# EM80RD.net
KiCad netlist of a schematic drawn in EAGLE
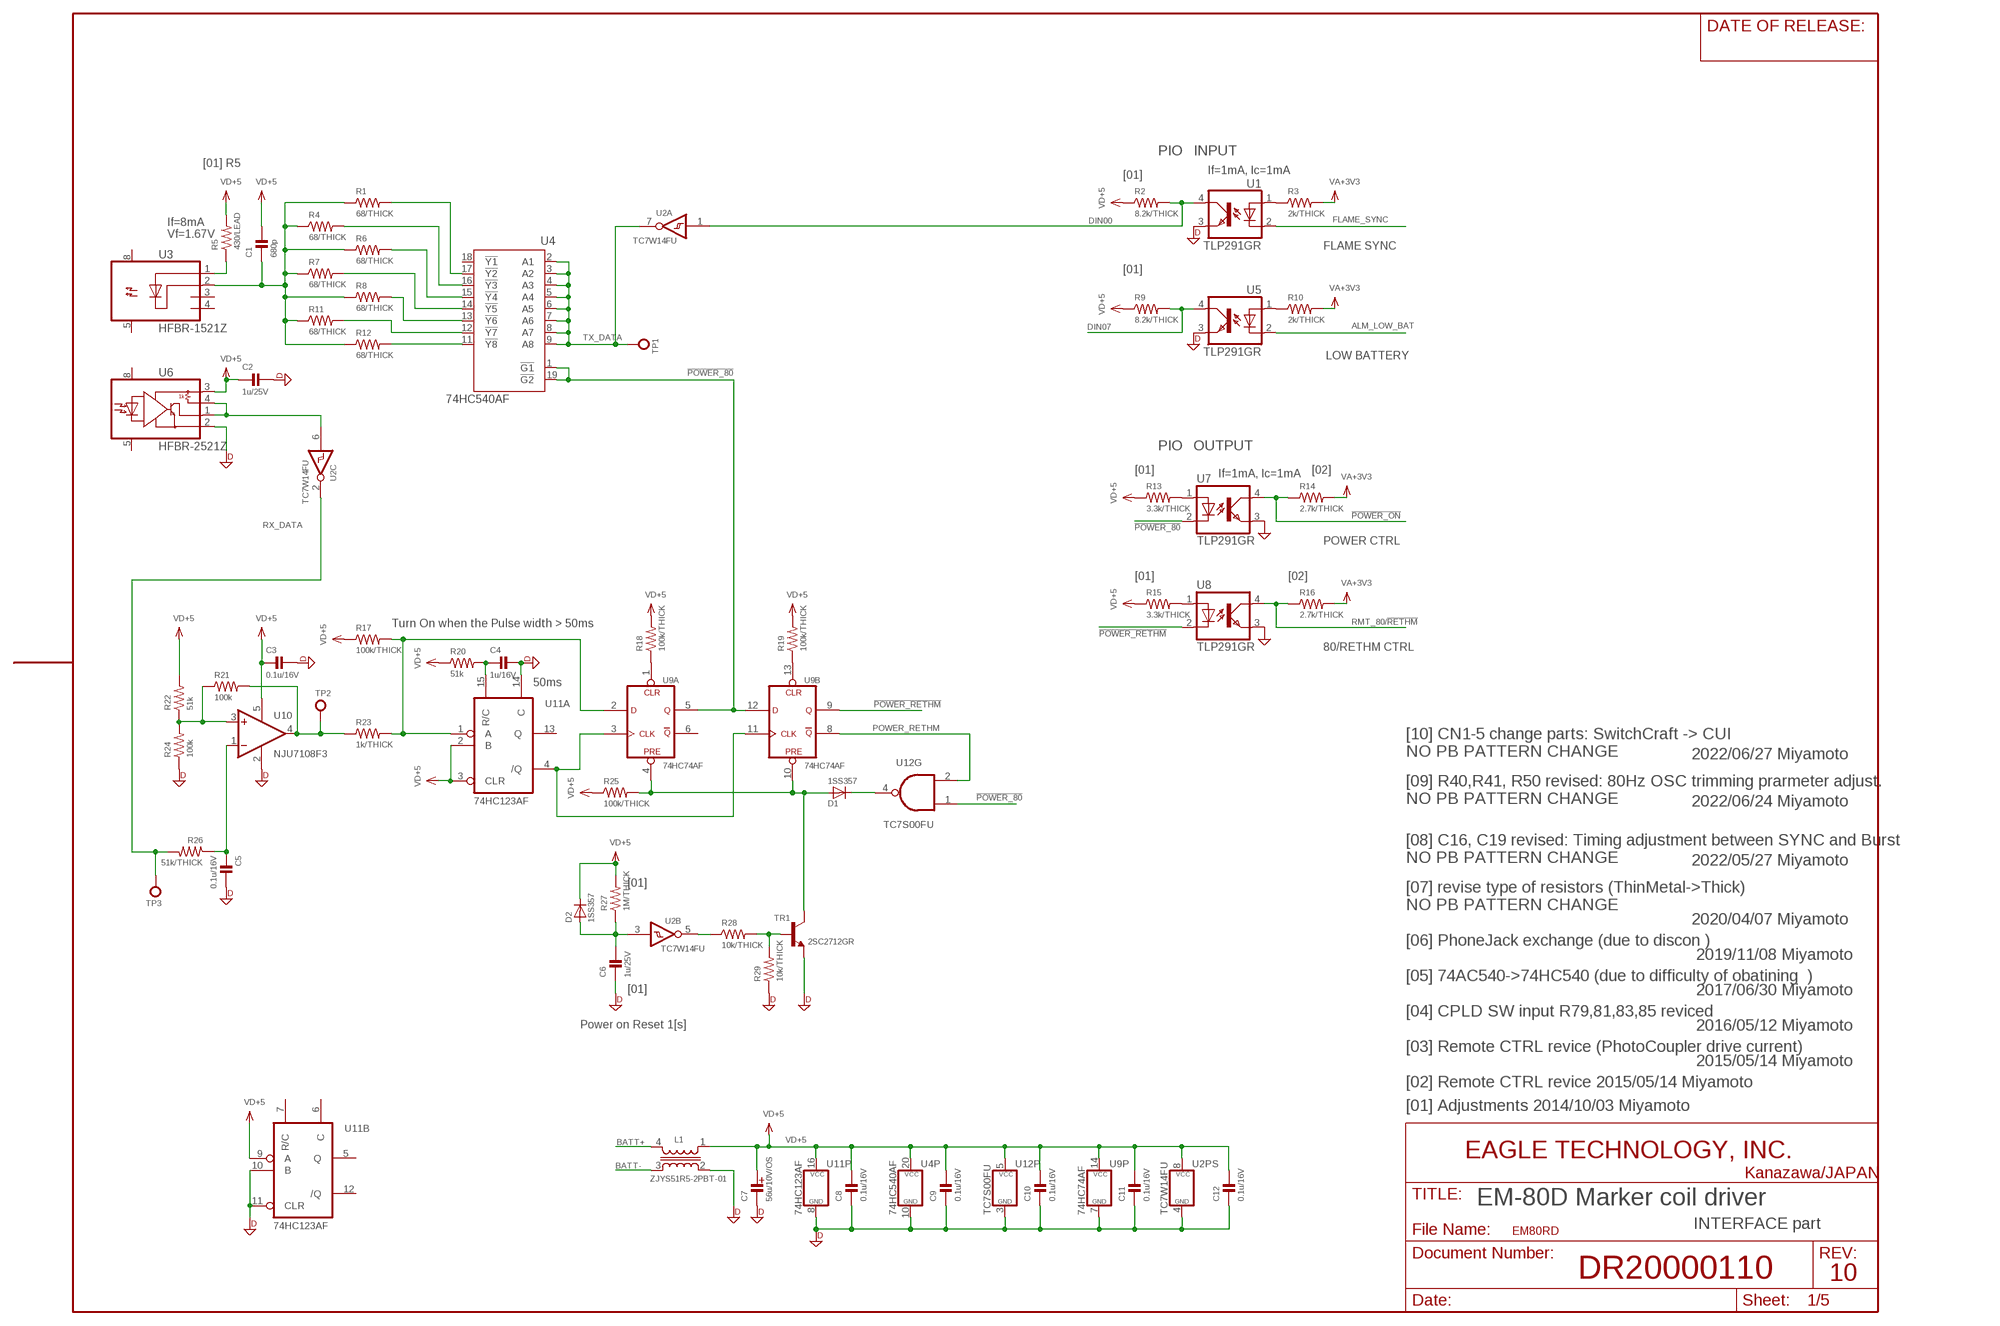
[diagram p0: schematic, sheet 1]
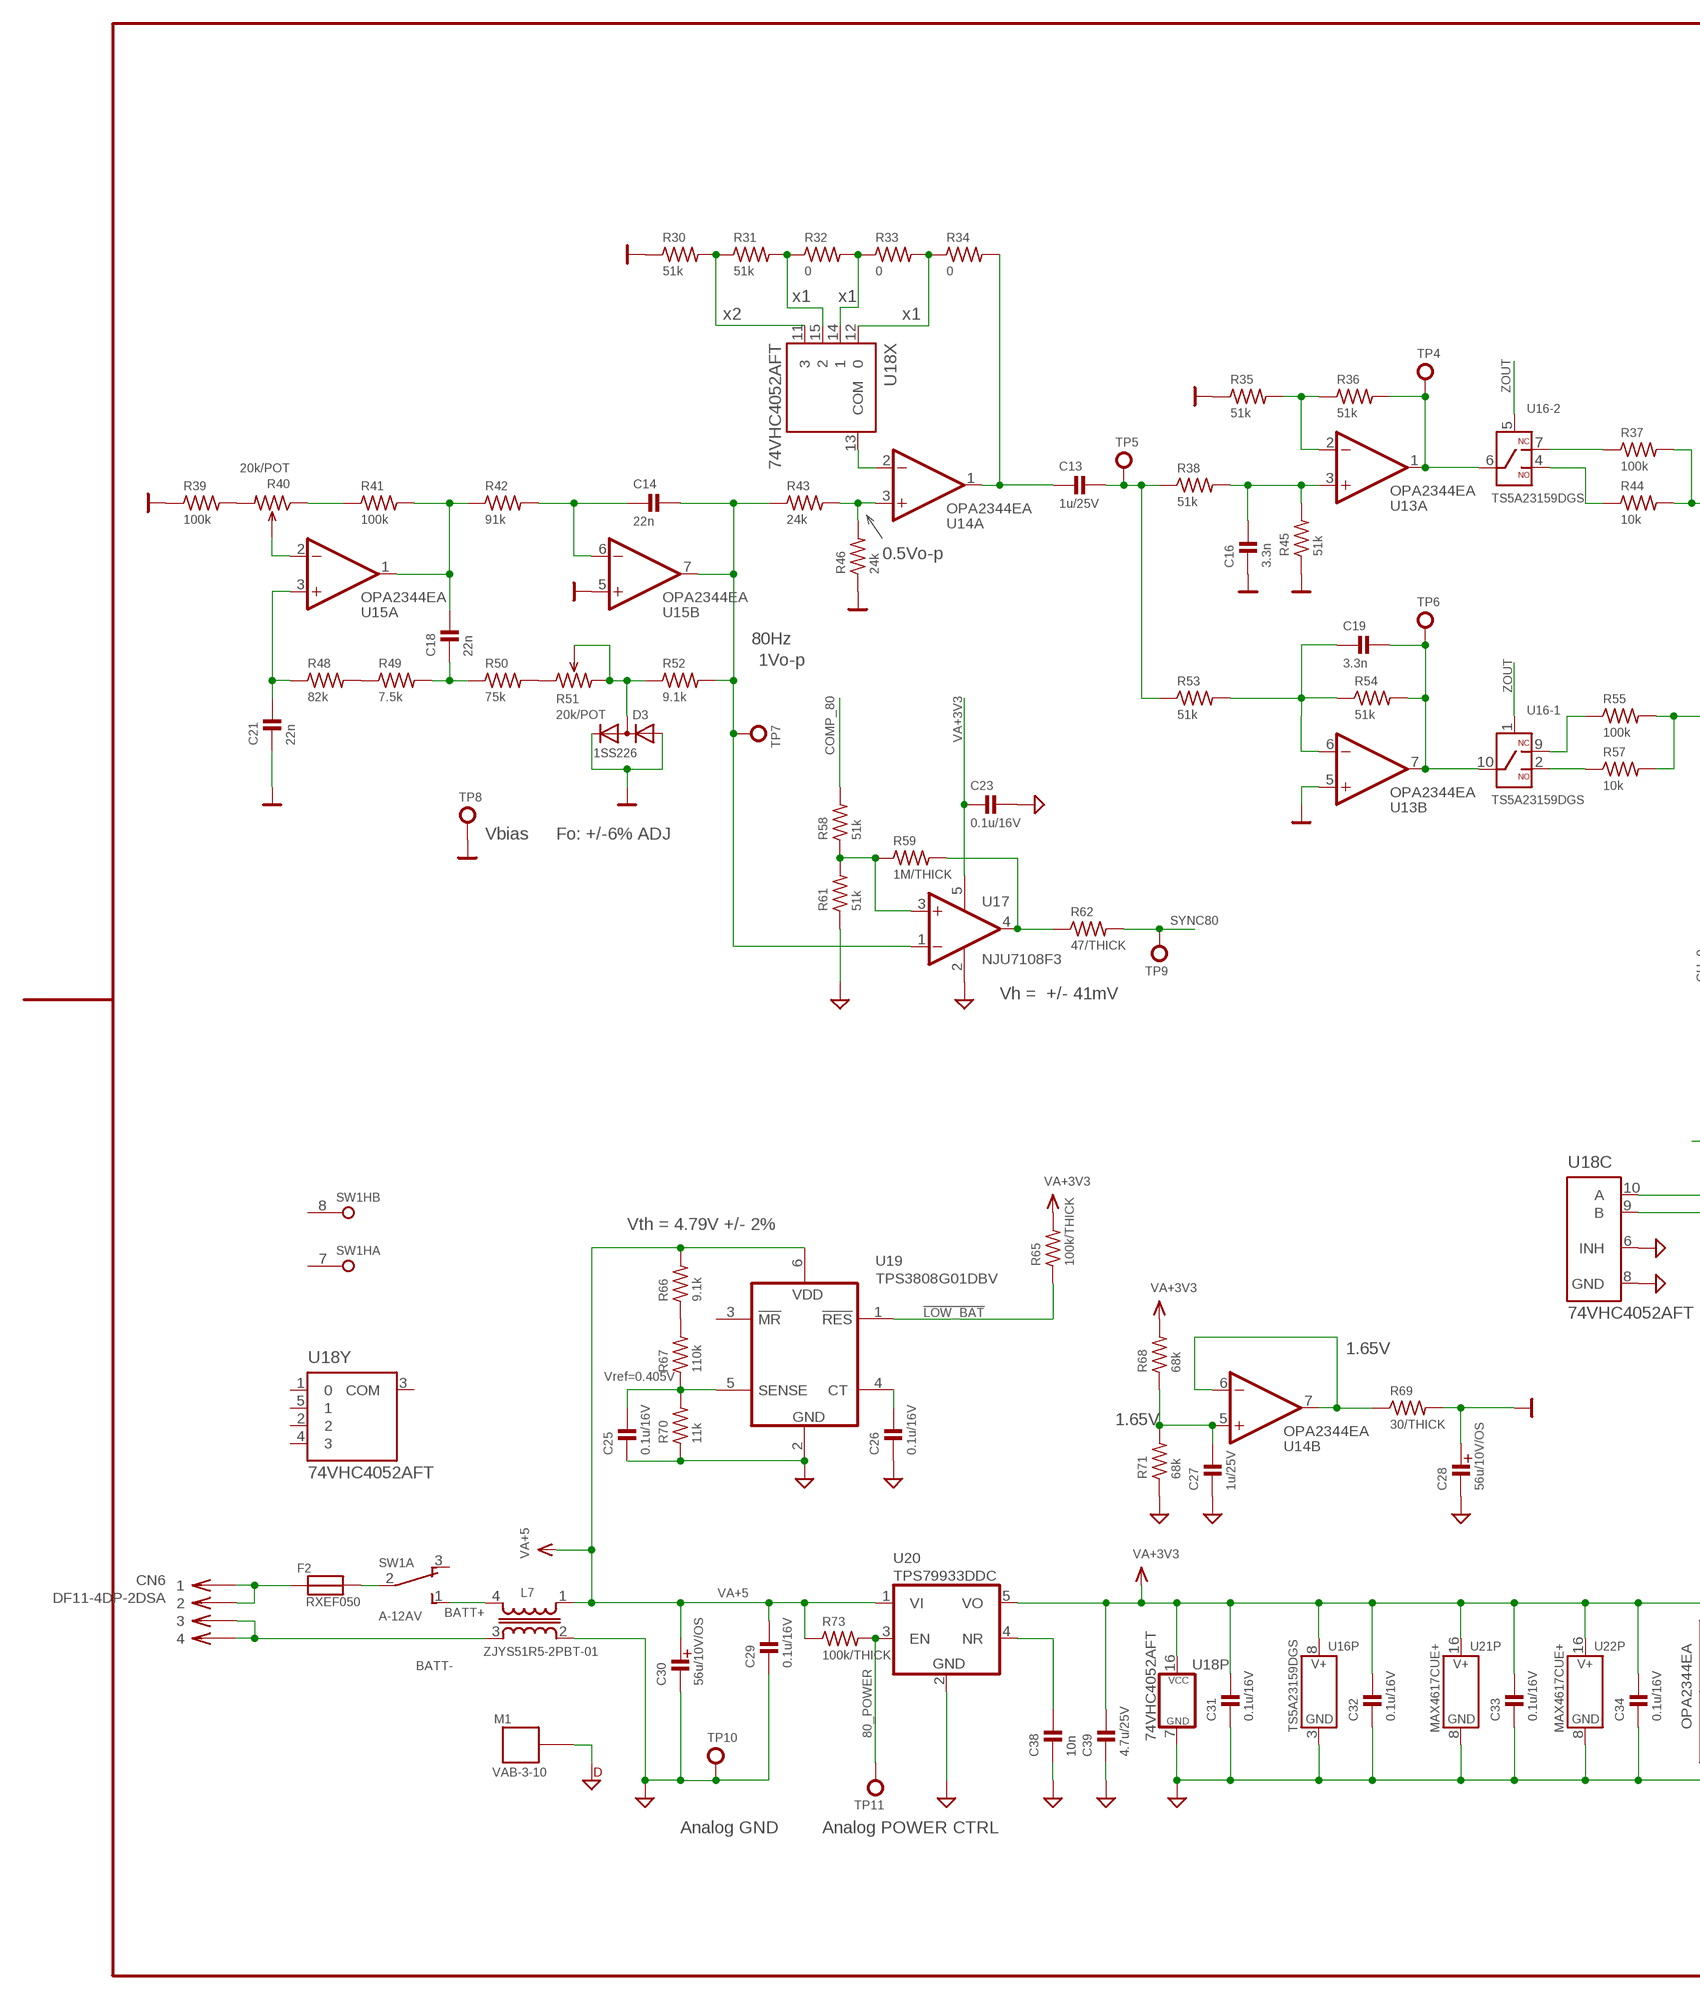
[diagram p1: schematic, sheet 2, part 1 of 2]
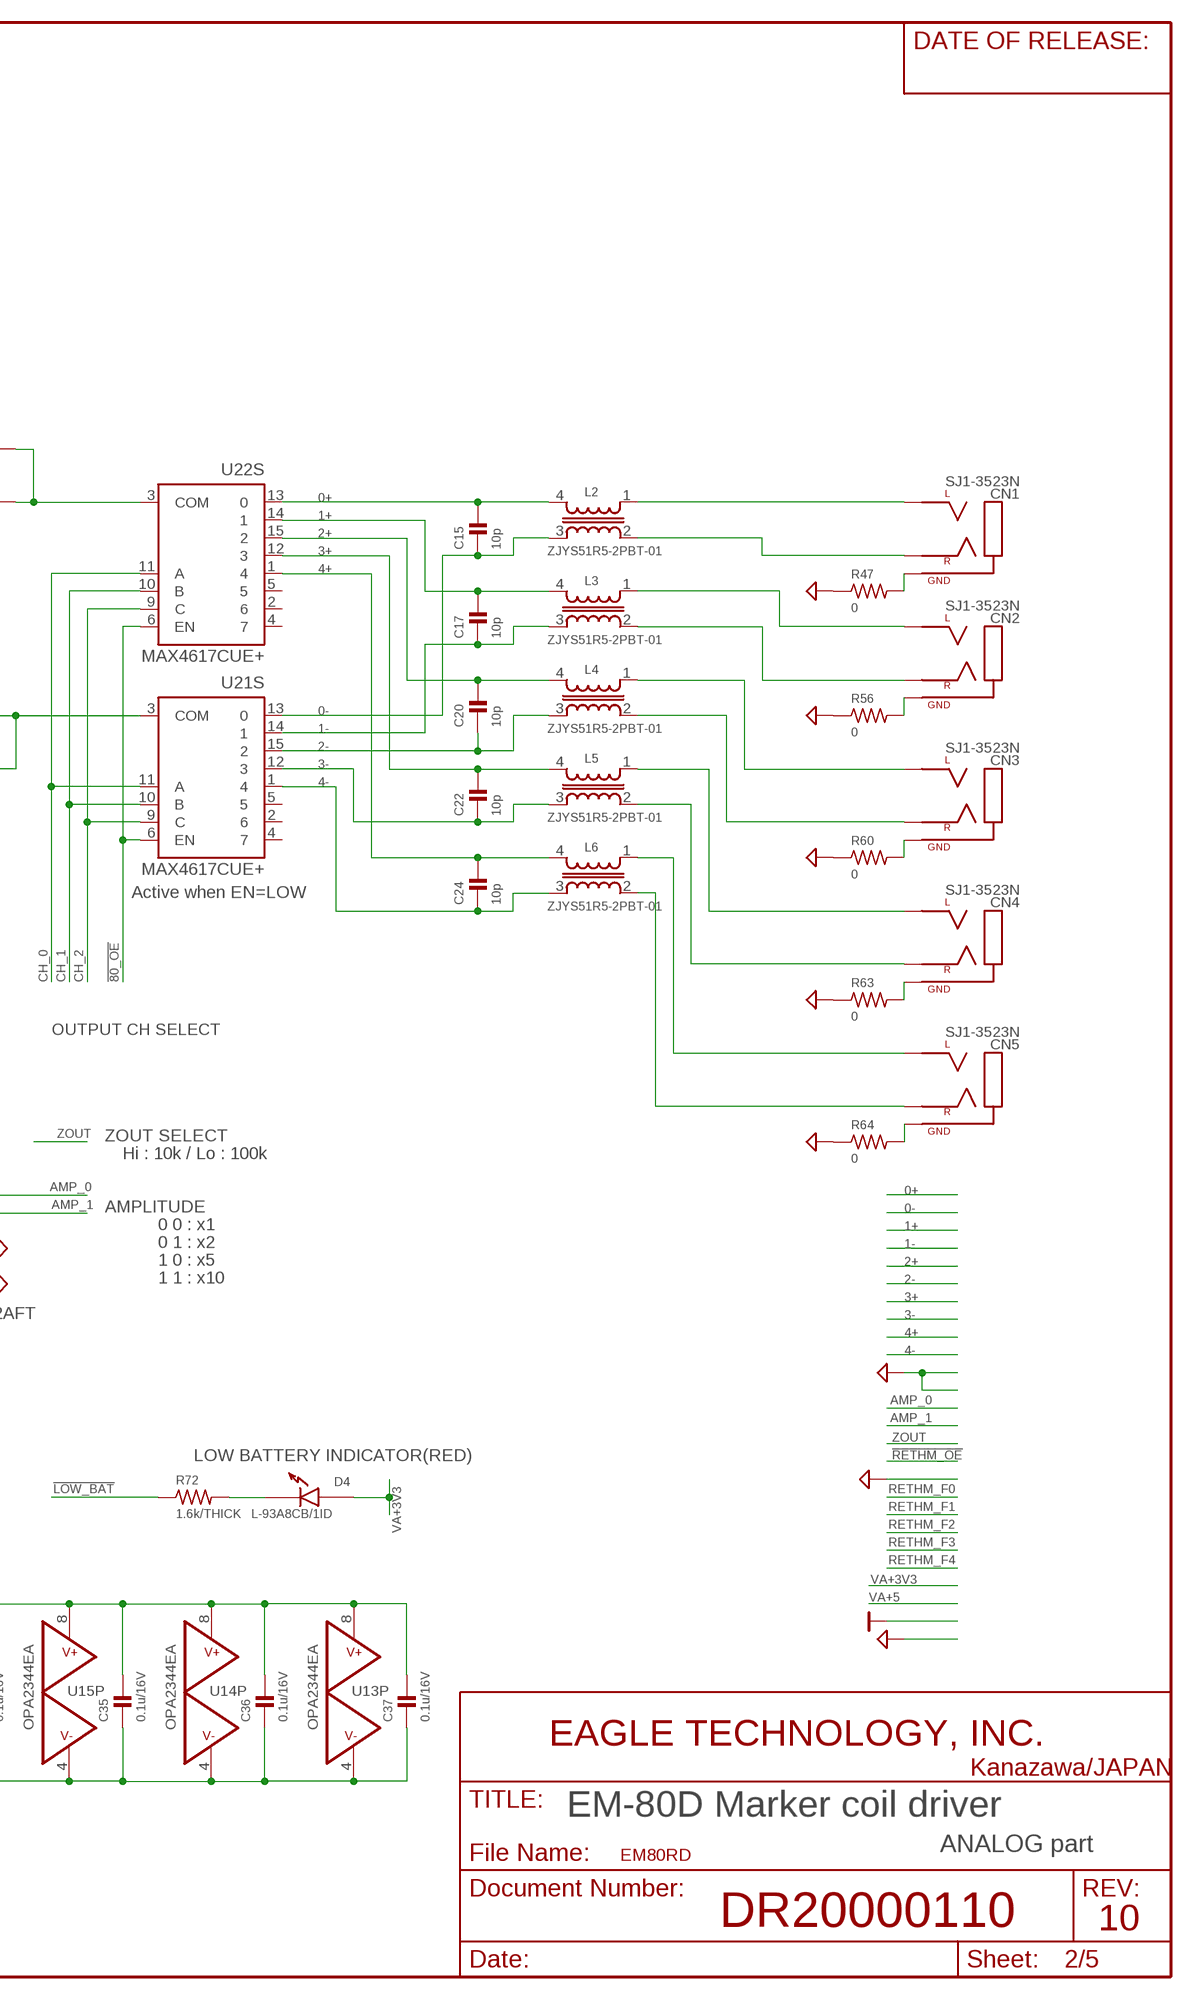
[diagram p2: schematic, sheet 2, part 2 of 2]
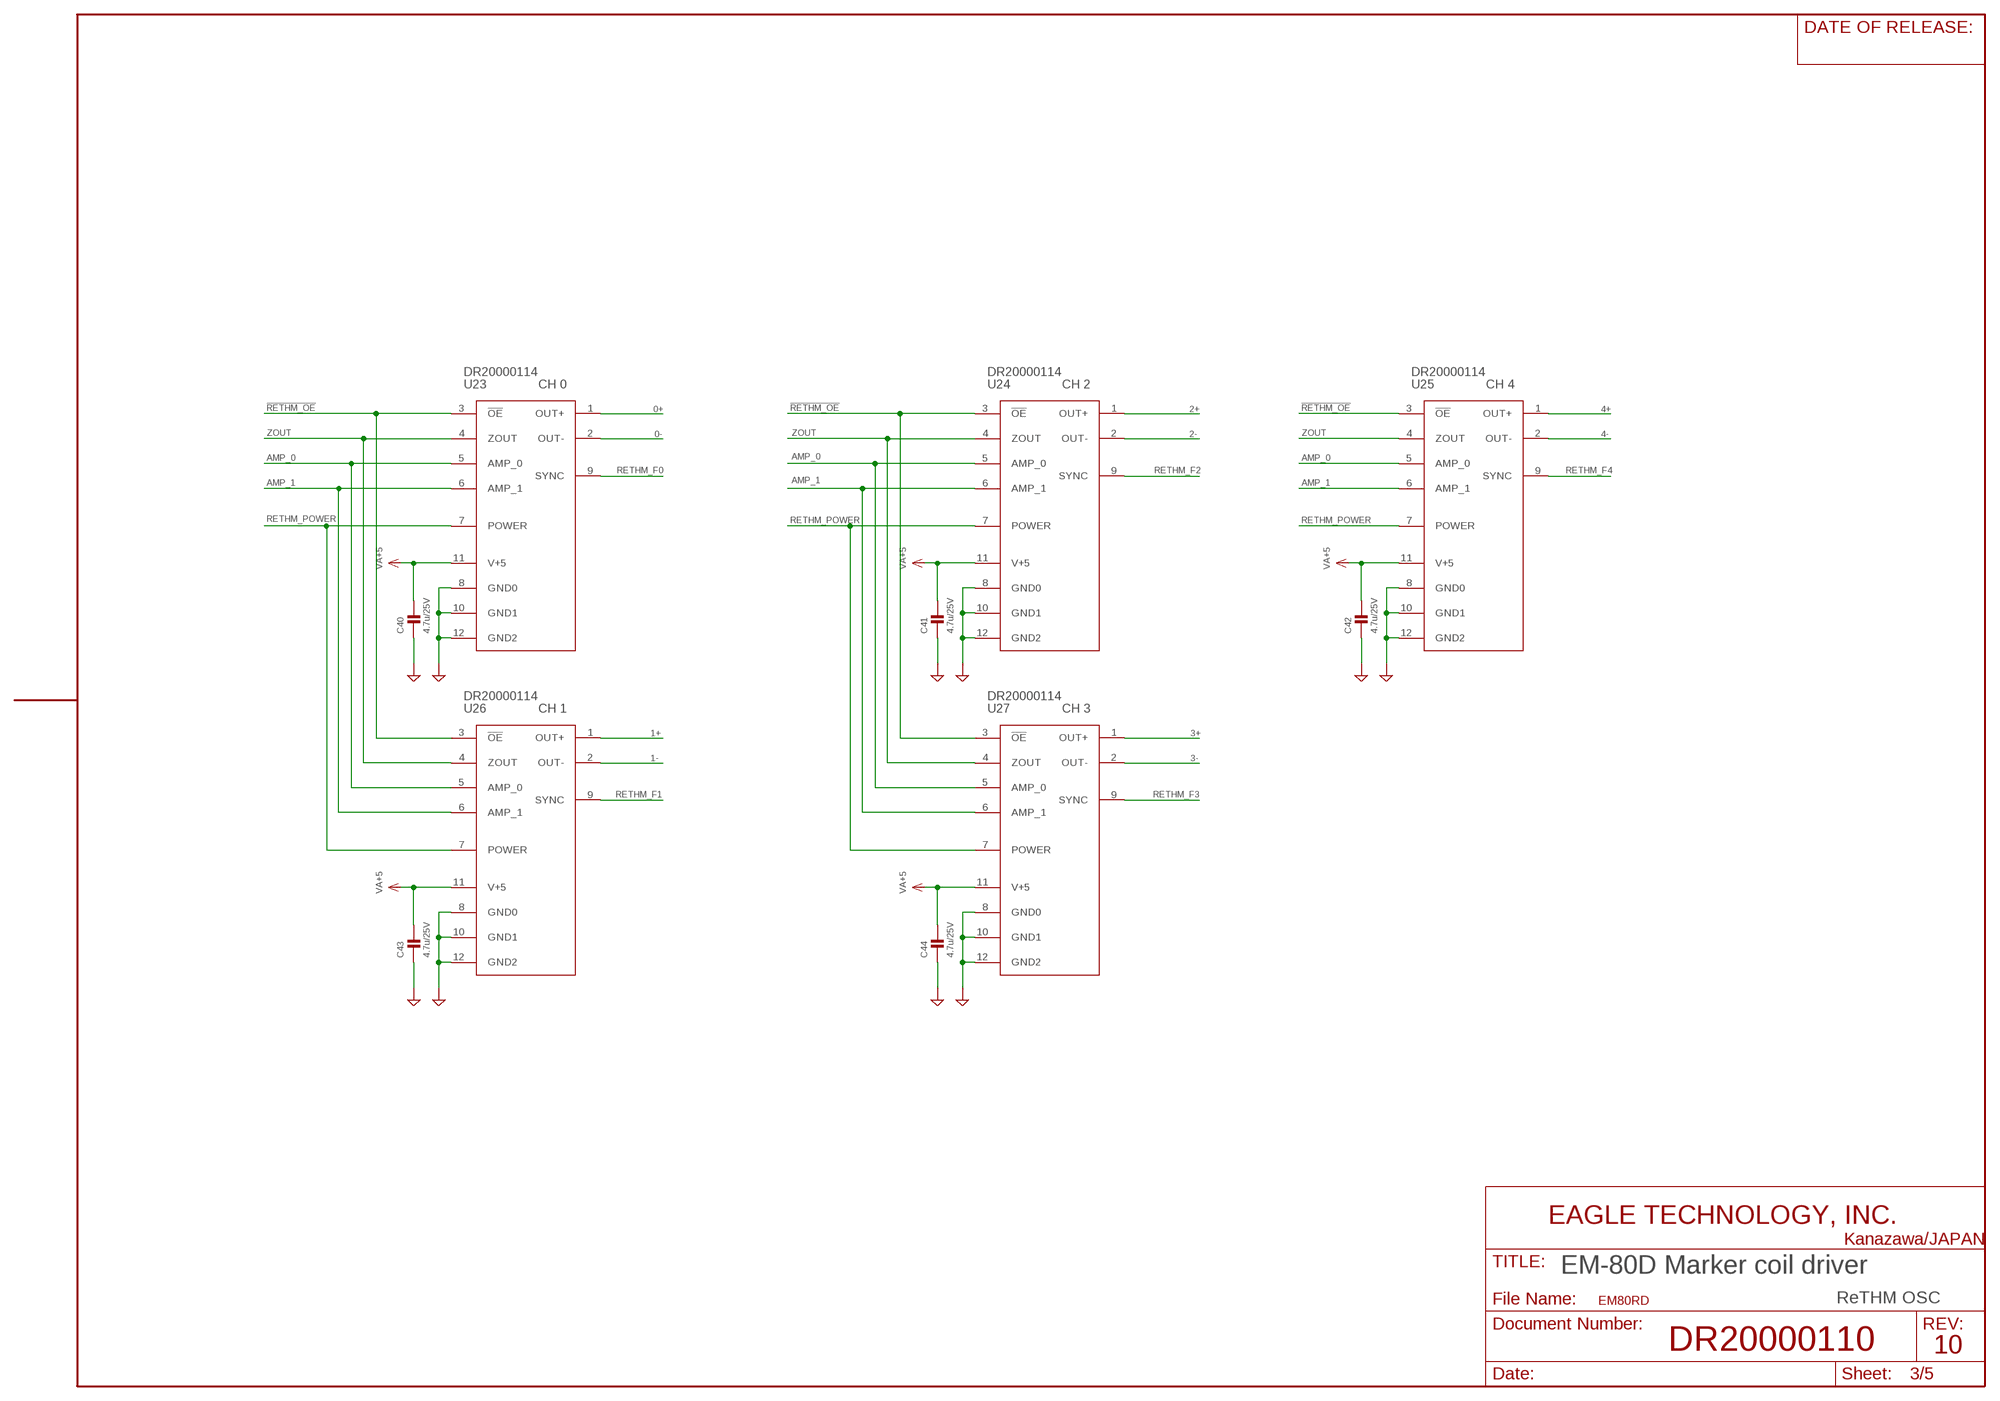
[diagram p3: schematic, sheet 3]
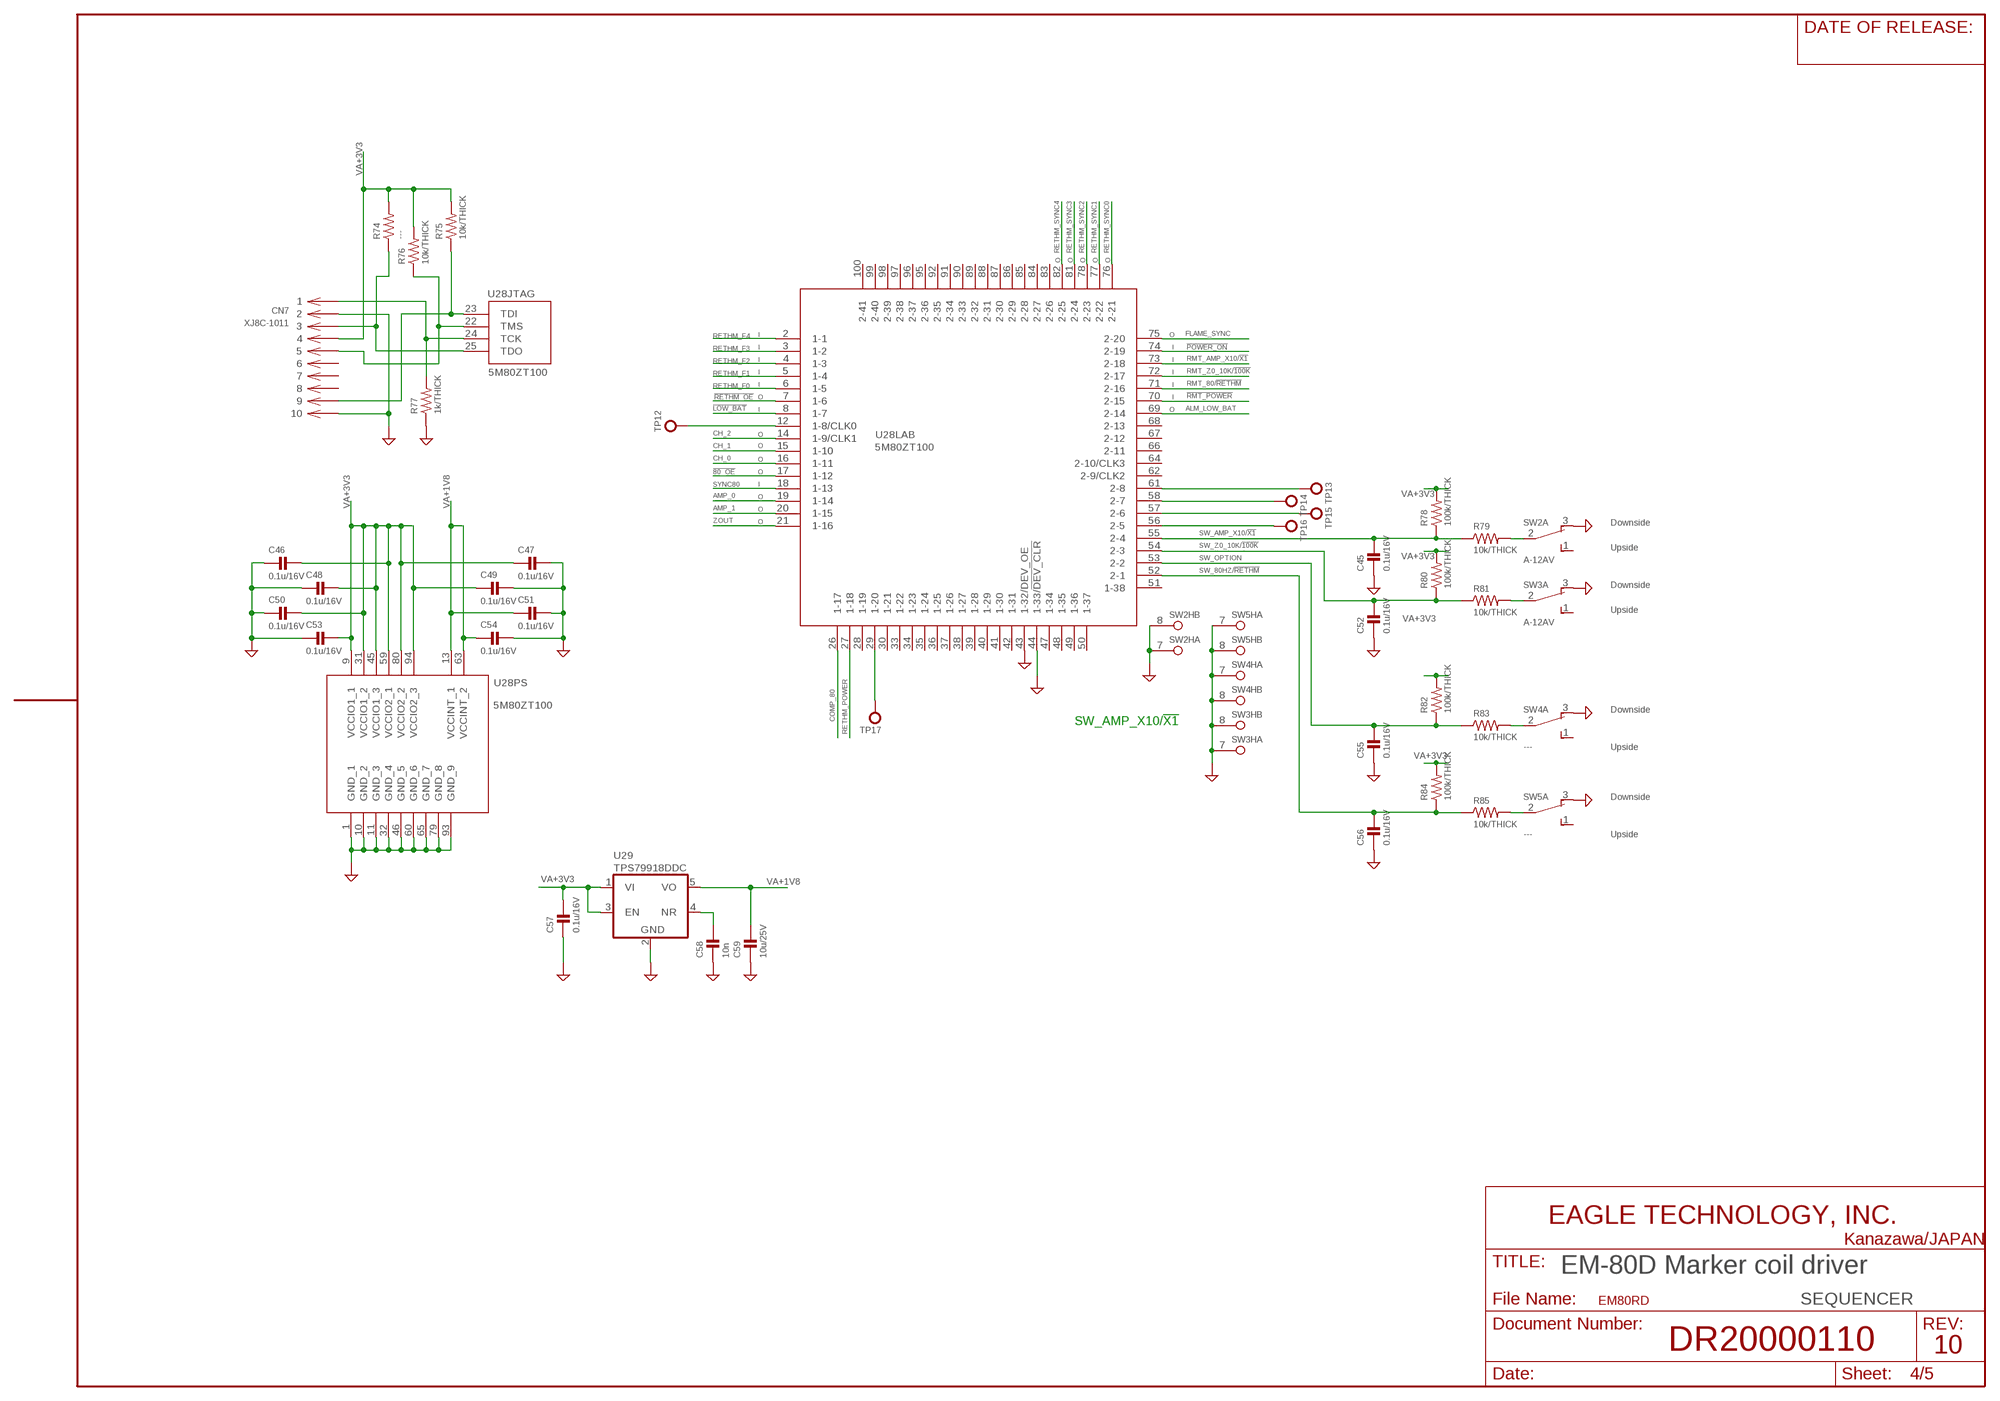
[diagram p4: schematic, sheet 4]
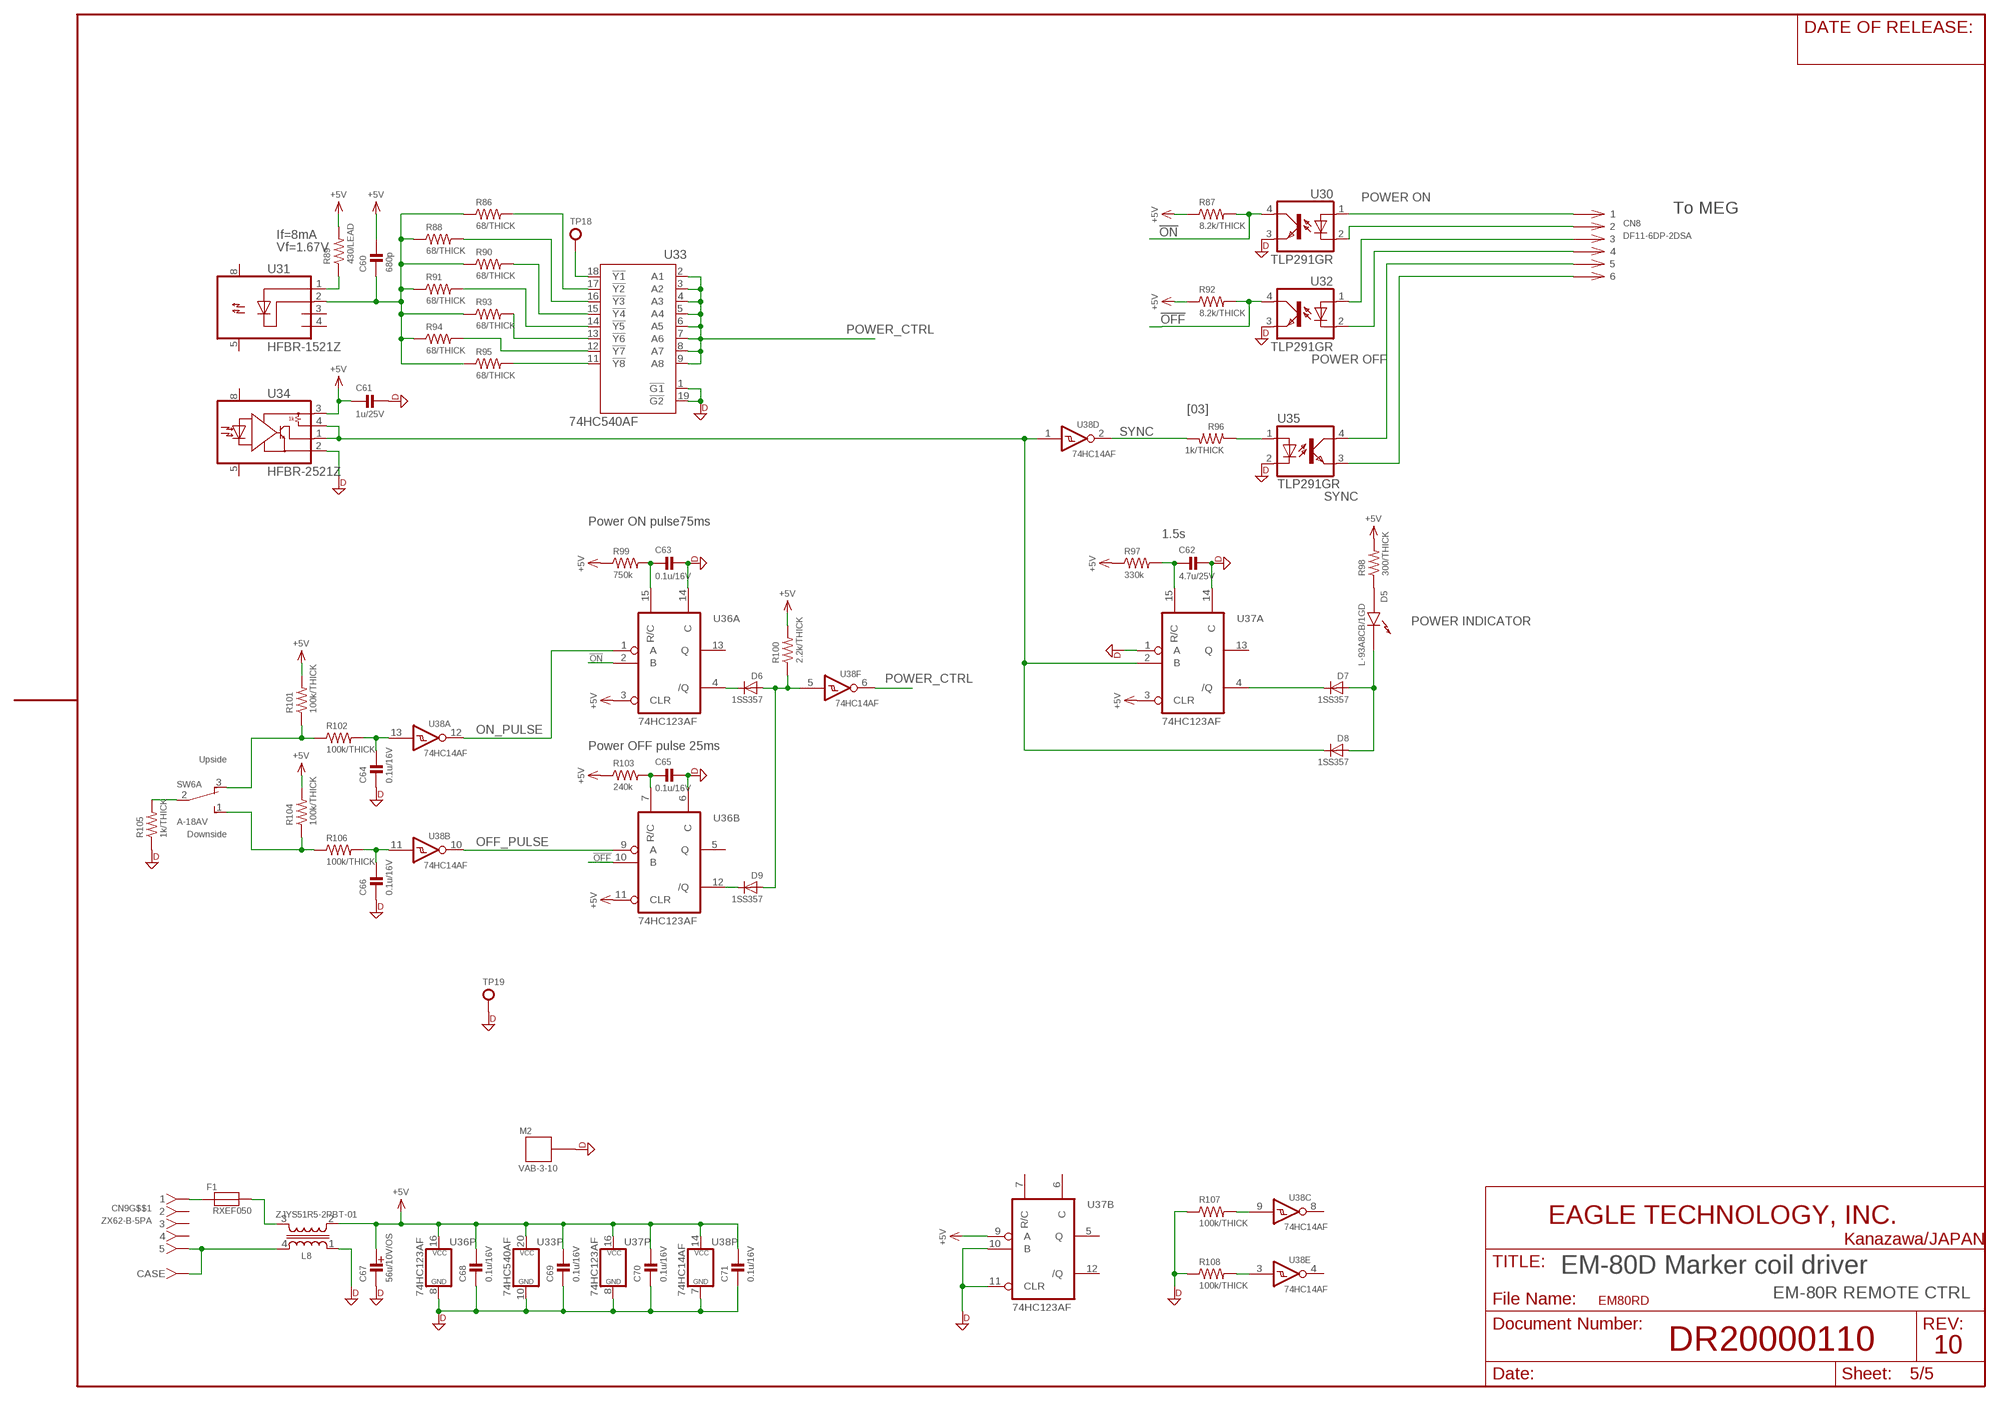
[diagram p5: schematic, sheet 5]

(export (version "E")
  (design (tool "Eeschema 10.0.6"))
  (components
    (comp (ref "C40")
      (value "4.7u/25V")
      (footprint "eagle-import:CM2012")
      (libsource (lib "eagle-import") (part "CSMD2.0X1.2MM"))
    )
    (comp (ref "C41")
      (value "4.7u/25V")
      (footprint "eagle-import:CM2012")
      (libsource (lib "eagle-import") (part "CSMD2.0X1.2MM"))
    )
    (comp (ref "C42")
      (value "4.7u/25V")
      (footprint "eagle-import:CM2012")
      (libsource (lib "eagle-import") (part "CSMD2.0X1.2MM"))
    )
    (comp (ref "C43")
      (value "4.7u/25V")
      (footprint "eagle-import:CM2012")
      (libsource (lib "eagle-import") (part "CSMD2.0X1.2MM"))
    )
    (comp (ref "C44")
      (value "4.7u/25V")
      (footprint "eagle-import:CM2012")
      (libsource (lib "eagle-import") (part "CSMD2.0X1.2MM"))
    )
    (comp (ref "U23")
      (value "DR20000114")
      (footprint "eagle-import:DR20000114")
      (libsource (lib "eagle-import") (part "DR20000114"))
    )
    (comp (ref "U24")
      (value "DR20000114")
      (footprint "eagle-import:DR20000114")
      (libsource (lib "eagle-import") (part "DR20000114"))
    )
    (comp (ref "U25")
      (value "DR20000114")
      (footprint "eagle-import:DR20000114")
      (libsource (lib "eagle-import") (part "DR20000114"))
    )
    (comp (ref "U26")
      (value "DR20000114")
      (footprint "eagle-import:DR20000114")
      (libsource (lib "eagle-import") (part "DR20000114"))
    )
    (comp (ref "U27")
      (value "DR20000114")
      (footprint "eagle-import:DR20000114")
      (libsource (lib "eagle-import") (part "DR20000114"))
    )
    (comp (ref "C13")
      (value "1u/25V")
      (footprint "eagle-import:CM1608")
      (libsource (lib "eagle-import") (part "CSMD1.6X0.8MM"))
    )
    (comp (ref "C14")
      (value "22n")
      (footprint "eagle-import:CM3216")
      (libsource (lib "eagle-import") (part "CSMD3.2X1.6MM"))
    )
    (comp (ref "C15")
      (value "10p")
      (footprint "eagle-import:CM1608")
      (libsource (lib "eagle-import") (part "CSMD1.6X0.8MM"))
    )
    (comp (ref "C16")
      (value "3.3n")
      (footprint "eagle-import:CM2012")
      (libsource (lib "eagle-import") (part "CSMD2.0X1.2MM"))
    )
    (comp (ref "C17")
      (value "10p")
      (footprint "eagle-import:CM1608")
      (libsource (lib "eagle-import") (part "CSMD1.6X0.8MM"))
    )
    (comp (ref "C18")
      (value "22n")
      (footprint "eagle-import:CM3216")
      (libsource (lib "eagle-import") (part "CSMD3.2X1.6MM"))
    )
    (comp (ref "C19")
      (value "3.3n")
      (footprint "eagle-import:CM2012")
      (libsource (lib "eagle-import") (part "CSMD2.0X1.2MM"))
    )
    (comp (ref "C20")
      (value "10p")
      (footprint "eagle-import:CM1608")
      (libsource (lib "eagle-import") (part "CSMD1.6X0.8MM"))
    )
    (comp (ref "C21")
      (value "22n")
      (footprint "eagle-import:CM3216")
      (libsource (lib "eagle-import") (part "CSMD3.2X1.6MM"))
    )
    (comp (ref "C22")
      (value "10p")
      (footprint "eagle-import:CM1608")
      (libsource (lib "eagle-import") (part "CSMD1.6X0.8MM"))
    )
    (comp (ref "C23")
      (value "0.1u/16V")
      (footprint "eagle-import:CM1608")
      (libsource (lib "eagle-import") (part "CSMD1.6X0.8MM"))
    )
    (comp (ref "C24")
      (value "10p")
      (footprint "eagle-import:CM1608")
      (libsource (lib "eagle-import") (part "CSMD1.6X0.8MM"))
    )
    (comp (ref "C25")
      (value "0.1u/16V")
      (footprint "eagle-import:CM1608")
      (libsource (lib "eagle-import") (part "CSMD1.6X0.8MM"))
    )
    (comp (ref "C26")
      (value "0.1u/16V")
      (footprint "eagle-import:CM1608")
      (libsource (lib "eagle-import") (part "CSMD1.6X0.8MM"))
    )
    (comp (ref "C27")
      (value "1u/25V")
      (footprint "eagle-import:CM1608")
      (libsource (lib "eagle-import") (part "CSMD1.6X0.8MM"))
    )
    (comp (ref "C28")
      (value "56u/10V/OS")
      (footprint "eagle-import:PHI_6.3")
      (libsource (lib "eagle-import") (part "C_POL6.3-2.5MM"))
    )
    (comp (ref "C29")
      (value "0.1u/16V")
      (footprint "eagle-import:CM1608")
      (libsource (lib "eagle-import") (part "CSMD1.6X0.8MM"))
    )
    (comp (ref "C30")
      (value "56u/10V/OS")
      (footprint "eagle-import:PHI_6.3")
      (libsource (lib "eagle-import") (part "C_POL6.3-2.5MM"))
    )
    (comp (ref "C31")
      (value "0.1u/16V")
      (footprint "eagle-import:CM1608")
      (libsource (lib "eagle-import") (part "CSMD1.6X0.8MM"))
    )
    (comp (ref "C32")
      (value "0.1u/16V")
      (footprint "eagle-import:CM1608")
      (libsource (lib "eagle-import") (part "CSMD1.6X0.8MM"))
    )
    (comp (ref "C33")
      (value "0.1u/16V")
      (footprint "eagle-import:CM1608")
      (libsource (lib "eagle-import") (part "CSMD1.6X0.8MM"))
    )
    (comp (ref "C34")
      (value "0.1u/16V")
      (footprint "eagle-import:CM1608")
      (libsource (lib "eagle-import") (part "CSMD1.6X0.8MM"))
    )
    (comp (ref "C35")
      (value "0.1u/16V")
      (footprint "eagle-import:CM1608")
      (libsource (lib "eagle-import") (part "CSMD1.6X0.8MM"))
    )
    (comp (ref "C36")
      (value "0.1u/16V")
      (footprint "eagle-import:CM1608")
      (libsource (lib "eagle-import") (part "CSMD1.6X0.8MM"))
    )
    (comp (ref "C37")
      (value "0.1u/16V")
      (footprint "eagle-import:CM1608")
      (libsource (lib "eagle-import") (part "CSMD1.6X0.8MM"))
    )
    (comp (ref "C38")
      (value "10n")
      (footprint "eagle-import:CM2012")
      (libsource (lib "eagle-import") (part "CSMD2.0X1.2MM"))
    )
    (comp (ref "C39")
      (value "4.7u/25V")
      (footprint "eagle-import:CM2012")
      (libsource (lib "eagle-import") (part "CSMD2.0X1.2MM"))
    )
    (comp (ref "CN1")
      (value "SJ1-3523N")
      (footprint "eagle-import:35RAPC2BHN2")
      (libsource (lib "eagle-import") (part "35RAPC2BHN2"))
    )
    (comp (ref "CN2")
      (value "SJ1-3523N")
      (footprint "eagle-import:35RAPC2BHN2")
      (libsource (lib "eagle-import") (part "35RAPC2BHN2"))
    )
    (comp (ref "CN3")
      (value "SJ1-3523N")
      (footprint "eagle-import:35RAPC2BHN2")
      (libsource (lib "eagle-import") (part "35RAPC2BHN2"))
    )
    (comp (ref "CN4")
      (value "SJ1-3523N")
      (footprint "eagle-import:35RAPC2BHN2")
      (libsource (lib "eagle-import") (part "35RAPC2BHN2"))
    )
    (comp (ref "CN5")
      (value "SJ1-3523N")
      (footprint "eagle-import:35RAPC2BHN2")
      (libsource (lib "eagle-import") (part "35RAPC2BHN2"))
    )
    (comp (ref "CN6")
      (value "DF11-4DP-2DSA")
      (footprint "eagle-import:DF11-4DP-2DSA")
      (libsource (lib "eagle-import") (part "DF11-4DP-2DSA"))
    )
    (comp (ref "D3")
      (value "1SS226")
      (footprint "eagle-import:SOT23")
      (libsource (lib "eagle-import") (part "1SS226"))
    )
    (comp (ref "D4")
      (value "L-93A8CB/1ID")
      (footprint "eagle-import:L-93A8CB")
      (libsource (lib "eagle-import") (part "L-93A8CB/1ID"))
    )
    (comp (ref "F2")
      (value "RXEF050")
      (footprint "eagle-import:8X3_5.08")
      (libsource (lib "eagle-import") (part "RXEF050"))
    )
    (comp (ref "L2")
      (value "ZJYS51R5-2PBT-01")
      (footprint "eagle-import:ZJYS51-2")
      (libsource (lib "eagle-import") (part "ZJYS5R5-2PBT-01"))
    )
    (comp (ref "L3")
      (value "ZJYS51R5-2PBT-01")
      (footprint "eagle-import:ZJYS51-2")
      (libsource (lib "eagle-import") (part "ZJYS5R5-2PBT-01"))
    )
    (comp (ref "L4")
      (value "ZJYS51R5-2PBT-01")
      (footprint "eagle-import:ZJYS51-2")
      (libsource (lib "eagle-import") (part "ZJYS5R5-2PBT-01"))
    )
    (comp (ref "L5")
      (value "ZJYS51R5-2PBT-01")
      (footprint "eagle-import:ZJYS51-2")
      (libsource (lib "eagle-import") (part "ZJYS5R5-2PBT-01"))
    )
    (comp (ref "L6")
      (value "ZJYS51R5-2PBT-01")
      (footprint "eagle-import:ZJYS51-2")
      (libsource (lib "eagle-import") (part "ZJYS5R5-2PBT-01"))
    )
    (comp (ref "L7")
      (value "ZJYS51R5-2PBT-01")
      (footprint "eagle-import:ZJYS51-2")
      (libsource (lib "eagle-import") (part "ZJYS5R5-2PBT-01"))
    )
    (comp (ref "M1")
      (value "VAB-3-10")
      (footprint "eagle-import:VAB_3_10_CONTACT")
      (libsource (lib "eagle-import") (part "VAB-3-10"))
    )
    (comp (ref "R30")
      (value "51k")
      (footprint "eagle-import:RM1608")
      (libsource (lib "eagle-import") (part "RSMD1.6X0.8MM"))
    )
    (comp (ref "R31")
      (value "51k")
      (footprint "eagle-import:RM1608")
      (libsource (lib "eagle-import") (part "RSMD1.6X0.8MM"))
    )
    (comp (ref "R32")
      (value "0")
      (footprint "eagle-import:RM1608")
      (libsource (lib "eagle-import") (part "RSMD1.6X0.8MM"))
    )
    (comp (ref "R33")
      (value "0")
      (footprint "eagle-import:RM1608")
      (libsource (lib "eagle-import") (part "RSMD1.6X0.8MM"))
    )
    (comp (ref "R34")
      (value "0")
      (footprint "eagle-import:RM1608")
      (libsource (lib "eagle-import") (part "RSMD1.6X0.8MM"))
    )
    (comp (ref "R35")
      (value "51k")
      (footprint "eagle-import:RM1608")
      (libsource (lib "eagle-import") (part "RSMD1.6X0.8MM"))
    )
    (comp (ref "R36")
      (value "51k")
      (footprint "eagle-import:RM1608")
      (libsource (lib "eagle-import") (part "RSMD1.6X0.8MM"))
    )
    (comp (ref "R37")
      (value "100k")
      (footprint "eagle-import:RM1608")
      (libsource (lib "eagle-import") (part "RSMD1.6X0.8MM"))
    )
    (comp (ref "R38")
      (value "51k")
      (footprint "eagle-import:RM1608")
      (libsource (lib "eagle-import") (part "RSMD1.6X0.8MM"))
    )
    (comp (ref "R39")
      (value "100k")
      (footprint "eagle-import:RM1608")
      (libsource (lib "eagle-import") (part "RSMD1.6X0.8MM"))
    )
    (comp (ref "R40")
      (value "20k/POT")
      (footprint "eagle-import:CT-6")
      (libsource (lib "eagle-import") (part "R_POT"))
    )
    (comp (ref "R41")
      (value "100k")
      (footprint "eagle-import:RM1608")
      (libsource (lib "eagle-import") (part "RSMD1.6X0.8MM"))
    )
    (comp (ref "R42")
      (value "91k")
      (footprint "eagle-import:RM1608")
      (libsource (lib "eagle-import") (part "RSMD1.6X0.8MM"))
    )
    (comp (ref "R43")
      (value "24k")
      (footprint "eagle-import:RM1608")
      (libsource (lib "eagle-import") (part "RSMD1.6X0.8MM"))
    )
    (comp (ref "R44")
      (value "10k")
      (footprint "eagle-import:RM1608")
      (libsource (lib "eagle-import") (part "RSMD1.6X0.8MM"))
    )
    (comp (ref "R45")
      (value "51k")
      (footprint "eagle-import:RM1608")
      (libsource (lib "eagle-import") (part "RSMD1.6X0.8MM"))
    )
    (comp (ref "R46")
      (value "24k")
      (footprint "eagle-import:RM1608")
      (libsource (lib "eagle-import") (part "RSMD1.6X0.8MM"))
    )
    (comp (ref "R47")
      (value "0")
      (footprint "eagle-import:RM1608")
      (libsource (lib "eagle-import") (part "RSMD1.6X0.8MM"))
    )
    (comp (ref "R48")
      (value "82k")
      (footprint "eagle-import:RM1608")
      (libsource (lib "eagle-import") (part "RSMD1.6X0.8MM"))
    )
    (comp (ref "R49")
      (value "7.5k")
      (footprint "eagle-import:RM1608")
      (libsource (lib "eagle-import") (part "RSMD1.6X0.8MM"))
    )
    (comp (ref "R50")
      (value "75k")
      (footprint "eagle-import:RM1608")
      (libsource (lib "eagle-import") (part "RSMD1.6X0.8MM"))
    )
    (comp (ref "R51")
      (value "20k/POT")
      (footprint "eagle-import:CT-6")
      (libsource (lib "eagle-import") (part "R_POT"))
    )
    (comp (ref "R52")
      (value "9.1k")
      (footprint "eagle-import:RM1608")
      (libsource (lib "eagle-import") (part "RSMD1.6X0.8MM"))
    )
    (comp (ref "R53")
      (value "51k")
      (footprint "eagle-import:RM1608")
      (libsource (lib "eagle-import") (part "RSMD1.6X0.8MM"))
    )
    (comp (ref "R54")
      (value "51k")
      (footprint "eagle-import:RM1608")
      (libsource (lib "eagle-import") (part "RSMD1.6X0.8MM"))
    )
    (comp (ref "R55")
      (value "100k")
      (footprint "eagle-import:RM1608")
      (libsource (lib "eagle-import") (part "RSMD1.6X0.8MM"))
    )
    (comp (ref "R56")
      (value "0")
      (footprint "eagle-import:RM1608")
      (libsource (lib "eagle-import") (part "RSMD1.6X0.8MM"))
    )
    (comp (ref "R57")
      (value "10k")
      (footprint "eagle-import:RM1608")
      (libsource (lib "eagle-import") (part "RSMD1.6X0.8MM"))
    )
    (comp (ref "R58")
      (value "51k")
      (footprint "eagle-import:RM1608")
      (libsource (lib "eagle-import") (part "RSMD1.6X0.8MM"))
    )
    (comp (ref "R59")
      (value "1M/THICK")
      (footprint "eagle-import:RM1608")
      (libsource (lib "eagle-import") (part "RSMD1.6X0.8MM"))
    )
    (comp (ref "R60")
      (value "0")
      (footprint "eagle-import:RM1608")
      (libsource (lib "eagle-import") (part "RSMD1.6X0.8MM"))
    )
    (comp (ref "R61")
      (value "51k")
      (footprint "eagle-import:RM1608")
      (libsource (lib "eagle-import") (part "RSMD1.6X0.8MM"))
    )
    (comp (ref "R62")
      (value "47/THICK")
      (footprint "eagle-import:RM1608")
      (libsource (lib "eagle-import") (part "RSMD1.6X0.8MM"))
    )
    (comp (ref "R63")
      (value "0")
      (footprint "eagle-import:RM1608")
      (libsource (lib "eagle-import") (part "RSMD1.6X0.8MM"))
    )
    (comp (ref "R64")
      (value "0")
      (footprint "eagle-import:RM1608")
      (libsource (lib "eagle-import") (part "RSMD1.6X0.8MM"))
    )
    (comp (ref "R65")
      (value "100k/THICK")
      (footprint "eagle-import:RM1608")
      (libsource (lib "eagle-import") (part "RSMD1.6X0.8MM"))
    )
    (comp (ref "R66")
      (value "9.1k")
      (footprint "eagle-import:RM1608")
      (libsource (lib "eagle-import") (part "RSMD1.6X0.8MM"))
    )
    (comp (ref "R67")
      (value "110k")
      (footprint "eagle-import:RM1608")
      (libsource (lib "eagle-import") (part "RSMD1.6X0.8MM"))
    )
    (comp (ref "R68")
      (value "68k")
      (footprint "eagle-import:RM1608")
      (libsource (lib "eagle-import") (part "RSMD1.6X0.8MM"))
    )
    (comp (ref "R69")
      (value "30/THICK")
      (footprint "eagle-import:RM1608")
      (libsource (lib "eagle-import") (part "RSMD1.6X0.8MM"))
    )
    (comp (ref "R70")
      (value "11k")
      (footprint "eagle-import:RM1608")
      (libsource (lib "eagle-import") (part "RSMD1.6X0.8MM"))
    )
    (comp (ref "R71")
      (value "68k")
      (footprint "eagle-import:RM1608")
      (libsource (lib "eagle-import") (part "RSMD1.6X0.8MM"))
    )
    (comp (ref "R72")
      (value "1.6k/THICK")
      (footprint "eagle-import:RM1608")
      (libsource (lib "eagle-import") (part "RSMD1.6X0.8MM"))
    )
    (comp (ref "R73")
      (value "100k/THICK")
      (footprint "eagle-import:RM1608")
      (libsource (lib "eagle-import") (part "RSMD1.6X0.8MM"))
    )
    (comp (ref "SW1")
      (value "A-12AV")
      (footprint "eagle-import:A-12_")
      (libsource (lib "eagle-import") (part "A-1V2A"))
    )
    (comp (ref "TP4")
      (value "TP-LC3G")
      (footprint "eagle-import:TP_TH_0R9MM")
      (libsource (lib "eagle-import") (part "TP-LC3G"))
    )
    (comp (ref "TP5")
      (value "TP-LC3G")
      (footprint "eagle-import:TP_TH_0R9MM")
      (libsource (lib "eagle-import") (part "TP-LC3G"))
    )
    (comp (ref "TP6")
      (value "TP-LC3G")
      (footprint "eagle-import:TP_TH_0R9MM")
      (libsource (lib "eagle-import") (part "TP-LC3G"))
    )
    (comp (ref "TP7")
      (value "TP-LC3G")
      (footprint "eagle-import:TP_TH_0R9MM")
      (libsource (lib "eagle-import") (part "TP-LC3G"))
    )
    (comp (ref "TP8")
      (value "TP-LC3G")
      (footprint "eagle-import:TP_TH_0R9MM")
      (libsource (lib "eagle-import") (part "TP-LC3G"))
    )
    (comp (ref "TP9")
      (value "TP-LC3G")
      (footprint "eagle-import:TP_TH_0R9MM")
      (libsource (lib "eagle-import") (part "TP-LC3G"))
    )
    (comp (ref "TP10")
      (value "TP-LC3G")
      (footprint "eagle-import:TP_TH_0R9MM")
      (libsource (lib "eagle-import") (part "TP-LC3G"))
    )
    (comp (ref "TP11")
      (value "TP-LC3G")
      (footprint "eagle-import:TP_TH_0R9MM")
      (libsource (lib "eagle-import") (part "TP-LC3G"))
    )
    (comp (ref "U13")
      (value "OPA2344EA")
      (footprint "eagle-import:MSO8_AEL")
      (libsource (lib "eagle-import") (part "OPA2344EA"))
    )
    (comp (ref "U14")
      (value "OPA2344EA")
      (footprint "eagle-import:MSO8_AEL")
      (libsource (lib "eagle-import") (part "OPA2344EA"))
    )
    (comp (ref "U15")
      (value "OPA2344EA")
      (footprint "eagle-import:MSO8_AEL")
      (libsource (lib "eagle-import") (part "OPA2344EA"))
    )
    (comp (ref "U16")
      (value "TS5A23159DGS")
      (footprint "eagle-import:MSOP10")
      (libsource (lib "eagle-import") (part "TS5A23159DGS"))
    )
    (comp (ref "U17")
      (value "NJU7108F3")
      (footprint "eagle-import:SC88A")
      (libsource (lib "eagle-import") (part "NJU7108F3"))
    )
    (comp (ref "U18")
      (value "74VHC4052AFT")
      (footprint "eagle-import:TSSOP16-P-044-065A")
      (libsource (lib "eagle-import") (part "744052AFTVHC"))
    )
    (comp (ref "U19")
      (value "TPS3808G01DBV")
      (footprint "eagle-import:SOT-23")
      (libsource (lib "eagle-import") (part "TPS3808GDBV01"))
    )
    (comp (ref "U20")
      (value "TPS79933DDC")
      (footprint "eagle-import:SOT-23-5")
      (libsource (lib "eagle-import") (part "TPS799DDC33"))
    )
    (comp (ref "U21")
      (value "MAX4617CUE+")
      (footprint "eagle-import:TSSOP16_AEL")
      (libsource (lib "eagle-import") (part "MAX4617CUE+"))
    )
    (comp (ref "U22")
      (value "MAX4617CUE+")
      (footprint "eagle-import:TSSOP16_AEL")
      (libsource (lib "eagle-import") (part "MAX4617CUE+"))
    )
    (comp (ref "C60")
      (value "680p")
      (footprint "eagle-import:CM1608")
      (libsource (lib "eagle-import") (part "CSMD1.6X0.8MM"))
    )
    (comp (ref "C61")
      (value "1u/25V")
      (footprint "eagle-import:CM2012")
      (libsource (lib "eagle-import") (part "CSMD2.0X1.2MM"))
    )
    (comp (ref "C62")
      (value "4.7u/25V")
      (footprint "eagle-import:CM2012")
      (libsource (lib "eagle-import") (part "CSMD2.0X1.2MM"))
    )
    (comp (ref "C63")
      (value "0.1u/16V")
      (footprint "eagle-import:CM2012")
      (libsource (lib "eagle-import") (part "CSMD2.0X1.2MM"))
    )
    (comp (ref "C64")
      (value "0.1u/16V")
      (footprint "eagle-import:CM1608")
      (libsource (lib "eagle-import") (part "CSMD1.6X0.8MM"))
    )
    (comp (ref "C65")
      (value "0.1u/16V")
      (footprint "eagle-import:CM2012")
      (libsource (lib "eagle-import") (part "CSMD2.0X1.2MM"))
    )
    (comp (ref "C66")
      (value "0.1u/16V")
      (footprint "eagle-import:CM1608")
      (libsource (lib "eagle-import") (part "CSMD1.6X0.8MM"))
    )
    (comp (ref "C67")
      (value "56u/10V/OS")
      (footprint "eagle-import:PHI_6.3")
      (libsource (lib "eagle-import") (part "C_POL6.3-2.5MM"))
    )
    (comp (ref "C68")
      (value "0.1u/16V")
      (footprint "eagle-import:CM1608")
      (libsource (lib "eagle-import") (part "CSMD1.6X0.8MM"))
    )
    (comp (ref "C69")
      (value "0.1u/16V")
      (footprint "eagle-import:CM1608")
      (libsource (lib "eagle-import") (part "CSMD1.6X0.8MM"))
    )
    (comp (ref "C70")
      (value "0.1u/16V")
      (footprint "eagle-import:CM1608")
      (libsource (lib "eagle-import") (part "CSMD1.6X0.8MM"))
    )
    (comp (ref "C71")
      (value "0.1u/16V")
      (footprint "eagle-import:CM1608")
      (libsource (lib "eagle-import") (part "CSMD1.6X0.8MM"))
    )
    (comp (ref "CN8")
      (value "DF11-6DP-2DSA")
      (footprint "eagle-import:DF11-6DP-2DSA")
      (libsource (lib "eagle-import") (part "DF11-6DP-2DSA"))
    )
    (comp (ref "CN9")
      (value "ZX62-B-5PA")
      (footprint "eagle-import:ZX62-B-5PA")
      (libsource (lib "eagle-import") (part "ZX62-B-5PA"))
    )
    (comp (ref "D5")
      (value "L-93A8CB/1GD")
      (footprint "eagle-import:L-93A8CB")
      (libsource (lib "eagle-import") (part "L-93A8CB/1GD"))
    )
    (comp (ref "D6")
      (value "1SS357")
      (footprint "eagle-import:SOD323-R")
      (libsource (lib "eagle-import") (part "1SS357"))
    )
    (comp (ref "D7")
      (value "1SS357")
      (footprint "eagle-import:SOD323-R")
      (libsource (lib "eagle-import") (part "1SS357"))
    )
    (comp (ref "D8")
      (value "1SS357")
      (footprint "eagle-import:SOD323-R")
      (libsource (lib "eagle-import") (part "1SS357"))
    )
    (comp (ref "D9")
      (value "1SS357")
      (footprint "eagle-import:SOD323-R")
      (libsource (lib "eagle-import") (part "1SS357"))
    )
    (comp (ref "F1")
      (value "RXEF050")
      (footprint "eagle-import:8X3_5.08")
      (libsource (lib "eagle-import") (part "RXEF050"))
    )
    (comp (ref "L8")
      (value "ZJYS51R5-2PBT-01")
      (footprint "eagle-import:ZJYS51-2")
      (libsource (lib "eagle-import") (part "ZJYS5R5-2PBT-01"))
    )
    (comp (ref "M2")
      (value "VAB-3-10")
      (footprint "eagle-import:VAB_3_10_CONTACT")
      (libsource (lib "eagle-import") (part "VAB-3-10"))
    )
    (comp (ref "R86")
      (value "68/THICK")
      (footprint "eagle-import:RM1608")
      (libsource (lib "eagle-import") (part "RSMD1.6X0.8MM"))
    )
    (comp (ref "R87")
      (value "8.2k/THICK")
      (footprint "eagle-import:RM1608")
      (libsource (lib "eagle-import") (part "RSMD1.6X0.8MM"))
    )
    (comp (ref "R88")
      (value "68/THICK")
      (footprint "eagle-import:RM1608")
      (libsource (lib "eagle-import") (part "RSMD1.6X0.8MM"))
    )
    (comp (ref "R89")
      (value "430/LEAD")
      (footprint "eagle-import:0207_2V")
      (libsource (lib "eagle-import") (part "R0207/2V"))
    )
    (comp (ref "R90")
      (value "68/THICK")
      (footprint "eagle-import:RM1608")
      (libsource (lib "eagle-import") (part "RSMD1.6X0.8MM"))
    )
    (comp (ref "R91")
      (value "68/THICK")
      (footprint "eagle-import:RM1608")
      (libsource (lib "eagle-import") (part "RSMD1.6X0.8MM"))
    )
    (comp (ref "R92")
      (value "8.2k/THICK")
      (footprint "eagle-import:RM1608")
      (libsource (lib "eagle-import") (part "RSMD1.6X0.8MM"))
    )
    (comp (ref "R93")
      (value "68/THICK")
      (footprint "eagle-import:RM1608")
      (libsource (lib "eagle-import") (part "RSMD1.6X0.8MM"))
    )
    (comp (ref "R94")
      (value "68/THICK")
      (footprint "eagle-import:RM1608")
      (libsource (lib "eagle-import") (part "RSMD1.6X0.8MM"))
    )
    (comp (ref "R95")
      (value "68/THICK")
      (footprint "eagle-import:RM1608")
      (libsource (lib "eagle-import") (part "RSMD1.6X0.8MM"))
    )
    (comp (ref "R96")
      (value "1k/THICK")
      (footprint "eagle-import:RM1608")
      (libsource (lib "eagle-import") (part "RSMD1.6X0.8MM"))
    )
    (comp (ref "R97")
      (value "330k")
      (footprint "eagle-import:RM1608")
      (libsource (lib "eagle-import") (part "RSMD1.6X0.8MM"))
    )
    (comp (ref "R98")
      (value "300/THICK")
      (footprint "eagle-import:RM1608")
      (libsource (lib "eagle-import") (part "RSMD1.6X0.8MM"))
    )
    (comp (ref "R99")
      (value "750k")
      (footprint "eagle-import:RM1608")
      (libsource (lib "eagle-import") (part "RSMD1.6X0.8MM"))
    )
    (comp (ref "R100")
      (value "2.2k/THICK")
      (footprint "eagle-import:RM1608")
      (libsource (lib "eagle-import") (part "RSMD1.6X0.8MM"))
    )
    (comp (ref "R101")
      (value "100k/THICK")
      (footprint "eagle-import:RM1608")
      (libsource (lib "eagle-import") (part "RSMD1.6X0.8MM"))
    )
    (comp (ref "R102")
      (value "100k/THICK")
      (footprint "eagle-import:RM1608")
      (libsource (lib "eagle-import") (part "RSMD1.6X0.8MM"))
    )
    (comp (ref "R103")
      (value "240k")
      (footprint "eagle-import:RM1608")
      (libsource (lib "eagle-import") (part "RSMD1.6X0.8MM"))
    )
    (comp (ref "R104")
      (value "100k/THICK")
      (footprint "eagle-import:RM1608")
      (libsource (lib "eagle-import") (part "RSMD1.6X0.8MM"))
    )
    (comp (ref "R105")
      (value "1k/THICK")
      (footprint "eagle-import:RM1608")
      (libsource (lib "eagle-import") (part "RSMD1.6X0.8MM"))
    )
    (comp (ref "R106")
      (value "100k/THICK")
      (footprint "eagle-import:RM1608")
      (libsource (lib "eagle-import") (part "RSMD1.6X0.8MM"))
    )
    (comp (ref "R107")
      (value "100k/THICK")
      (footprint "eagle-import:RM1608")
      (libsource (lib "eagle-import") (part "RSMD1.6X0.8MM"))
    )
    (comp (ref "R108")
      (value "100k/THICK")
      (footprint "eagle-import:RM1608")
      (libsource (lib "eagle-import") (part "RSMD1.6X0.8MM"))
    )
    (comp (ref "SW6")
      (value "A-18AV")
      (footprint "eagle-import:A-12_")
      (libsource (lib "eagle-import") (part "A-1V8A"))
    )
    (comp (ref "TP18")
      (value "TP-LC3G")
      (footprint "eagle-import:TP_TH_0R9MM")
      (libsource (lib "eagle-import") (part "TP-LC3G"))
    )
    (comp (ref "TP19")
      (value "TP-LC3G")
      (footprint "eagle-import:TP_TH_0R9MM")
      (libsource (lib "eagle-import") (part "TP-LC3G"))
    )
    (comp (ref "U30")
      (value "TLP291GR")
      (footprint "eagle-import:SO4(11-3C1)(TOSHIBA)")
      (libsource (lib "eagle-import") (part "TLP291GR"))
    )
    (comp (ref "U31")
      (value "HFBR-1521Z")
      (footprint "eagle-import:HFBR-X52X")
      (libsource (lib "eagle-import") (part "HFBR-1521Z"))
    )
    (comp (ref "U32")
      (value "TLP291GR")
      (footprint "eagle-import:SO4(11-3C1)(TOSHIBA)")
      (libsource (lib "eagle-import") (part "TLP291GR"))
    )
    (comp (ref "U33")
      (value "74HC540AF")
      (footprint "eagle-import:SO20_300MIL")
      (libsource (lib "eagle-import") (part "74540AFAC"))
    )
    (comp (ref "U34")
      (value "HFBR-2521Z")
      (footprint "eagle-import:HFBR-X52X")
      (libsource (lib "eagle-import") (part "HFBR-2521Z"))
    )
    (comp (ref "U35")
      (value "TLP291GR")
      (footprint "eagle-import:SO4(11-3C1)(TOSHIBA)")
      (libsource (lib "eagle-import") (part "TLP291GR"))
    )
    (comp (ref "U36")
      (value "74HC123AF")
      (footprint "eagle-import:SO16_300MIL")
      (libsource (lib "eagle-import") (part "74123AFHC"))
    )
    (comp (ref "U37")
      (value "74HC123AF")
      (footprint "eagle-import:SO16_300MIL")
      (libsource (lib "eagle-import") (part "74123AFHC"))
    )
    (comp (ref "U38")
      (value "74HC14AF")
      (footprint "eagle-import:SO14_300MIL")
      (libsource (lib "eagle-import") (part "7414AFHC"))
    )
    (comp (ref "C1")
      (value "680p")
      (footprint "eagle-import:CM1608")
      (libsource (lib "eagle-import") (part "CSMD1.6X0.8MM"))
    )
    (comp (ref "C2")
      (value "1u/25V")
      (footprint "eagle-import:CM2012")
      (libsource (lib "eagle-import") (part "CSMD2.0X1.2MM"))
    )
    (comp (ref "C3")
      (value "0.1u/16V")
      (footprint "eagle-import:CM1608")
      (libsource (lib "eagle-import") (part "CSMD1.6X0.8MM"))
    )
    (comp (ref "C4")
      (value "1u/16V")
      (footprint "eagle-import:CM2012")
      (libsource (lib "eagle-import") (part "CSMD2.0X1.2MM"))
    )
    (comp (ref "C5")
      (value "0.1u/16V")
      (footprint "eagle-import:CM1608")
      (libsource (lib "eagle-import") (part "CSMD1.6X0.8MM"))
    )
    (comp (ref "C6")
      (value "1u/25V")
      (footprint "eagle-import:CM1608")
      (libsource (lib "eagle-import") (part "CSMD1.6X0.8MM"))
    )
    (comp (ref "C7")
      (value "56u/10V/OS")
      (footprint "eagle-import:PHI_6.3")
      (libsource (lib "eagle-import") (part "C_POL6.3-2.5MM"))
    )
    (comp (ref "C8")
      (value "0.1u/16V")
      (footprint "eagle-import:CM1608")
      (libsource (lib "eagle-import") (part "CSMD1.6X0.8MM"))
    )
    (comp (ref "C9")
      (value "0.1u/16V")
      (footprint "eagle-import:CM1608")
      (libsource (lib "eagle-import") (part "CSMD1.6X0.8MM"))
    )
    (comp (ref "C10")
      (value "0.1u/16V")
      (footprint "eagle-import:CM1608")
      (libsource (lib "eagle-import") (part "CSMD1.6X0.8MM"))
    )
    (comp (ref "C11")
      (value "0.1u/16V")
      (footprint "eagle-import:CM1608")
      (libsource (lib "eagle-import") (part "CSMD1.6X0.8MM"))
    )
    (comp (ref "C12")
      (value "0.1u/16V")
      (footprint "eagle-import:CM1608")
      (libsource (lib "eagle-import") (part "CSMD1.6X0.8MM"))
    )
    (comp (ref "D1")
      (value "1SS357")
      (footprint "eagle-import:SOD323-R")
      (libsource (lib "eagle-import") (part "1SS357"))
    )
    (comp (ref "D2")
      (value "1SS357")
      (footprint "eagle-import:SOD323-R")
      (libsource (lib "eagle-import") (part "1SS357"))
    )
    (comp (ref "L1")
      (value "ZJYS51R5-2PBT-01")
      (footprint "eagle-import:ZJYS51-2")
      (libsource (lib "eagle-import") (part "ZJYS5R5-2PBT-01"))
    )
    (comp (ref "R1")
      (value "68/THICK")
      (footprint "eagle-import:RM1608")
      (libsource (lib "eagle-import") (part "RSMD1.6X0.8MM"))
    )
    (comp (ref "R2")
      (value "8.2k/THICK")
      (footprint "eagle-import:RM1608")
      (libsource (lib "eagle-import") (part "RSMD1.6X0.8MM"))
    )
    (comp (ref "R3")
      (value "2k/THICK")
      (footprint "eagle-import:RM1608")
      (libsource (lib "eagle-import") (part "RSMD1.6X0.8MM"))
    )
    (comp (ref "R4")
      (value "68/THICK")
      (footprint "eagle-import:RM1608")
      (libsource (lib "eagle-import") (part "RSMD1.6X0.8MM"))
    )
    (comp (ref "R5")
      (value "430/LEAD")
      (footprint "eagle-import:0207_2V")
      (libsource (lib "eagle-import") (part "R0207/2V"))
    )
    (comp (ref "R6")
      (value "68/THICK")
      (footprint "eagle-import:RM1608")
      (libsource (lib "eagle-import") (part "RSMD1.6X0.8MM"))
    )
    (comp (ref "R7")
      (value "68/THICK")
      (footprint "eagle-import:RM1608")
      (libsource (lib "eagle-import") (part "RSMD1.6X0.8MM"))
    )
    (comp (ref "R8")
      (value "68/THICK")
      (footprint "eagle-import:RM1608")
      (libsource (lib "eagle-import") (part "RSMD1.6X0.8MM"))
    )
    (comp (ref "R9")
      (value "8.2k/THICK")
      (footprint "eagle-import:RM1608")
      (libsource (lib "eagle-import") (part "RSMD1.6X0.8MM"))
    )
    (comp (ref "R10")
      (value "2k/THICK")
      (footprint "eagle-import:RM1608")
      (libsource (lib "eagle-import") (part "RSMD1.6X0.8MM"))
    )
    (comp (ref "R11")
      (value "68/THICK")
      (footprint "eagle-import:RM1608")
      (libsource (lib "eagle-import") (part "RSMD1.6X0.8MM"))
    )
    (comp (ref "R12")
      (value "68/THICK")
      (footprint "eagle-import:RM1608")
      (libsource (lib "eagle-import") (part "RSMD1.6X0.8MM"))
    )
    (comp (ref "R13")
      (value "3.3k/THICK")
      (footprint "eagle-import:RM1608")
      (libsource (lib "eagle-import") (part "RSMD1.6X0.8MM"))
    )
    (comp (ref "R14")
      (value "2.7k/THICK")
      (footprint "eagle-import:RM1608")
      (libsource (lib "eagle-import") (part "RSMD1.6X0.8MM"))
    )
    (comp (ref "R15")
      (value "3.3k/THICK")
      (footprint "eagle-import:RM1608")
      (libsource (lib "eagle-import") (part "RSMD1.6X0.8MM"))
    )
    (comp (ref "R16")
      (value "2.7k/THICK")
      (footprint "eagle-import:RM1608")
      (libsource (lib "eagle-import") (part "RSMD1.6X0.8MM"))
    )
    (comp (ref "R17")
      (value "100k/THICK")
      (footprint "eagle-import:RM1608")
      (libsource (lib "eagle-import") (part "RSMD1.6X0.8MM"))
    )
    (comp (ref "R18")
      (value "100k/THICK")
      (footprint "eagle-import:RM1608")
      (libsource (lib "eagle-import") (part "RSMD1.6X0.8MM"))
    )
    (comp (ref "R19")
      (value "100k/THICK")
      (footprint "eagle-import:RM1608")
      (libsource (lib "eagle-import") (part "RSMD1.6X0.8MM"))
    )
    (comp (ref "R20")
      (value "51k")
      (footprint "eagle-import:RM1608")
      (libsource (lib "eagle-import") (part "RSMD1.6X0.8MM"))
    )
    (comp (ref "R21")
      (value "100k")
      (footprint "eagle-import:RM1608")
      (libsource (lib "eagle-import") (part "RSMD1.6X0.8MM"))
    )
    (comp (ref "R22")
      (value "51k")
      (footprint "eagle-import:RM1608")
      (libsource (lib "eagle-import") (part "RSMD1.6X0.8MM"))
    )
    (comp (ref "R23")
      (value "1k/THICK")
      (footprint "eagle-import:RM1608")
      (libsource (lib "eagle-import") (part "RSMD1.6X0.8MM"))
    )
    (comp (ref "R24")
      (value "100k")
      (footprint "eagle-import:RM1608")
      (libsource (lib "eagle-import") (part "RSMD1.6X0.8MM"))
    )
    (comp (ref "R25")
      (value "100k/THICK")
      (footprint "eagle-import:RM1608")
      (libsource (lib "eagle-import") (part "RSMD1.6X0.8MM"))
    )
    (comp (ref "R26")
      (value "51k/THICK")
      (footprint "eagle-import:RM1608")
      (libsource (lib "eagle-import") (part "RSMD1.6X0.8MM"))
    )
    (comp (ref "R27")
      (value "1M/THICK")
      (footprint "eagle-import:RM1608")
      (libsource (lib "eagle-import") (part "RSMD1.6X0.8MM"))
    )
    (comp (ref "R28")
      (value "10k/THICK")
      (footprint "eagle-import:RM1608")
      (libsource (lib "eagle-import") (part "RSMD1.6X0.8MM"))
    )
    (comp (ref "R29")
      (value "10k/THICK")
      (footprint "eagle-import:RM1608")
      (libsource (lib "eagle-import") (part "RSMD1.6X0.8MM"))
    )
    (comp (ref "TP1")
      (value "TP-LC3G")
      (footprint "eagle-import:TP_TH_0R9MM")
      (libsource (lib "eagle-import") (part "TP-LC3G"))
    )
    (comp (ref "TP2")
      (value "TP-LC3G")
      (footprint "eagle-import:TP_TH_0R9MM")
      (libsource (lib "eagle-import") (part "TP-LC3G"))
    )
    (comp (ref "TP3")
      (value "TP-LC3G")
      (footprint "eagle-import:TP_TH_0R9MM")
      (libsource (lib "eagle-import") (part "TP-LC3G"))
    )
    (comp (ref "TR1")
      (value "2SC2712GR")
      (footprint "eagle-import:SOT23-BEC")
      (libsource (lib "eagle-import") (part "2SC2712GR"))
    )
    (comp (ref "U1")
      (value "TLP291GR")
      (footprint "eagle-import:SO4(11-3C1)(TOSHIBA)")
      (libsource (lib "eagle-import") (part "TLP291GR"))
    )
    (comp (ref "U2")
      (value "TC7W14FU")
      (footprint "eagle-import:SSOP8-P-065")
      (libsource (lib "eagle-import") (part "TC7WZ14FU"))
    )
    (comp (ref "U3")
      (value "HFBR-1521Z")
      (footprint "eagle-import:HFBR-X52X")
      (libsource (lib "eagle-import") (part "HFBR-1521Z"))
    )
    (comp (ref "U4")
      (value "74HC540AF")
      (footprint "eagle-import:SO20_300MIL")
      (libsource (lib "eagle-import") (part "74540AFHC"))
    )
    (comp (ref "U5")
      (value "TLP291GR")
      (footprint "eagle-import:SO4(11-3C1)(TOSHIBA)")
      (libsource (lib "eagle-import") (part "TLP291GR"))
    )
    (comp (ref "U6")
      (value "HFBR-2521Z")
      (footprint "eagle-import:HFBR-X52X")
      (libsource (lib "eagle-import") (part "HFBR-2521Z"))
    )
    (comp (ref "U7")
      (value "TLP291GR")
      (footprint "eagle-import:SO4(11-3C1)(TOSHIBA)")
      (libsource (lib "eagle-import") (part "TLP291GR"))
    )
    (comp (ref "U8")
      (value "TLP291GR")
      (footprint "eagle-import:SO4(11-3C1)(TOSHIBA)")
      (libsource (lib "eagle-import") (part "TLP291GR"))
    )
    (comp (ref "U9")
      (value "74HC74AF")
      (footprint "eagle-import:SO14_300MIL")
      (libsource (lib "eagle-import") (part "7474AFHC"))
    )
    (comp (ref "U10")
      (value "NJU7108F3")
      (footprint "eagle-import:SC88A")
      (libsource (lib "eagle-import") (part "NJU7108F3"))
    )
    (comp (ref "U11")
      (value "74HC123AF")
      (footprint "eagle-import:SO16_300MIL")
      (libsource (lib "eagle-import") (part "74123AFHC"))
    )
    (comp (ref "U12")
      (value "TC7S00FU")
      (footprint "eagle-import:SSOP5-P-065A(USV)")
      (libsource (lib "eagle-import") (part "TC7S00FU"))
    )
    (comp (ref "C45")
      (value "0.1u/16V")
      (footprint "eagle-import:CM1608")
      (libsource (lib "eagle-import") (part "CSMD1.6X0.8MM"))
    )
    (comp (ref "C46")
      (value "0.1u/16V")
      (footprint "eagle-import:CM1608")
      (libsource (lib "eagle-import") (part "CSMD1.6X0.8MM"))
    )
    (comp (ref "C47")
      (value "0.1u/16V")
      (footprint "eagle-import:CM1608")
      (libsource (lib "eagle-import") (part "CSMD1.6X0.8MM"))
    )
    (comp (ref "C48")
      (value "0.1u/16V")
      (footprint "eagle-import:CM1608")
      (libsource (lib "eagle-import") (part "CSMD1.6X0.8MM"))
    )
    (comp (ref "C49")
      (value "0.1u/16V")
      (footprint "eagle-import:CM1608")
      (libsource (lib "eagle-import") (part "CSMD1.6X0.8MM"))
    )
    (comp (ref "C50")
      (value "0.1u/16V")
      (footprint "eagle-import:CM1608")
      (libsource (lib "eagle-import") (part "CSMD1.6X0.8MM"))
    )
    (comp (ref "C51")
      (value "0.1u/16V")
      (footprint "eagle-import:CM1608")
      (libsource (lib "eagle-import") (part "CSMD1.6X0.8MM"))
    )
    (comp (ref "C52")
      (value "0.1u/16V")
      (footprint "eagle-import:CM1608")
      (libsource (lib "eagle-import") (part "CSMD1.6X0.8MM"))
    )
    (comp (ref "C53")
      (value "0.1u/16V")
      (footprint "eagle-import:CM1608")
      (libsource (lib "eagle-import") (part "CSMD1.6X0.8MM"))
    )
    (comp (ref "C54")
      (value "0.1u/16V")
      (footprint "eagle-import:CM1608")
      (libsource (lib "eagle-import") (part "CSMD1.6X0.8MM"))
    )
    (comp (ref "C55")
      (value "0.1u/16V")
      (footprint "eagle-import:CM1608")
      (libsource (lib "eagle-import") (part "CSMD1.6X0.8MM"))
    )
    (comp (ref "C56")
      (value "0.1u/16V")
      (footprint "eagle-import:CM1608")
      (libsource (lib "eagle-import") (part "CSMD1.6X0.8MM"))
    )
    (comp (ref "C57")
      (value "0.1u/16V")
      (footprint "eagle-import:CM1608")
      (libsource (lib "eagle-import") (part "CSMD1.6X0.8MM"))
    )
    (comp (ref "C58")
      (value "10n")
      (footprint "eagle-import:CM2012")
      (libsource (lib "eagle-import") (part "CSMD2.0X1.2MM"))
    )
    (comp (ref "C59")
      (value "10u/25V")
      (footprint "eagle-import:CM3216")
      (libsource (lib "eagle-import") (part "CSMD3.2X1.6MM"))
    )
    (comp (ref "CN7")
      (value "XJ8C-1011")
      (footprint "eagle-import:PIN_HEADER_10PIN")
      (libsource (lib "eagle-import") (part "PIN_HEADER_10PIN"))
    )
    (comp (ref "R74")
      (value "---")
      (footprint "eagle-import:RM1608")
      (libsource (lib "eagle-import") (part "RSMD1.6X0.8MM"))
    )
    (comp (ref "R75")
      (value "10k/THICK")
      (footprint "eagle-import:RM1608")
      (libsource (lib "eagle-import") (part "RSMD1.6X0.8MM"))
    )
    (comp (ref "R76")
      (value "10k/THICK")
      (footprint "eagle-import:RM1608")
      (libsource (lib "eagle-import") (part "RSMD1.6X0.8MM"))
    )
    (comp (ref "R77")
      (value "1k/THICK")
      (footprint "eagle-import:RM1608")
      (libsource (lib "eagle-import") (part "RSMD1.6X0.8MM"))
    )
    (comp (ref "R78")
      (value "100k/THICK")
      (footprint "eagle-import:RM1608")
      (libsource (lib "eagle-import") (part "RSMD1.6X0.8MM"))
    )
    (comp (ref "R79")
      (value "10k/THICK")
      (footprint "eagle-import:RM1608")
      (libsource (lib "eagle-import") (part "RSMD1.6X0.8MM"))
    )
    (comp (ref "R80")
      (value "100k/THICK")
      (footprint "eagle-import:RM1608")
      (libsource (lib "eagle-import") (part "RSMD1.6X0.8MM"))
    )
    (comp (ref "R81")
      (value "10k/THICK")
      (footprint "eagle-import:RM1608")
      (libsource (lib "eagle-import") (part "RSMD1.6X0.8MM"))
    )
    (comp (ref "R82")
      (value "100k/THICK")
      (footprint "eagle-import:RM1608")
      (libsource (lib "eagle-import") (part "RSMD1.6X0.8MM"))
    )
    (comp (ref "R83")
      (value "10k/THICK")
      (footprint "eagle-import:RM1608")
      (libsource (lib "eagle-import") (part "RSMD1.6X0.8MM"))
    )
    (comp (ref "R84")
      (value "100k/THICK")
      (footprint "eagle-import:RM1608")
      (libsource (lib "eagle-import") (part "RSMD1.6X0.8MM"))
    )
    (comp (ref "R85")
      (value "10k/THICK")
      (footprint "eagle-import:RM1608")
      (libsource (lib "eagle-import") (part "RSMD1.6X0.8MM"))
    )
    (comp (ref "SW2")
      (value "A-12AV")
      (footprint "eagle-import:A-12_")
      (libsource (lib "eagle-import") (part "A-1V2A"))
    )
    (comp (ref "SW3")
      (value "A-12AV")
      (footprint "eagle-import:A-12_")
      (libsource (lib "eagle-import") (part "A-1V2A"))
    )
    (comp (ref "SW4")
      (value "---")
      (footprint "eagle-import:A-12_")
      (libsource (lib "eagle-import") (part "A-1V2A"))
    )
    (comp (ref "SW5")
      (value "---")
      (footprint "eagle-import:A-12_")
      (libsource (lib "eagle-import") (part "A-1V2A"))
    )
    (comp (ref "TP12")
      (value "TP-1PAD")
      (footprint "eagle-import:TP_PAD_1MM")
      (libsource (lib "eagle-import") (part "TP-1PAD"))
    )
    (comp (ref "TP13")
      (value "TP-1PAD")
      (footprint "eagle-import:TP_PAD_1MM")
      (libsource (lib "eagle-import") (part "TP-1PAD"))
    )
    (comp (ref "TP14")
      (value "TP-1PAD")
      (footprint "eagle-import:TP_PAD_1MM")
      (libsource (lib "eagle-import") (part "TP-1PAD"))
    )
    (comp (ref "TP15")
      (value "TP-1PAD")
      (footprint "eagle-import:TP_PAD_1MM")
      (libsource (lib "eagle-import") (part "TP-1PAD"))
    )
    (comp (ref "TP16")
      (value "TP-1PAD")
      (footprint "eagle-import:TP_PAD_1MM")
      (libsource (lib "eagle-import") (part "TP-1PAD"))
    )
    (comp (ref "TP17")
      (value "TP-1PAD")
      (footprint "eagle-import:TP_PAD_1MM")
      (libsource (lib "eagle-import") (part "TP-1PAD"))
    )
    (comp (ref "U28")
      (value "5M80ZT100")
      (footprint "eagle-import:QFP100_0.5")
      (libsource (lib "eagle-import") (part "5M160ZT100"))
    )
    (comp (ref "U29")
      (value "TPS79918DDC")
      (footprint "eagle-import:SOT-23-5")
      (libsource (lib "eagle-import") (part "TPS799DDC18"))
    )
  )
  (nets
    (net (code "1") (name "0+") (class "Default")
      (node (ref "C15") (pin "1") (pinfunction "1_1") (pintype "passive"))
      (node (ref "L2") (pin "4") (pinfunction "1_4") (pintype "passive"))
      (node (ref "U22") (pin "13") (pinfunction "0_13") (pintype "bidirectional"))
      (node (ref "U23") (pin "1") (pinfunction "OUT+_1") (pintype "bidirectional"))
    )
    (net (code "2") (name "0-") (class "Default")
      (node (ref "C15") (pin "2") (pinfunction "2_2") (pintype "passive"))
      (node (ref "L2") (pin "3") (pinfunction "3_3") (pintype "passive"))
      (node (ref "U21") (pin "13") (pinfunction "0_13") (pintype "bidirectional"))
      (node (ref "U23") (pin "2") (pinfunction "OUT-_2") (pintype "bidirectional"))
    )
    (net (code "3") (name "0V") (class "Default")
      (node (ref "C16") (pin "2") (pinfunction "2_2") (pintype "passive"))
      (node (ref "C21") (pin "2") (pinfunction "2_2") (pintype "passive"))
      (node (ref "C28") (pin "POS") (pinfunction "POS_POS") (pintype "passive"))
      (node (ref "D3") (pin "1") (pinfunction "A_1") (pintype "passive"))
      (node (ref "D3") (pin "2") (pinfunction "C_2") (pintype "passive"))
      (node (ref "R30") (pin "1") (pinfunction "1_1") (pintype "passive"))
      (node (ref "R35") (pin "1") (pinfunction "1_1") (pintype "passive"))
      (node (ref "R39") (pin "1") (pinfunction "1_1") (pintype "passive"))
      (node (ref "R45") (pin "1") (pinfunction "1_1") (pintype "passive"))
      (node (ref "R46") (pin "1") (pinfunction "1_1") (pintype "passive"))
      (node (ref "R69") (pin "2") (pinfunction "2_2") (pintype "passive"))
      (node (ref "TP8") (pin "1") (pinfunction "MP_1") (pintype "passive"))
      (node (ref "U13") (pin "5") (pinfunction "+IN_5") (pintype "input"))
      (node (ref "U15") (pin "5") (pinfunction "+IN_5") (pintype "input"))
    )
    (net (code "4") (name "1+") (class "Default")
      (node (ref "C17") (pin "1") (pinfunction "1_1") (pintype "passive"))
      (node (ref "L3") (pin "4") (pinfunction "1_4") (pintype "passive"))
      (node (ref "U22") (pin "14") (pinfunction "1_14") (pintype "bidirectional"))
      (node (ref "U26") (pin "1") (pinfunction "OUT+_1") (pintype "bidirectional"))
    )
    (net (code "5") (name "1-") (class "Default")
      (node (ref "C17") (pin "2") (pinfunction "2_2") (pintype "passive"))
      (node (ref "L3") (pin "3") (pinfunction "3_3") (pintype "passive"))
      (node (ref "U21") (pin "14") (pinfunction "1_14") (pintype "bidirectional"))
      (node (ref "U26") (pin "2") (pinfunction "OUT-_2") (pintype "bidirectional"))
    )
    (net (code "6") (name "2+") (class "Default")
      (node (ref "C20") (pin "1") (pinfunction "1_1") (pintype "passive"))
      (node (ref "L4") (pin "4") (pinfunction "1_4") (pintype "passive"))
      (node (ref "U22") (pin "15") (pinfunction "2_15") (pintype "bidirectional"))
      (node (ref "U24") (pin "1") (pinfunction "OUT+_1") (pintype "bidirectional"))
    )
    (net (code "7") (name "2-") (class "Default")
      (node (ref "C20") (pin "2") (pinfunction "2_2") (pintype "passive"))
      (node (ref "L4") (pin "3") (pinfunction "3_3") (pintype "passive"))
      (node (ref "U21") (pin "15") (pinfunction "2_15") (pintype "bidirectional"))
      (node (ref "U24") (pin "2") (pinfunction "OUT-_2") (pintype "bidirectional"))
    )
    (net (code "8") (name "3+") (class "Default")
      (node (ref "C22") (pin "1") (pinfunction "1_1") (pintype "passive"))
      (node (ref "L5") (pin "4") (pinfunction "1_4") (pintype "passive"))
      (node (ref "U22") (pin "12") (pinfunction "3_12") (pintype "bidirectional"))
      (node (ref "U27") (pin "1") (pinfunction "OUT+_1") (pintype "bidirectional"))
    )
    (net (code "9") (name "3-") (class "Default")
      (node (ref "C22") (pin "2") (pinfunction "2_2") (pintype "passive"))
      (node (ref "L5") (pin "3") (pinfunction "3_3") (pintype "passive"))
      (node (ref "U21") (pin "12") (pinfunction "3_12") (pintype "bidirectional"))
      (node (ref "U27") (pin "2") (pinfunction "OUT-_2") (pintype "bidirectional"))
    )
    (net (code "10") (name "4+") (class "Default")
      (node (ref "C24") (pin "1") (pinfunction "1_1") (pintype "passive"))
      (node (ref "L6") (pin "4") (pinfunction "1_4") (pintype "passive"))
      (node (ref "U22") (pin "1") (pinfunction "4_1") (pintype "bidirectional"))
      (node (ref "U25") (pin "1") (pinfunction "OUT+_1") (pintype "bidirectional"))
    )
    (net (code "11") (name "4-") (class "Default")
      (node (ref "C24") (pin "2") (pinfunction "2_2") (pintype "passive"))
      (node (ref "L6") (pin "3") (pinfunction "3_3") (pintype "passive"))
      (node (ref "U21") (pin "1") (pinfunction "4_1") (pintype "bidirectional"))
      (node (ref "U25") (pin "2") (pinfunction "OUT-_2") (pintype "bidirectional"))
    )
    (net (code "12") (name "80_POWER") (class "Default")
      (node (ref "R73") (pin "2") (pinfunction "2_2") (pintype "passive"))
      (node (ref "TP11") (pin "1") (pinfunction "MP_1") (pintype "passive"))
      (node (ref "U20") (pin "3") (pinfunction "EN_3") (pintype "input"))
    )
    (net (code "13") (name "AGND") (class "Default")
      (node (ref "C23") (pin "1") (pinfunction "1_1") (pintype "passive"))
      (node (ref "C25") (pin "2") (pinfunction "2_2") (pintype "passive"))
      (node (ref "C26") (pin "2") (pinfunction "2_2") (pintype "passive"))
      (node (ref "C27") (pin "2") (pinfunction "2_2") (pintype "passive"))
      (node (ref "C28") (pin "NEG") (pinfunction "NEG_NEG") (pintype "passive"))
      (node (ref "C29") (pin "2") (pinfunction "2_2") (pintype "passive"))
      (node (ref "C30") (pin "NEG") (pinfunction "NEG_NEG") (pintype "passive"))
      (node (ref "C31") (pin "2") (pinfunction "2_2") (pintype "passive"))
      (node (ref "C32") (pin "2") (pinfunction "2_2") (pintype "passive"))
      (node (ref "C33") (pin "2") (pinfunction "2_2") (pintype "passive"))
      (node (ref "C34") (pin "2") (pinfunction "2_2") (pintype "passive"))
      (node (ref "C35") (pin "2") (pinfunction "2_2") (pintype "passive"))
      (node (ref "C36") (pin "2") (pinfunction "2_2") (pintype "passive"))
      (node (ref "C37") (pin "2") (pinfunction "2_2") (pintype "passive"))
      (node (ref "C38") (pin "2") (pinfunction "2_2") (pintype "passive"))
      (node (ref "C39") (pin "2") (pinfunction "2_2") (pintype "passive"))
      (node (ref "C40") (pin "2") (pinfunction "2_2") (pintype "passive"))
      (node (ref "C41") (pin "2") (pinfunction "2_2") (pintype "passive"))
      (node (ref "C42") (pin "2") (pinfunction "2_2") (pintype "passive"))
      (node (ref "C43") (pin "2") (pinfunction "2_2") (pintype "passive"))
      (node (ref "C44") (pin "2") (pinfunction "2_2") (pintype "passive"))
      (node (ref "C45") (pin "2") (pinfunction "2_2") (pintype "passive"))
      (node (ref "C46") (pin "2") (pinfunction "2_2") (pintype "passive"))
      (node (ref "C47") (pin "1") (pinfunction "1_1") (pintype "passive"))
      (node (ref "C48") (pin "2") (pinfunction "2_2") (pintype "passive"))
      (node (ref "C49") (pin "1") (pinfunction "1_1") (pintype "passive"))
      (node (ref "C50") (pin "2") (pinfunction "2_2") (pintype "passive"))
      (node (ref "C51") (pin "1") (pinfunction "1_1") (pintype "passive"))
      (node (ref "C52") (pin "2") (pinfunction "2_2") (pintype "passive"))
      (node (ref "C53") (pin "2") (pinfunction "2_2") (pintype "passive"))
      (node (ref "C54") (pin "1") (pinfunction "1_1") (pintype "passive"))
      (node (ref "C55") (pin "2") (pinfunction "2_2") (pintype "passive"))
      (node (ref "C56") (pin "2") (pinfunction "2_2") (pintype "passive"))
      (node (ref "C57") (pin "2") (pinfunction "2_2") (pintype "passive"))
      (node (ref "C58") (pin "2") (pinfunction "2_2") (pintype "passive"))
      (node (ref "C59") (pin "2") (pinfunction "2_2") (pintype "passive"))
      (node (ref "CN7") (pin "10") (pinfunction "10_10") (pintype "bidirectional"))
      (node (ref "CN7") (pin "2") (pinfunction "2_2") (pintype "bidirectional"))
      (node (ref "L7") (pin "2") (pinfunction "4_2") (pintype "passive"))
      (node (ref "R47") (pin "1") (pinfunction "1_1") (pintype "passive"))
      (node (ref "R56") (pin "1") (pinfunction "1_1") (pintype "passive"))
      (node (ref "R60") (pin "1") (pinfunction "1_1") (pintype "passive"))
      (node (ref "R61") (pin "1") (pinfunction "1_1") (pintype "passive"))
      (node (ref "R63") (pin "1") (pinfunction "1_1") (pintype "passive"))
      (node (ref "R64") (pin "1") (pinfunction "1_1") (pintype "passive"))
      (node (ref "R70") (pin "1") (pinfunction "1_1") (pintype "passive"))
      (node (ref "R71") (pin "1") (pinfunction "1_1") (pintype "passive"))
      (node (ref "R77") (pin "1") (pinfunction "1_1") (pintype "passive"))
      (node (ref "SW2") (pin "3") (pinfunction "NC_3") (pintype "passive"))
      (node (ref "SW2") (pin "7") (pinfunction "BRACKET_7") (pintype "passive"))
      (node (ref "SW2") (pin "8") (pinfunction "BRACKET_8") (pintype "passive"))
      (node (ref "SW3") (pin "3") (pinfunction "NC_3") (pintype "passive"))
      (node (ref "SW3") (pin "7") (pinfunction "BRACKET_7") (pintype "passive"))
      (node (ref "SW3") (pin "8") (pinfunction "BRACKET_8") (pintype "passive"))
      (node (ref "SW4") (pin "3") (pinfunction "NC_3") (pintype "passive"))
      (node (ref "SW4") (pin "7") (pinfunction "BRACKET_7") (pintype "passive"))
      (node (ref "SW4") (pin "8") (pinfunction "BRACKET_8") (pintype "passive"))
      (node (ref "SW5") (pin "3") (pinfunction "NC_3") (pintype "passive"))
      (node (ref "SW5") (pin "7") (pinfunction "BRACKET_7") (pintype "passive"))
      (node (ref "SW5") (pin "8") (pinfunction "BRACKET_8") (pintype "passive"))
      (node (ref "TP10") (pin "1") (pinfunction "MP_1") (pintype "passive"))
      (node (ref "U13") (pin "4") (pinfunction "V-_4") (pintype "power_in"))
      (node (ref "U14") (pin "4") (pinfunction "V-_4") (pintype "power_in"))
      (node (ref "U15") (pin "4") (pinfunction "V-_4") (pintype "power_in"))
      (node (ref "U16") (pin "3") (pinfunction "V-_3") (pintype "power_in"))
      (node (ref "U17") (pin "2") (pinfunction "V-_2") (pintype "power_in"))
      (node (ref "U18") (pin "6") (pinfunction "INH_6") (pintype "input"))
      (node (ref "U18") (pin "7") (pinfunction "GND_7") (pintype "power_in"))
      (node (ref "U18") (pin "8") (pinfunction "GND_8") (pintype "input"))
      (node (ref "U19") (pin "2") (pinfunction "GND_2") (pintype "power_in"))
      (node (ref "U20") (pin "2") (pinfunction "GND_2") (pintype "passive"))
      (node (ref "U21") (pin "8") (pinfunction "V-_8") (pintype "power_in"))
      (node (ref "U22") (pin "8") (pinfunction "V-_8") (pintype "power_in"))
      (node (ref "U23") (pin "10") (pinfunction "GND1_10") (pintype "bidirectional"))
      (node (ref "U23") (pin "12") (pinfunction "GND2_12") (pintype "bidirectional"))
      (node (ref "U23") (pin "8") (pinfunction "GND0_8") (pintype "bidirectional"))
      (node (ref "U24") (pin "10") (pinfunction "GND1_10") (pintype "bidirectional"))
      (node (ref "U24") (pin "12") (pinfunction "GND2_12") (pintype "bidirectional"))
      (node (ref "U24") (pin "8") (pinfunction "GND0_8") (pintype "bidirectional"))
      (node (ref "U25") (pin "10") (pinfunction "GND1_10") (pintype "bidirectional"))
      (node (ref "U25") (pin "12") (pinfunction "GND2_12") (pintype "bidirectional"))
      (node (ref "U25") (pin "8") (pinfunction "GND0_8") (pintype "bidirectional"))
      (node (ref "U26") (pin "10") (pinfunction "GND1_10") (pintype "bidirectional"))
      (node (ref "U26") (pin "12") (pinfunction "GND2_12") (pintype "bidirectional"))
      (node (ref "U26") (pin "8") (pinfunction "GND0_8") (pintype "bidirectional"))
      (node (ref "U27") (pin "10") (pinfunction "GND1_10") (pintype "bidirectional"))
      (node (ref "U27") (pin "12") (pinfunction "GND2_12") (pintype "bidirectional"))
      (node (ref "U27") (pin "8") (pinfunction "GND0_8") (pintype "bidirectional"))
      (node (ref "U28") (pin "1") (pinfunction "GND_1_1") (pintype "power_in"))
      (node (ref "U28") (pin "10") (pinfunction "GND_2_10") (pintype "power_in"))
      (node (ref "U28") (pin "11") (pinfunction "GND_3_11") (pintype "power_in"))
      (node (ref "U28") (pin "32") (pinfunction "GND_4_32") (pintype "power_in"))
      (node (ref "U28") (pin "43") (pinfunction "1-32/DEV_OE_43") (pintype "bidirectional"))
      (node (ref "U28") (pin "44") (pinfunction "1-33/~{DEV_CLR}_44") (pintype "bidirectional"))
      (node (ref "U28") (pin "46") (pinfunction "GND_5_46") (pintype "power_in"))
      (node (ref "U28") (pin "60") (pinfunction "GND_6_60") (pintype "power_in"))
      (node (ref "U28") (pin "65") (pinfunction "GND_7_65") (pintype "power_in"))
      (node (ref "U28") (pin "79") (pinfunction "GND_8_79") (pintype "power_in"))
      (node (ref "U28") (pin "93") (pinfunction "GND_9_93") (pintype "power_in"))
      (node (ref "U29") (pin "2") (pinfunction "GND_2") (pintype "passive"))
      (node (ref "U7") (pin "3") (pinfunction "EMI_3") (pintype "passive"))
      (node (ref "U8") (pin "3") (pinfunction "EMI_3") (pintype "passive"))
    )
    (net (code "14") (name "ALM_LOW_BAT") (class "Default")
      (node (ref "U28") (pin "69") (pinfunction "2-14_69") (pintype "bidirectional"))
      (node (ref "U5") (pin "2") (pinfunction "C_2") (pintype "passive"))
    )
    (net (code "15") (name "AMP_0") (class "Default")
      (node (ref "U18") (pin "10") (pinfunction "A_10") (pintype "input"))
      (node (ref "U23") (pin "5") (pinfunction "AMP_0_5") (pintype "bidirectional"))
      (node (ref "U24") (pin "5") (pinfunction "AMP_0_5") (pintype "bidirectional"))
      (node (ref "U25") (pin "5") (pinfunction "AMP_0_5") (pintype "bidirectional"))
      (node (ref "U26") (pin "5") (pinfunction "AMP_0_5") (pintype "bidirectional"))
      (node (ref "U27") (pin "5") (pinfunction "AMP_0_5") (pintype "bidirectional"))
      (node (ref "U28") (pin "19") (pinfunction "1-14_19") (pintype "bidirectional"))
    )
    (net (code "16") (name "AMP_1") (class "Default")
      (node (ref "U18") (pin "9") (pinfunction "B_9") (pintype "input"))
      (node (ref "U23") (pin "6") (pinfunction "AMP_1_6") (pintype "bidirectional"))
      (node (ref "U24") (pin "6") (pinfunction "AMP_1_6") (pintype "bidirectional"))
      (node (ref "U25") (pin "6") (pinfunction "AMP_1_6") (pintype "bidirectional"))
      (node (ref "U26") (pin "6") (pinfunction "AMP_1_6") (pintype "bidirectional"))
      (node (ref "U27") (pin "6") (pinfunction "AMP_1_6") (pintype "bidirectional"))
      (node (ref "U28") (pin "20") (pinfunction "1-15_20") (pintype "bidirectional"))
    )
    (net (code "17") (name "BATT+") (class "Default")
      (node (ref "L1") (pin "4") (pinfunction "1_4") (pintype "passive"))
      (node (ref "L7") (pin "4") (pinfunction "1_4") (pintype "passive"))
      (node (ref "SW1") (pin "1") (pinfunction "NO_1") (pintype "passive"))
    )
    (net (code "18") (name "BATT-") (class "Default")
      (node (ref "CN6") (pin "3") (pinfunction "3_3") (pintype "bidirectional"))
      (node (ref "CN6") (pin "4") (pinfunction "4_4") (pintype "bidirectional"))
      (node (ref "L1") (pin "3") (pinfunction "3_3") (pintype "passive"))
      (node (ref "L7") (pin "3") (pinfunction "3_3") (pintype "passive"))
    )
    (net (code "19") (name "CH_0") (class "Default")
      (node (ref "U21") (pin "11") (pinfunction "A_11") (pintype "input"))
      (node (ref "U22") (pin "11") (pinfunction "A_11") (pintype "input"))
      (node (ref "U28") (pin "16") (pinfunction "1-11_16") (pintype "bidirectional"))
    )
    (net (code "20") (name "CH_1") (class "Default")
      (node (ref "U21") (pin "10") (pinfunction "B_10") (pintype "input"))
      (node (ref "U22") (pin "10") (pinfunction "B_10") (pintype "input"))
      (node (ref "U28") (pin "15") (pinfunction "1-10_15") (pintype "bidirectional"))
    )
    (net (code "21") (name "CH_2") (class "Default")
      (node (ref "U21") (pin "9") (pinfunction "C_9") (pintype "input"))
      (node (ref "U22") (pin "9") (pinfunction "C_9") (pintype "input"))
      (node (ref "U28") (pin "14") (pinfunction "1-9/CLK1_14") (pintype "bidirectional"))
    )
    (net (code "22") (name "COMP_80") (class "Default")
      (node (ref "R58") (pin "2") (pinfunction "2_2") (pintype "passive"))
      (node (ref "U28") (pin "26") (pinfunction "1-17_26") (pintype "bidirectional"))
    )
    (net (code "23") (name "DGND") (class "Default")
      (node (ref "C10") (pin "2") (pinfunction "2_2") (pintype "passive"))
      (node (ref "C11") (pin "2") (pinfunction "2_2") (pintype "passive"))
      (node (ref "C12") (pin "2") (pinfunction "2_2") (pintype "passive"))
      (node (ref "C2") (pin "1") (pinfunction "1_1") (pintype "passive"))
      (node (ref "C3") (pin "1") (pinfunction "1_1") (pintype "passive"))
      (node (ref "C4") (pin "1") (pinfunction "1_1") (pintype "passive"))
      (node (ref "C5") (pin "1") (pinfunction "1_1") (pintype "passive"))
      (node (ref "C6") (pin "2") (pinfunction "2_2") (pintype "passive"))
      (node (ref "C61") (pin "1") (pinfunction "1_1") (pintype "passive"))
      (node (ref "C62") (pin "1") (pinfunction "1_1") (pintype "passive"))
      (node (ref "C63") (pin "1") (pinfunction "1_1") (pintype "passive"))
      (node (ref "C64") (pin "2") (pinfunction "2_2") (pintype "passive"))
      (node (ref "C65") (pin "1") (pinfunction "1_1") (pintype "passive"))
      (node (ref "C66") (pin "2") (pinfunction "2_2") (pintype "passive"))
      (node (ref "C67") (pin "NEG") (pinfunction "NEG_NEG") (pintype "passive"))
      (node (ref "C68") (pin "2") (pinfunction "2_2") (pintype "passive"))
      (node (ref "C69") (pin "2") (pinfunction "2_2") (pintype "passive"))
      (node (ref "C7") (pin "NEG") (pinfunction "NEG_NEG") (pintype "passive"))
      (node (ref "C70") (pin "2") (pinfunction "2_2") (pintype "passive"))
      (node (ref "C71") (pin "2") (pinfunction "2_2") (pintype "passive"))
      (node (ref "C8") (pin "2") (pinfunction "2_2") (pintype "passive"))
      (node (ref "C9") (pin "2") (pinfunction "2_2") (pintype "passive"))
      (node (ref "L1") (pin "2") (pinfunction "4_2") (pintype "passive"))
      (node (ref "L8") (pin "1") (pinfunction "2_1") (pintype "passive"))
      (node (ref "M1") (pin "CASE1") (pinfunction "P$1_CASE1") (pintype "bidirectional"))
      (node (ref "M2") (pin "CASE1") (pinfunction "P$1_CASE1") (pintype "bidirectional"))
      (node (ref "R105") (pin "1") (pinfunction "1_1") (pintype "passive"))
      (node (ref "R107") (pin "1") (pinfunction "1_1") (pintype "passive"))
      (node (ref "R108") (pin "1") (pinfunction "1_1") (pintype "passive"))
      (node (ref "R24") (pin "1") (pinfunction "1_1") (pintype "passive"))
      (node (ref "R29") (pin "1") (pinfunction "1_1") (pintype "passive"))
      (node (ref "TP19") (pin "1") (pinfunction "MP_1") (pintype "passive"))
      (node (ref "TR1") (pin "E") (pinfunction "E_E") (pintype "passive"))
      (node (ref "U1") (pin "3") (pinfunction "EMI_3") (pintype "passive"))
      (node (ref "U10") (pin "2") (pinfunction "V-_2") (pintype "power_in"))
      (node (ref "U11") (pin "10") (pinfunction "B_10") (pintype "input"))
      (node (ref "U11") (pin "11") (pinfunction "CLR_11") (pintype "input"))
      (node (ref "U11") (pin "14") (pinfunction "C_14") (pintype "input"))
      (node (ref "U11") (pin "8") (pinfunction "GND_8") (pintype "power_in"))
      (node (ref "U12") (pin "3") (pinfunction "GND_3") (pintype "power_in"))
      (node (ref "U2") (pin "4") (pinfunction "GND_4") (pintype "power_in"))
      (node (ref "U30") (pin "3") (pinfunction "EMI_3") (pintype "passive"))
      (node (ref "U32") (pin "3") (pinfunction "EMI_3") (pintype "passive"))
      (node (ref "U33") (pin "1") (pinfunction "~{G1}_1") (pintype "input"))
      (node (ref "U33") (pin "10") (pinfunction "GND_10") (pintype "power_in"))
      (node (ref "U33") (pin "19") (pinfunction "~{G2}_19") (pintype "input"))
      (node (ref "U34") (pin "2") (pinfunction "GND_2") (pintype "passive"))
      (node (ref "U35") (pin "2") (pinfunction "C_2") (pintype "passive"))
      (node (ref "U36") (pin "14") (pinfunction "C_14") (pintype "input"))
      (node (ref "U36") (pin "6") (pinfunction "C_6") (pintype "input"))
      (node (ref "U36") (pin "8") (pinfunction "GND_8") (pintype "power_in"))
      (node (ref "U37") (pin "1") (pinfunction "A_1") (pintype "input"))
      (node (ref "U37") (pin "10") (pinfunction "B_10") (pintype "input"))
      (node (ref "U37") (pin "11") (pinfunction "CLR_11") (pintype "input"))
      (node (ref "U37") (pin "14") (pinfunction "C_14") (pintype "input"))
      (node (ref "U37") (pin "8") (pinfunction "GND_8") (pintype "power_in"))
      (node (ref "U38") (pin "7") (pinfunction "GND_7") (pintype "power_in"))
      (node (ref "U4") (pin "10") (pinfunction "GND_10") (pintype "power_in"))
      (node (ref "U5") (pin "3") (pinfunction "EMI_3") (pintype "passive"))
      (node (ref "U6") (pin "2") (pinfunction "GND_2") (pintype "passive"))
      (node (ref "U9") (pin "7") (pinfunction "GND_7") (pintype "power_in"))
    )
    (net (code "24") (name "DIN00") (class "Default")
      (node (ref "R2") (pin "2") (pinfunction "2_2") (pintype "passive"))
      (node (ref "U1") (pin "4") (pinfunction "COL_4") (pintype "passive"))
      (node (ref "U2") (pin "1") (pinfunction "I_1") (pintype "input"))
    )
    (net (code "25") (name "DIN07") (class "Default")
      (node (ref "R9") (pin "2") (pinfunction "2_2") (pintype "passive"))
      (node (ref "U5") (pin "4") (pinfunction "COL_4") (pintype "passive"))
    )
    (net (code "26") (name "FLAME_SYNC") (class "Default")
      (node (ref "U1") (pin "2") (pinfunction "C_2") (pintype "passive"))
      (node (ref "U28") (pin "75") (pinfunction "2-20_75") (pintype "bidirectional"))
    )
    (net (code "27") (name "Net-(C18-Pad2)") (class "Default")
      (node (ref "C18") (pin "2") (pinfunction "2_2") (pintype "passive"))
      (node (ref "R49") (pin "2") (pinfunction "2_2") (pintype "passive"))
      (node (ref "R50") (pin "1") (pinfunction "1_1") (pintype "passive"))
    )
    (net (code "28") (name "Net-(CN1-GND)") (class "Default")
      (node (ref "CN1") (pin "1") (pinfunction "GND_1") (pintype "bidirectional"))
      (node (ref "R47") (pin "2") (pinfunction "2_2") (pintype "passive"))
    )
    (net (code "29") (name "Net-(CN1-L)") (class "Default")
      (node (ref "CN1") (pin "2") (pinfunction "L_2") (pintype "bidirectional"))
      (node (ref "L2") (pin "1") (pinfunction "2_1") (pintype "passive"))
    )
    (net (code "30") (name "Net-(CN1-R)") (class "Default")
      (node (ref "CN1") (pin "3") (pinfunction "R_3") (pintype "bidirectional"))
      (node (ref "L2") (pin "2") (pinfunction "4_2") (pintype "passive"))
    )
    (net (code "31") (name "Net-(CN2-GND)") (class "Default")
      (node (ref "CN2") (pin "1") (pinfunction "GND_1") (pintype "bidirectional"))
      (node (ref "R56") (pin "2") (pinfunction "2_2") (pintype "passive"))
    )
    (net (code "32") (name "Net-(CN2-L)") (class "Default")
      (node (ref "CN2") (pin "2") (pinfunction "L_2") (pintype "bidirectional"))
      (node (ref "L3") (pin "1") (pinfunction "2_1") (pintype "passive"))
    )
    (net (code "33") (name "Net-(CN2-R)") (class "Default")
      (node (ref "CN2") (pin "3") (pinfunction "R_3") (pintype "bidirectional"))
      (node (ref "L3") (pin "2") (pinfunction "4_2") (pintype "passive"))
    )
    (net (code "34") (name "Net-(CN3-GND)") (class "Default")
      (node (ref "CN3") (pin "1") (pinfunction "GND_1") (pintype "bidirectional"))
      (node (ref "R60") (pin "2") (pinfunction "2_2") (pintype "passive"))
    )
    (net (code "35") (name "Net-(CN3-L)") (class "Default")
      (node (ref "CN3") (pin "2") (pinfunction "L_2") (pintype "bidirectional"))
      (node (ref "L4") (pin "1") (pinfunction "2_1") (pintype "passive"))
    )
    (net (code "36") (name "Net-(CN3-R)") (class "Default")
      (node (ref "CN3") (pin "3") (pinfunction "R_3") (pintype "bidirectional"))
      (node (ref "L4") (pin "2") (pinfunction "4_2") (pintype "passive"))
    )
    (net (code "37") (name "Net-(CN4-GND)") (class "Default")
      (node (ref "CN4") (pin "1") (pinfunction "GND_1") (pintype "bidirectional"))
      (node (ref "R63") (pin "2") (pinfunction "2_2") (pintype "passive"))
    )
    (net (code "38") (name "Net-(CN4-L)") (class "Default")
      (node (ref "CN4") (pin "2") (pinfunction "L_2") (pintype "bidirectional"))
      (node (ref "L5") (pin "1") (pinfunction "2_1") (pintype "passive"))
    )
    (net (code "39") (name "Net-(CN4-R)") (class "Default")
      (node (ref "CN4") (pin "3") (pinfunction "R_3") (pintype "bidirectional"))
      (node (ref "L5") (pin "2") (pinfunction "4_2") (pintype "passive"))
    )
    (net (code "40") (name "Net-(CN5-GND)") (class "Default")
      (node (ref "CN5") (pin "1") (pinfunction "GND_1") (pintype "bidirectional"))
      (node (ref "R64") (pin "2") (pinfunction "2_2") (pintype "passive"))
    )
    (net (code "41") (name "Net-(CN5-L)") (class "Default")
      (node (ref "CN5") (pin "2") (pinfunction "L_2") (pintype "bidirectional"))
      (node (ref "L6") (pin "1") (pinfunction "2_1") (pintype "passive"))
    )
    (net (code "42") (name "Net-(CN5-R)") (class "Default")
      (node (ref "CN5") (pin "3") (pinfunction "R_3") (pintype "bidirectional"))
      (node (ref "L6") (pin "2") (pinfunction "4_2") (pintype "passive"))
    )
    (net (code "43") (name "Net-(CN6-Pad1)") (class "Default")
      (node (ref "CN6") (pin "1") (pinfunction "1_1") (pintype "bidirectional"))
      (node (ref "CN6") (pin "2") (pinfunction "2_2") (pintype "bidirectional"))
      (node (ref "F2") (pin "1") (pinfunction "1_1") (pintype "passive"))
    )
    (net (code "44") (name "Net-(CN9-Pad1)") (class "Default")
      (node (ref "CN9") (pin "1") (pinfunction "1_1") (pintype "bidirectional"))
      (node (ref "F1") (pin "1") (pinfunction "1_1") (pintype "passive"))
    )
    (net (code "45") (name "Net-(CN9B-CASE)") (class "Default")
      (node (ref "CN9") (pin "5") (pinfunction "5_5") (pintype "bidirectional"))
      (node (ref "CN9") (pin "C1") (pinfunction "CASE1_C1") (pintype "bidirectional"))
      (node (ref "CN9") (pin "C2") (pinfunction "CASE2_C2") (pintype "bidirectional"))
      (node (ref "CN9") (pin "C3") (pinfunction "CASE3_C3") (pintype "bidirectional"))
      (node (ref "CN9") (pin "C4") (pinfunction "CASE4_C4") (pintype "bidirectional"))
      (node (ref "CN9") (pin "C5") (pinfunction "CASE5_C5") (pintype "bidirectional"))
      (node (ref "CN9") (pin "C6") (pinfunction "CASE_C6") (pintype "bidirectional"))
      (node (ref "L8") (pin "4") (pinfunction "1_4") (pintype "passive"))
    )
    (net (code "46") (name "Net-(D3-AC)") (class "Default")
      (node (ref "D3") (pin "3") (pinfunction "AC_3") (pintype "passive"))
      (node (ref "R51") (pin "2") (pinfunction "2_2") (pintype "passive"))
      (node (ref "R51") (pin "3") (pinfunction "3_3") (pintype "passive"))
      (node (ref "R52") (pin "1") (pinfunction "1_1") (pintype "passive"))
    )
    (net (code "47") (name "Net-(D4-K1)") (class "Default")
      (node (ref "D4") (pin "C") (pinfunction "K1_C") (pintype "passive"))
      (node (ref "R72") (pin "2") (pinfunction "2_2") (pintype "passive"))
    )
    (net (code "48") (name "Net-(D5-A1)") (class "Default")
      (node (ref "D5") (pin "A") (pinfunction "A1_A") (pintype "passive"))
      (node (ref "R98") (pin "1") (pinfunction "1_1") (pintype "passive"))
    )
    (net (code "49") (name "Net-(D5-K1)") (class "Default")
      (node (ref "D5") (pin "C") (pinfunction "K1_C") (pintype "passive"))
      (node (ref "D7") (pin "A") (pinfunction "A_A") (pintype "passive"))
      (node (ref "D8") (pin "A") (pinfunction "A_A") (pintype "passive"))
    )
    (net (code "50") (name "Net-(F1-Pad2)") (class "Default")
      (node (ref "F1") (pin "2") (pinfunction "2_2") (pintype "passive"))
      (node (ref "L8") (pin "3") (pinfunction "3_3") (pintype "passive"))
    )
    (net (code "51") (name "Net-(R28-Pad2)") (class "Default")
      (node (ref "R28") (pin "2") (pinfunction "2_2") (pintype "passive"))
      (node (ref "R29") (pin "2") (pinfunction "2_2") (pintype "passive"))
      (node (ref "TR1") (pin "B") (pinfunction "B_B") (pintype "passive"))
    )
    (net (code "52") (name "Net-(R39-Pad2)") (class "Default")
      (node (ref "R39") (pin "2") (pinfunction "2_2") (pintype "passive"))
      (node (ref "R40") (pin "3") (pinfunction "3_3") (pintype "passive"))
    )
    (net (code "53") (name "Net-(R40-Pad1)") (class "Default")
      (node (ref "R40") (pin "1") (pinfunction "1_1") (pintype "passive"))
      (node (ref "R41") (pin "1") (pinfunction "1_1") (pintype "passive"))
    )
    (net (code "54") (name "Net-(R48-Pad2)") (class "Default")
      (node (ref "R48") (pin "2") (pinfunction "2_2") (pintype "passive"))
      (node (ref "R49") (pin "1") (pinfunction "1_1") (pintype "passive"))
    )
    (net (code "55") (name "Net-(R50-Pad2)") (class "Default")
      (node (ref "R50") (pin "2") (pinfunction "2_2") (pintype "passive"))
      (node (ref "R51") (pin "1") (pinfunction "1_1") (pintype "passive"))
    )
    (net (code "56") (name "Net-(R66-Pad1)") (class "Default")
      (node (ref "R66") (pin "1") (pinfunction "1_1") (pintype "passive"))
      (node (ref "R67") (pin "2") (pinfunction "2_2") (pintype "passive"))
    )
    (net (code "57") (name "Net-(SW1A-C)") (class "Default")
      (node (ref "F2") (pin "2") (pinfunction "2_2") (pintype "passive"))
      (node (ref "SW1") (pin "2") (pinfunction "C_2") (pintype "passive"))
    )
    (net (code "58") (name "Net-(SW2A-C)") (class "Default")
      (node (ref "R79") (pin "2") (pinfunction "2_2") (pintype "passive"))
      (node (ref "SW2") (pin "2") (pinfunction "C_2") (pintype "passive"))
    )
    (net (code "59") (name "Net-(SW3A-C)") (class "Default")
      (node (ref "R81") (pin "2") (pinfunction "2_2") (pintype "passive"))
      (node (ref "SW3") (pin "2") (pinfunction "C_2") (pintype "passive"))
    )
    (net (code "60") (name "Net-(SW4A-C)") (class "Default")
      (node (ref "R83") (pin "2") (pinfunction "2_2") (pintype "passive"))
      (node (ref "SW4") (pin "2") (pinfunction "C_2") (pintype "passive"))
    )
    (net (code "61") (name "Net-(SW5A-C)") (class "Default")
      (node (ref "R85") (pin "2") (pinfunction "2_2") (pintype "passive"))
      (node (ref "SW5") (pin "2") (pinfunction "C_2") (pintype "passive"))
    )
    (net (code "62") (name "Net-(SW6A-C)") (class "Default")
      (node (ref "R105") (pin "2") (pinfunction "2_2") (pintype "passive"))
      (node (ref "SW6") (pin "2") (pinfunction "C_2") (pintype "passive"))
    )
    (net (code "63") (name "Net-(SW6A-NC)") (class "Default")
      (node (ref "R101") (pin "1") (pinfunction "1_1") (pintype "passive"))
      (node (ref "R102") (pin "1") (pinfunction "1_1") (pintype "passive"))
      (node (ref "SW6") (pin "3") (pinfunction "NC_3") (pintype "passive"))
    )
    (net (code "64") (name "Net-(SW6A-NO)") (class "Default")
      (node (ref "R104") (pin "1") (pinfunction "1_1") (pintype "passive"))
      (node (ref "R106") (pin "1") (pinfunction "1_1") (pintype "passive"))
      (node (ref "SW6") (pin "1") (pinfunction "NO_1") (pintype "passive"))
    )
    (net (code "65") (name "Net-(TP2-MP)") (class "Default")
      (node (ref "R21") (pin "2") (pinfunction "2_2") (pintype "passive"))
      (node (ref "R23") (pin "1") (pinfunction "1_1") (pintype "passive"))
      (node (ref "TP2") (pin "1") (pinfunction "MP_1") (pintype "passive"))
      (node (ref "U10") (pin "4") (pinfunction "OUT_4") (pintype "output"))
    )
    (net (code "66") (name "Net-(TP4-MP)") (class "Default")
      (node (ref "R36") (pin "2") (pinfunction "2_2") (pintype "passive"))
      (node (ref "TP4") (pin "1") (pinfunction "MP_1") (pintype "passive"))
      (node (ref "U13") (pin "1") (pinfunction "OUT_1") (pintype "output"))
      (node (ref "U16") (pin "6") (pinfunction "COM_6") (pintype "bidirectional"))
    )
    (net (code "67") (name "Net-(TP5-MP)") (class "Default")
      (node (ref "C13") (pin "1") (pinfunction "1_1") (pintype "passive"))
      (node (ref "R38") (pin "1") (pinfunction "1_1") (pintype "passive"))
      (node (ref "R53") (pin "1") (pinfunction "1_1") (pintype "passive"))
      (node (ref "TP5") (pin "1") (pinfunction "MP_1") (pintype "passive"))
    )
    (net (code "68") (name "Net-(TP6-MP)") (class "Default")
      (node (ref "C19") (pin "1") (pinfunction "1_1") (pintype "passive"))
      (node (ref "R54") (pin "2") (pinfunction "2_2") (pintype "passive"))
      (node (ref "TP6") (pin "1") (pinfunction "MP_1") (pintype "passive"))
      (node (ref "U13") (pin "7") (pinfunction "OUT_7") (pintype "output"))
      (node (ref "U16") (pin "10") (pinfunction "COM_10") (pintype "bidirectional"))
    )
    (net (code "69") (name "Net-(TP7-MP)") (class "Default")
      (node (ref "C14") (pin "1") (pinfunction "1_1") (pintype "passive"))
      (node (ref "R43") (pin "1") (pinfunction "1_1") (pintype "passive"))
      (node (ref "R52") (pin "2") (pinfunction "2_2") (pintype "passive"))
      (node (ref "TP7") (pin "1") (pinfunction "MP_1") (pintype "passive"))
      (node (ref "U15") (pin "7") (pinfunction "OUT_7") (pintype "output"))
      (node (ref "U17") (pin "1") (pinfunction "-IN_1") (pintype "input"))
    )
    (net (code "70") (name "Net-(TP12-MP)") (class "Default")
      (node (ref "TP12") (pin "P$1") (pinfunction "MP_P$1") (pintype "passive"))
      (node (ref "U28") (pin "12") (pinfunction "1-8/CLK0_12") (pintype "bidirectional"))
    )
    (net (code "71") (name "Net-(TP13-MP)") (class "Default")
      (node (ref "TP13") (pin "P$1") (pinfunction "MP_P$1") (pintype "passive"))
      (node (ref "U28") (pin "61") (pinfunction "2-8_61") (pintype "bidirectional"))
    )
    (net (code "72") (name "Net-(TP14-MP)") (class "Default")
      (node (ref "TP14") (pin "P$1") (pinfunction "MP_P$1") (pintype "passive"))
      (node (ref "U28") (pin "58") (pinfunction "2-7_58") (pintype "bidirectional"))
    )
    (net (code "73") (name "Net-(TP15-MP)") (class "Default")
      (node (ref "TP15") (pin "P$1") (pinfunction "MP_P$1") (pintype "passive"))
      (node (ref "U28") (pin "57") (pinfunction "2-6_57") (pintype "bidirectional"))
    )
    (net (code "74") (name "Net-(TP16-MP)") (class "Default")
      (node (ref "TP16") (pin "P$1") (pinfunction "MP_P$1") (pintype "passive"))
      (node (ref "U28") (pin "56") (pinfunction "2-5_56") (pintype "bidirectional"))
    )
    (net (code "75") (name "Net-(TP17-MP)") (class "Default")
      (node (ref "TP17") (pin "P$1") (pinfunction "MP_P$1") (pintype "passive"))
      (node (ref "U28") (pin "29") (pinfunction "1-20_29") (pintype "bidirectional"))
    )
    (net (code "76") (name "Net-(TP18-MP)") (class "Default")
      (node (ref "TP18") (pin "1") (pinfunction "MP_1") (pintype "passive"))
      (node (ref "U33") (pin "18") (pinfunction "~{Y1}_18") (pintype "output"))
    )
    (net (code "77") (name "Net-(U1-A)") (class "Default")
      (node (ref "R3") (pin "1") (pinfunction "1_1") (pintype "passive"))
      (node (ref "U1") (pin "1") (pinfunction "A_1") (pintype "passive"))
    )
    (net (code "78") (name "Net-(U2B-I)") (class "Default")
      (node (ref "C6") (pin "1") (pinfunction "1_1") (pintype "passive"))
      (node (ref "D2") (pin "A") (pinfunction "A_A") (pintype "passive"))
      (node (ref "R27") (pin "1") (pinfunction "1_1") (pintype "passive"))
      (node (ref "U2") (pin "3") (pinfunction "I_3") (pintype "input"))
    )
    (net (code "79") (name "Net-(U2B-O)") (class "Default")
      (node (ref "R28") (pin "1") (pinfunction "1_1") (pintype "passive"))
      (node (ref "U2") (pin "5") (pinfunction "O_5") (pintype "output"))
    )
    (net (code "80") (name "Net-(U2C-I)") (class "Default")
      (node (ref "U2") (pin "6") (pinfunction "I_6") (pintype "input"))
      (node (ref "U6") (pin "1") (pinfunction "VO_1") (pintype "passive"))
      (node (ref "U6") (pin "4") (pinfunction "RL_4") (pintype "passive"))
    )
    (net (code "81") (name "Net-(U3-A)") (class "Default")
      (node (ref "R5") (pin "1") (pinfunction "1_1") (pintype "passive"))
      (node (ref "U3") (pin "1") (pinfunction "A_1") (pintype "passive"))
    )
    (net (code "82") (name "Net-(U3-C)") (class "Default")
      (node (ref "C1") (pin "2") (pinfunction "2_2") (pintype "passive"))
      (node (ref "R1") (pin "1") (pinfunction "1_1") (pintype "passive"))
      (node (ref "R11") (pin "1") (pinfunction "1_1") (pintype "passive"))
      (node (ref "R12") (pin "1") (pinfunction "1_1") (pintype "passive"))
      (node (ref "R4") (pin "1") (pinfunction "1_1") (pintype "passive"))
      (node (ref "R6") (pin "1") (pinfunction "1_1") (pintype "passive"))
      (node (ref "R7") (pin "1") (pinfunction "1_1") (pintype "passive"))
      (node (ref "R8") (pin "1") (pinfunction "1_1") (pintype "passive"))
      (node (ref "U3") (pin "2") (pinfunction "C_2") (pintype "passive"))
    )
    (net (code "83") (name "Net-(U4A-~{Y2})") (class "Default")
      (node (ref "R1") (pin "2") (pinfunction "2_2") (pintype "passive"))
      (node (ref "U4") (pin "17") (pinfunction "~{Y2}_17") (pintype "output"))
    )
    (net (code "84") (name "Net-(U4A-~{Y3})") (class "Default")
      (node (ref "R4") (pin "2") (pinfunction "2_2") (pintype "passive"))
      (node (ref "U4") (pin "16") (pinfunction "~{Y3}_16") (pintype "output"))
    )
    (net (code "85") (name "Net-(U4A-~{Y4})") (class "Default")
      (node (ref "R6") (pin "2") (pinfunction "2_2") (pintype "passive"))
      (node (ref "U4") (pin "15") (pinfunction "~{Y4}_15") (pintype "output"))
    )
    (net (code "86") (name "Net-(U4A-~{Y5})") (class "Default")
      (node (ref "R7") (pin "2") (pinfunction "2_2") (pintype "passive"))
      (node (ref "U4") (pin "14") (pinfunction "~{Y5}_14") (pintype "output"))
    )
    (net (code "87") (name "Net-(U4A-~{Y6})") (class "Default")
      (node (ref "R8") (pin "2") (pinfunction "2_2") (pintype "passive"))
      (node (ref "U4") (pin "13") (pinfunction "~{Y6}_13") (pintype "output"))
    )
    (net (code "88") (name "Net-(U4A-~{Y7})") (class "Default")
      (node (ref "R11") (pin "2") (pinfunction "2_2") (pintype "passive"))
      (node (ref "U4") (pin "12") (pinfunction "~{Y7}_12") (pintype "output"))
    )
    (net (code "89") (name "Net-(U4A-~{Y8})") (class "Default")
      (node (ref "R12") (pin "2") (pinfunction "2_2") (pintype "passive"))
      (node (ref "U4") (pin "11") (pinfunction "~{Y8}_11") (pintype "output"))
    )
    (net (code "90") (name "Net-(U5-A)") (class "Default")
      (node (ref "R10") (pin "1") (pinfunction "1_1") (pintype "passive"))
      (node (ref "U5") (pin "1") (pinfunction "A_1") (pintype "passive"))
    )
    (net (code "91") (name "Net-(U7-A)") (class "Default")
      (node (ref "R13") (pin "2") (pinfunction "2_2") (pintype "passive"))
      (node (ref "U7") (pin "1") (pinfunction "A_1") (pintype "passive"))
    )
    (net (code "92") (name "Net-(U8-A)") (class "Default")
      (node (ref "R15") (pin "2") (pinfunction "2_2") (pintype "passive"))
      (node (ref "U8") (pin "1") (pinfunction "A_1") (pintype "passive"))
    )
    (net (code "93") (name "Net-(U9A-CLR)") (class "Default")
      (node (ref "R18") (pin "1") (pinfunction "1_1") (pintype "passive"))
      (node (ref "U9") (pin "1") (pinfunction "CLR_1") (pintype "input"))
    )
    (net (code "94") (name "Net-(U9A-PRE)") (class "Default")
      (node (ref "D1") (pin "A") (pinfunction "A_A") (pintype "passive"))
      (node (ref "R25") (pin "2") (pinfunction "2_2") (pintype "passive"))
      (node (ref "TR1") (pin "C") (pinfunction "C_C") (pintype "passive"))
      (node (ref "U9") (pin "10") (pinfunction "PRE_10") (pintype "input"))
      (node (ref "U9") (pin "4") (pinfunction "PRE_4") (pintype "input"))
    )
    (net (code "95") (name "Net-(U9B-CLR)") (class "Default")
      (node (ref "R19") (pin "1") (pinfunction "1_1") (pintype "passive"))
      (node (ref "U9") (pin "13") (pinfunction "CLR_13") (pintype "input"))
    )
    (net (code "96") (name "Net-(U10-+IN)") (class "Default")
      (node (ref "R21") (pin "1") (pinfunction "1_1") (pintype "passive"))
      (node (ref "R22") (pin "1") (pinfunction "1_1") (pintype "passive"))
      (node (ref "R24") (pin "2") (pinfunction "2_2") (pintype "passive"))
      (node (ref "U10") (pin "3") (pinfunction "+IN_3") (pintype "input"))
    )
    (net (code "97") (name "Net-(U10--IN)") (class "Default")
      (node (ref "C5") (pin "2") (pinfunction "2_2") (pintype "passive"))
      (node (ref "R26") (pin "1") (pinfunction "1_1") (pintype "passive"))
      (node (ref "U10") (pin "1") (pinfunction "-IN_1") (pintype "input"))
    )
    (net (code "98") (name "Net-(U11A-A)") (class "Default")
      (node (ref "R17") (pin "2") (pinfunction "2_2") (pintype "passive"))
      (node (ref "R23") (pin "2") (pinfunction "2_2") (pintype "passive"))
      (node (ref "U11") (pin "1") (pinfunction "A_1") (pintype "input"))
      (node (ref "U9") (pin "2") (pinfunction "D_2") (pintype "input"))
    )
    (net (code "99") (name "Net-(U11A-R{slash}C)") (class "Default")
      (node (ref "C4") (pin "2") (pinfunction "2_2") (pintype "passive"))
      (node (ref "R20") (pin "2") (pinfunction "2_2") (pintype "passive"))
      (node (ref "U11") (pin "15") (pinfunction "R/C_15") (pintype "input"))
    )
    (net (code "100") (name "Net-(U11A-{slash}Q)") (class "Default")
      (node (ref "U11") (pin "4") (pinfunction "/Q_4") (pintype "output"))
      (node (ref "U9") (pin "11") (pinfunction "CLK_11") (pintype "input"))
      (node (ref "U9") (pin "3") (pinfunction "CLK_3") (pintype "input"))
    )
    (net (code "101") (name "Net-(U12A-O)") (class "Default")
      (node (ref "D1") (pin "C") (pinfunction "C_C") (pintype "passive"))
      (node (ref "U12") (pin "4") (pinfunction "O_4") (pintype "output"))
    )
    (net (code "102") (name "Net-(U13A-+IN)") (class "Default")
      (node (ref "C16") (pin "1") (pinfunction "1_1") (pintype "passive"))
      (node (ref "R38") (pin "2") (pinfunction "2_2") (pintype "passive"))
      (node (ref "R45") (pin "2") (pinfunction "2_2") (pintype "passive"))
      (node (ref "U13") (pin "3") (pinfunction "+IN_3") (pintype "input"))
    )
    (net (code "103") (name "Net-(U13A--IN)") (class "Default")
      (node (ref "R35") (pin "2") (pinfunction "2_2") (pintype "passive"))
      (node (ref "R36") (pin "1") (pinfunction "1_1") (pintype "passive"))
      (node (ref "U13") (pin "2") (pinfunction "-IN_2") (pintype "input"))
    )
    (net (code "104") (name "Net-(U13B--IN)") (class "Default")
      (node (ref "C19") (pin "2") (pinfunction "2_2") (pintype "passive"))
      (node (ref "R53") (pin "2") (pinfunction "2_2") (pintype "passive"))
      (node (ref "R54") (pin "1") (pinfunction "1_1") (pintype "passive"))
      (node (ref "U13") (pin "6") (pinfunction "-IN_6") (pintype "input"))
    )
    (net (code "105") (name "Net-(U14A-+IN)") (class "Default")
      (node (ref "R43") (pin "2") (pinfunction "2_2") (pintype "passive"))
      (node (ref "R46") (pin "2") (pinfunction "2_2") (pintype "passive"))
      (node (ref "U14") (pin "3") (pinfunction "+IN_3") (pintype "input"))
    )
    (net (code "106") (name "Net-(U14A--IN)") (class "Default")
      (node (ref "U14") (pin "2") (pinfunction "-IN_2") (pintype "input"))
      (node (ref "U18") (pin "13") (pinfunction "COM_13") (pintype "bidirectional"))
    )
    (net (code "107") (name "Net-(U14A-OUT)") (class "Default")
      (node (ref "C13") (pin "2") (pinfunction "2_2") (pintype "passive"))
      (node (ref "R34") (pin "2") (pinfunction "2_2") (pintype "passive"))
      (node (ref "U14") (pin "1") (pinfunction "OUT_1") (pintype "output"))
    )
    (net (code "108") (name "Net-(U14B-+IN)") (class "Default")
      (node (ref "C27") (pin "1") (pinfunction "1_1") (pintype "passive"))
      (node (ref "R68") (pin "1") (pinfunction "1_1") (pintype "passive"))
      (node (ref "R71") (pin "2") (pinfunction "2_2") (pintype "passive"))
      (node (ref "U14") (pin "5") (pinfunction "+IN_5") (pintype "input"))
    )
    (net (code "109") (name "Net-(U14B--IN)") (class "Default")
      (node (ref "R69") (pin "1") (pinfunction "1_1") (pintype "passive"))
      (node (ref "U14") (pin "6") (pinfunction "-IN_6") (pintype "input"))
      (node (ref "U14") (pin "7") (pinfunction "OUT_7") (pintype "output"))
    )
    (net (code "110") (name "Net-(U15A-+IN)") (class "Default")
      (node (ref "C21") (pin "1") (pinfunction "1_1") (pintype "passive"))
      (node (ref "R48") (pin "1") (pinfunction "1_1") (pintype "passive"))
      (node (ref "U15") (pin "3") (pinfunction "+IN_3") (pintype "input"))
    )
    (net (code "111") (name "Net-(U15A--IN)") (class "Default")
      (node (ref "R40") (pin "2") (pinfunction "2_2") (pintype "passive"))
      (node (ref "U15") (pin "2") (pinfunction "-IN_2") (pintype "input"))
    )
    (net (code "112") (name "Net-(U15A-OUT)") (class "Default")
      (node (ref "C18") (pin "1") (pinfunction "1_1") (pintype "passive"))
      (node (ref "R41") (pin "2") (pinfunction "2_2") (pintype "passive"))
      (node (ref "R42") (pin "1") (pinfunction "1_1") (pintype "passive"))
      (node (ref "U15") (pin "1") (pinfunction "OUT_1") (pintype "output"))
    )
    (net (code "113") (name "Net-(U15B--IN)") (class "Default")
      (node (ref "C14") (pin "2") (pinfunction "2_2") (pintype "passive"))
      (node (ref "R42") (pin "2") (pinfunction "2_2") (pintype "passive"))
      (node (ref "U15") (pin "6") (pinfunction "-IN_6") (pintype "input"))
    )
    (net (code "114") (name "Net-(U16A-NC)") (class "Default")
      (node (ref "R55") (pin "1") (pinfunction "1_1") (pintype "passive"))
      (node (ref "U16") (pin "9") (pinfunction "NC_9") (pintype "bidirectional"))
    )
    (net (code "115") (name "Net-(U16A-NO)") (class "Default")
      (node (ref "R57") (pin "1") (pinfunction "1_1") (pintype "passive"))
      (node (ref "U16") (pin "2") (pinfunction "NO_2") (pintype "bidirectional"))
    )
    (net (code "116") (name "Net-(U16B-NC)") (class "Default")
      (node (ref "R37") (pin "1") (pinfunction "1_1") (pintype "passive"))
      (node (ref "U16") (pin "7") (pinfunction "NC_7") (pintype "bidirectional"))
    )
    (net (code "117") (name "Net-(U16B-NO)") (class "Default")
      (node (ref "R44") (pin "1") (pinfunction "1_1") (pintype "passive"))
      (node (ref "U16") (pin "4") (pinfunction "NO_4") (pintype "bidirectional"))
    )
    (net (code "118") (name "Net-(U17-+IN)") (class "Default")
      (node (ref "R58") (pin "1") (pinfunction "1_1") (pintype "passive"))
      (node (ref "R59") (pin "1") (pinfunction "1_1") (pintype "passive"))
      (node (ref "R61") (pin "2") (pinfunction "2_2") (pintype "passive"))
      (node (ref "U17") (pin "3") (pinfunction "+IN_3") (pintype "input"))
    )
    (net (code "119") (name "Net-(U17-OUT)") (class "Default")
      (node (ref "R59") (pin "2") (pinfunction "2_2") (pintype "passive"))
      (node (ref "R62") (pin "1") (pinfunction "1_1") (pintype "passive"))
      (node (ref "U17") (pin "4") (pinfunction "OUT_4") (pintype "output"))
    )
    (net (code "120") (name "Net-(U18C-0)") (class "Default")
      (node (ref "R33") (pin "2") (pinfunction "2_2") (pintype "passive"))
      (node (ref "R34") (pin "1") (pinfunction "1_1") (pintype "passive"))
      (node (ref "U18") (pin "12") (pinfunction "0_12") (pintype "bidirectional"))
    )
    (net (code "121") (name "Net-(U18C-1)") (class "Default")
      (node (ref "R32") (pin "2") (pinfunction "2_2") (pintype "passive"))
      (node (ref "R33") (pin "1") (pinfunction "1_1") (pintype "passive"))
      (node (ref "U18") (pin "14") (pinfunction "1_14") (pintype "bidirectional"))
    )
    (net (code "122") (name "Net-(U18C-2)") (class "Default")
      (node (ref "R31") (pin "2") (pinfunction "2_2") (pintype "passive"))
      (node (ref "R32") (pin "1") (pinfunction "1_1") (pintype "passive"))
      (node (ref "U18") (pin "15") (pinfunction "2_15") (pintype "bidirectional"))
    )
    (net (code "123") (name "Net-(U18C-3)") (class "Default")
      (node (ref "R30") (pin "2") (pinfunction "2_2") (pintype "passive"))
      (node (ref "R31") (pin "1") (pinfunction "1_1") (pintype "passive"))
      (node (ref "U18") (pin "11") (pinfunction "3_11") (pintype "bidirectional"))
    )
    (net (code "124") (name "Net-(U19-CT)") (class "Default")
      (node (ref "C26") (pin "1") (pinfunction "1_1") (pintype "passive"))
      (node (ref "U19") (pin "4") (pinfunction "CT_4") (pintype "passive"))
    )
    (net (code "125") (name "Net-(U19-SENSE)") (class "Default")
      (node (ref "C25") (pin "1") (pinfunction "1_1") (pintype "passive"))
      (node (ref "R67") (pin "1") (pinfunction "1_1") (pintype "passive"))
      (node (ref "R70") (pin "2") (pinfunction "2_2") (pintype "passive"))
      (node (ref "U19") (pin "5") (pinfunction "SENSE_5") (pintype "bidirectional"))
    )
    (net (code "126") (name "Net-(U20-NR)") (class "Default")
      (node (ref "C38") (pin "1") (pinfunction "1_1") (pintype "passive"))
      (node (ref "U20") (pin "4") (pinfunction "NR_4") (pintype "passive"))
    )
    (net (code "127") (name "Net-(U21B-COM)") (class "Default")
      (node (ref "R55") (pin "2") (pinfunction "2_2") (pintype "passive"))
      (node (ref "R57") (pin "2") (pinfunction "2_2") (pintype "passive"))
      (node (ref "U21") (pin "3") (pinfunction "COM_3") (pintype "bidirectional"))
    )
    (net (code "128") (name "Net-(U22B-COM)") (class "Default")
      (node (ref "R37") (pin "2") (pinfunction "2_2") (pintype "passive"))
      (node (ref "R44") (pin "2") (pinfunction "2_2") (pintype "passive"))
      (node (ref "U22") (pin "3") (pinfunction "COM_3") (pintype "bidirectional"))
    )
    (net (code "129") (name "Net-(U28A-TCK)") (class "Default")
      (node (ref "CN7") (pin "1") (pinfunction "1_1") (pintype "bidirectional"))
      (node (ref "R77") (pin "2") (pinfunction "2_2") (pintype "passive"))
      (node (ref "U28") (pin "24") (pinfunction "TCK_24") (pintype "bidirectional"))
    )
    (net (code "130") (name "Net-(U28A-TDI)") (class "Default")
      (node (ref "CN7") (pin "9") (pinfunction "9_9") (pintype "bidirectional"))
      (node (ref "R75") (pin "1") (pinfunction "1_1") (pintype "passive"))
      (node (ref "U28") (pin "23") (pinfunction "TDI_23") (pintype "bidirectional"))
    )
    (net (code "131") (name "Net-(U28A-TDO)") (class "Default")
      (node (ref "CN7") (pin "3") (pinfunction "3_3") (pintype "bidirectional"))
      (node (ref "R74") (pin "1") (pinfunction "1_1") (pintype "passive"))
      (node (ref "U28") (pin "25") (pinfunction "TDO_25") (pintype "bidirectional"))
    )
    (net (code "132") (name "Net-(U28A-TMS)") (class "Default")
      (node (ref "CN7") (pin "5") (pinfunction "5_5") (pintype "bidirectional"))
      (node (ref "R76") (pin "1") (pinfunction "1_1") (pintype "passive"))
      (node (ref "U28") (pin "22") (pinfunction "TMS_22") (pintype "bidirectional"))
    )
    (net (code "133") (name "Net-(U29-NR)") (class "Default")
      (node (ref "C58") (pin "1") (pinfunction "1_1") (pintype "passive"))
      (node (ref "U29") (pin "4") (pinfunction "NR_4") (pintype "passive"))
    )
    (net (code "134") (name "Net-(U30-A)") (class "Default")
      (node (ref "CN8") (pin "1") (pinfunction "1_1") (pintype "bidirectional"))
      (node (ref "U30") (pin "1") (pinfunction "A_1") (pintype "passive"))
    )
    (net (code "135") (name "Net-(U30-C)") (class "Default")
      (node (ref "CN8") (pin "2") (pinfunction "2_2") (pintype "bidirectional"))
      (node (ref "U30") (pin "2") (pinfunction "C_2") (pintype "passive"))
    )
    (net (code "136") (name "Net-(U31-A)") (class "Default")
      (node (ref "R89") (pin "1") (pinfunction "1_1") (pintype "passive"))
      (node (ref "U31") (pin "1") (pinfunction "A_1") (pintype "passive"))
    )
    (net (code "137") (name "Net-(U31-C)") (class "Default")
      (node (ref "C60") (pin "2") (pinfunction "2_2") (pintype "passive"))
      (node (ref "R86") (pin "1") (pinfunction "1_1") (pintype "passive"))
      (node (ref "R88") (pin "1") (pinfunction "1_1") (pintype "passive"))
      (node (ref "R90") (pin "1") (pinfunction "1_1") (pintype "passive"))
      (node (ref "R91") (pin "1") (pinfunction "1_1") (pintype "passive"))
      (node (ref "R93") (pin "1") (pinfunction "1_1") (pintype "passive"))
      (node (ref "R94") (pin "1") (pinfunction "1_1") (pintype "passive"))
      (node (ref "R95") (pin "1") (pinfunction "1_1") (pintype "passive"))
      (node (ref "U31") (pin "2") (pinfunction "C_2") (pintype "passive"))
    )
    (net (code "138") (name "Net-(U32-A)") (class "Default")
      (node (ref "CN8") (pin "3") (pinfunction "3_3") (pintype "bidirectional"))
      (node (ref "U32") (pin "1") (pinfunction "A_1") (pintype "passive"))
    )
    (net (code "139") (name "Net-(U32-C)") (class "Default")
      (node (ref "CN8") (pin "4") (pinfunction "4_4") (pintype "bidirectional"))
      (node (ref "U32") (pin "2") (pinfunction "C_2") (pintype "passive"))
    )
    (net (code "140") (name "Net-(U33A-~{Y2})") (class "Default")
      (node (ref "R86") (pin "2") (pinfunction "2_2") (pintype "passive"))
      (node (ref "U33") (pin "17") (pinfunction "~{Y2}_17") (pintype "output"))
    )
    (net (code "141") (name "Net-(U33A-~{Y3})") (class "Default")
      (node (ref "R88") (pin "2") (pinfunction "2_2") (pintype "passive"))
      (node (ref "U33") (pin "16") (pinfunction "~{Y3}_16") (pintype "output"))
    )
    (net (code "142") (name "Net-(U33A-~{Y4})") (class "Default")
      (node (ref "R90") (pin "2") (pinfunction "2_2") (pintype "passive"))
      (node (ref "U33") (pin "15") (pinfunction "~{Y4}_15") (pintype "output"))
    )
    (net (code "143") (name "Net-(U33A-~{Y5})") (class "Default")
      (node (ref "R91") (pin "2") (pinfunction "2_2") (pintype "passive"))
      (node (ref "U33") (pin "14") (pinfunction "~{Y5}_14") (pintype "output"))
    )
    (net (code "144") (name "Net-(U33A-~{Y6})") (class "Default")
      (node (ref "R93") (pin "2") (pinfunction "2_2") (pintype "passive"))
      (node (ref "U33") (pin "13") (pinfunction "~{Y6}_13") (pintype "output"))
    )
    (net (code "145") (name "Net-(U33A-~{Y7})") (class "Default")
      (node (ref "R94") (pin "2") (pinfunction "2_2") (pintype "passive"))
      (node (ref "U33") (pin "12") (pinfunction "~{Y7}_12") (pintype "output"))
    )
    (net (code "146") (name "Net-(U33A-~{Y8})") (class "Default")
      (node (ref "R95") (pin "2") (pinfunction "2_2") (pintype "passive"))
      (node (ref "U33") (pin "11") (pinfunction "~{Y8}_11") (pintype "output"))
    )
    (net (code "147") (name "Net-(U34-RL)") (class "Default")
      (node (ref "D8") (pin "C") (pinfunction "C_C") (pintype "passive"))
      (node (ref "U34") (pin "1") (pinfunction "VO_1") (pintype "passive"))
      (node (ref "U34") (pin "4") (pinfunction "RL_4") (pintype "passive"))
      (node (ref "U37") (pin "2") (pinfunction "B_2") (pintype "input"))
      (node (ref "U38") (pin "1") (pinfunction "I_1") (pintype "input"))
    )
    (net (code "148") (name "Net-(U35-A)") (class "Default")
      (node (ref "R96") (pin "1") (pinfunction "1_1") (pintype "passive"))
      (node (ref "U35") (pin "1") (pinfunction "A_1") (pintype "passive"))
    )
    (net (code "149") (name "Net-(U35-COL)") (class "Default")
      (node (ref "CN8") (pin "5") (pinfunction "5_5") (pintype "bidirectional"))
      (node (ref "U35") (pin "4") (pinfunction "COL_4") (pintype "passive"))
    )
    (net (code "150") (name "Net-(U35-EMI)") (class "Default")
      (node (ref "CN8") (pin "6") (pinfunction "6_6") (pintype "bidirectional"))
      (node (ref "U35") (pin "3") (pinfunction "EMI_3") (pintype "passive"))
    )
    (net (code "151") (name "Net-(U36A-R{slash}C)") (class "Default")
      (node (ref "C63") (pin "2") (pinfunction "2_2") (pintype "passive"))
      (node (ref "R99") (pin "2") (pinfunction "2_2") (pintype "passive"))
      (node (ref "U36") (pin "15") (pinfunction "R/C_15") (pintype "input"))
    )
    (net (code "152") (name "Net-(U36A-{slash}Q)") (class "Default")
      (node (ref "D6") (pin "C") (pinfunction "C_C") (pintype "passive"))
      (node (ref "U36") (pin "4") (pinfunction "/Q_4") (pintype "output"))
    )
    (net (code "153") (name "Net-(U36B-R{slash}C)") (class "Default")
      (node (ref "C65") (pin "2") (pinfunction "2_2") (pintype "passive"))
      (node (ref "R103") (pin "2") (pinfunction "2_2") (pintype "passive"))
      (node (ref "U36") (pin "7") (pinfunction "R/C_7") (pintype "input"))
    )
    (net (code "154") (name "Net-(U36B-{slash}Q)") (class "Default")
      (node (ref "D9") (pin "C") (pinfunction "C_C") (pintype "passive"))
      (node (ref "U36") (pin "12") (pinfunction "/Q_12") (pintype "output"))
    )
    (net (code "155") (name "Net-(U37A-R{slash}C)") (class "Default")
      (node (ref "C62") (pin "2") (pinfunction "2_2") (pintype "passive"))
      (node (ref "R97") (pin "2") (pinfunction "2_2") (pintype "passive"))
      (node (ref "U37") (pin "15") (pinfunction "R/C_15") (pintype "input"))
    )
    (net (code "156") (name "Net-(U37A-{slash}Q)") (class "Default")
      (node (ref "D7") (pin "C") (pinfunction "C_C") (pintype "passive"))
      (node (ref "U37") (pin "4") (pinfunction "/Q_4") (pintype "output"))
    )
    (net (code "157") (name "Net-(U38A-I)") (class "Default")
      (node (ref "C64") (pin "1") (pinfunction "1_1") (pintype "passive"))
      (node (ref "R102") (pin "2") (pinfunction "2_2") (pintype "passive"))
      (node (ref "U38") (pin "13") (pinfunction "I_13") (pintype "input"))
    )
    (net (code "158") (name "Net-(U38B-I)") (class "Default")
      (node (ref "C66") (pin "1") (pinfunction "1_1") (pintype "passive"))
      (node (ref "R106") (pin "2") (pinfunction "2_2") (pintype "passive"))
      (node (ref "U38") (pin "11") (pinfunction "I_11") (pintype "input"))
    )
    (net (code "159") (name "Net-(U38C-I)") (class "Default")
      (node (ref "R107") (pin "2") (pinfunction "2_2") (pintype "passive"))
      (node (ref "U38") (pin "9") (pinfunction "I_9") (pintype "input"))
    )
    (net (code "160") (name "Net-(U38E-I)") (class "Default")
      (node (ref "R108") (pin "2") (pinfunction "2_2") (pintype "passive"))
      (node (ref "U38") (pin "3") (pinfunction "I_3") (pintype "input"))
    )
    (net (code "161") (name "Net-(U38F-I)") (class "Default")
      (node (ref "D6") (pin "A") (pinfunction "A_A") (pintype "passive"))
      (node (ref "D9") (pin "A") (pinfunction "A_A") (pintype "passive"))
      (node (ref "R100") (pin "1") (pinfunction "1_1") (pintype "passive"))
      (node (ref "U38") (pin "5") (pinfunction "I_5") (pintype "input"))
    )
    (net (code "162") (name "OFF_PULSE") (class "Default")
      (node (ref "U36") (pin "9") (pinfunction "A_9") (pintype "input"))
      (node (ref "U38") (pin "10") (pinfunction "O_10") (pintype "output"))
    )
    (net (code "163") (name "ON_PULSE") (class "Default")
      (node (ref "U36") (pin "1") (pinfunction "A_1") (pintype "input"))
      (node (ref "U38") (pin "12") (pinfunction "O_12") (pintype "output"))
    )
    (net (code "164") (name "POWER_CTRL") (class "Default")
      (node (ref "U33") (pin "2") (pinfunction "A1_2") (pintype "input"))
      (node (ref "U33") (pin "3") (pinfunction "A2_3") (pintype "input"))
      (node (ref "U33") (pin "4") (pinfunction "A3_4") (pintype "input"))
      (node (ref "U33") (pin "5") (pinfunction "A4_5") (pintype "input"))
      (node (ref "U33") (pin "6") (pinfunction "A5_6") (pintype "input"))
      (node (ref "U33") (pin "7") (pinfunction "A6_7") (pintype "input"))
      (node (ref "U33") (pin "8") (pinfunction "A7_8") (pintype "input"))
      (node (ref "U33") (pin "9") (pinfunction "A8_9") (pintype "input"))
      (node (ref "U38") (pin "6") (pinfunction "O_6") (pintype "output"))
    )
    (net (code "165") (name "POWER_RETHM") (class "Default")
      (node (ref "U12") (pin "2") (pinfunction "I0_2") (pintype "input"))
      (node (ref "U9") (pin "8") (pinfunction "~{Q}_8") (pintype "output"))
    )
    (net (code "166") (name "RETHM_F0") (class "Default")
      (node (ref "U23") (pin "9") (pinfunction "SYNC_9") (pintype "bidirectional"))
      (node (ref "U28") (pin "6") (pinfunction "1-5_6") (pintype "bidirectional"))
    )
    (net (code "167") (name "RETHM_F1") (class "Default")
      (node (ref "U26") (pin "9") (pinfunction "SYNC_9") (pintype "bidirectional"))
      (node (ref "U28") (pin "5") (pinfunction "1-4_5") (pintype "bidirectional"))
    )
    (net (code "168") (name "RETHM_F2") (class "Default")
      (node (ref "U24") (pin "9") (pinfunction "SYNC_9") (pintype "bidirectional"))
      (node (ref "U28") (pin "4") (pinfunction "1-3_4") (pintype "bidirectional"))
    )
    (net (code "169") (name "RETHM_F3") (class "Default")
      (node (ref "U27") (pin "9") (pinfunction "SYNC_9") (pintype "bidirectional"))
      (node (ref "U28") (pin "3") (pinfunction "1-2_3") (pintype "bidirectional"))
    )
    (net (code "170") (name "RETHM_F4") (class "Default")
      (node (ref "U25") (pin "9") (pinfunction "SYNC_9") (pintype "bidirectional"))
      (node (ref "U28") (pin "2") (pinfunction "1-1_2") (pintype "bidirectional"))
    )
    (net (code "171") (name "RETHM_POWER") (class "Default")
      (node (ref "U23") (pin "7") (pinfunction "POWER_7") (pintype "bidirectional"))
      (node (ref "U24") (pin "7") (pinfunction "POWER_7") (pintype "bidirectional"))
      (node (ref "U25") (pin "7") (pinfunction "POWER_7") (pintype "bidirectional"))
      (node (ref "U26") (pin "7") (pinfunction "POWER_7") (pintype "bidirectional"))
      (node (ref "U27") (pin "7") (pinfunction "POWER_7") (pintype "bidirectional"))
      (node (ref "U28") (pin "27") (pinfunction "1-18_27") (pintype "bidirectional"))
    )
    (net (code "172") (name "RETHM_SYNC0") (class "Default")
      (node (ref "U28") (pin "76") (pinfunction "2-21_76") (pintype "bidirectional"))
    )
    (net (code "173") (name "RETHM_SYNC1") (class "Default")
      (node (ref "U28") (pin "77") (pinfunction "2-22_77") (pintype "bidirectional"))
    )
    (net (code "174") (name "RETHM_SYNC2") (class "Default")
      (node (ref "U28") (pin "78") (pinfunction "2-23_78") (pintype "bidirectional"))
    )
    (net (code "175") (name "RETHM_SYNC3") (class "Default")
      (node (ref "U28") (pin "81") (pinfunction "2-24_81") (pintype "bidirectional"))
    )
    (net (code "176") (name "RETHM_SYNC4") (class "Default")
      (node (ref "U28") (pin "82") (pinfunction "2-25_82") (pintype "bidirectional"))
    )
    (net (code "177") (name "RMT_80{slash}~{RETHM}") (class "Default")
      (node (ref "R16") (pin "1") (pinfunction "1_1") (pintype "passive"))
      (node (ref "U28") (pin "71") (pinfunction "2-16_71") (pintype "bidirectional"))
      (node (ref "U8") (pin "4") (pinfunction "COL_4") (pintype "passive"))
    )
    (net (code "178") (name "RMT_AMP_X10{slash}~{X1}") (class "Default")
      (node (ref "U28") (pin "73") (pinfunction "2-18_73") (pintype "bidirectional"))
    )
    (net (code "179") (name "RMT_Z0_10K{slash}~{100K}") (class "Default")
      (node (ref "U28") (pin "72") (pinfunction "2-17_72") (pintype "bidirectional"))
    )
    (net (code "180") (name "RX_DATA") (class "Default")
      (node (ref "R26") (pin "2") (pinfunction "2_2") (pintype "passive"))
      (node (ref "TP3") (pin "1") (pinfunction "MP_1") (pintype "passive"))
      (node (ref "U2") (pin "2") (pinfunction "O_2") (pintype "output"))
    )
    (net (code "181") (name "SW_80HZ{slash}~{RETHM}") (class "Default")
      (node (ref "C56") (pin "1") (pinfunction "1_1") (pintype "passive"))
      (node (ref "R84") (pin "1") (pinfunction "1_1") (pintype "passive"))
      (node (ref "R85") (pin "1") (pinfunction "1_1") (pintype "passive"))
      (node (ref "U28") (pin "52") (pinfunction "2-1_52") (pintype "bidirectional"))
    )
    (net (code "182") (name "SW_AMP_X10{slash}~{X1}") (class "Default")
      (node (ref "C45") (pin "1") (pinfunction "1_1") (pintype "passive"))
      (node (ref "R78") (pin "1") (pinfunction "1_1") (pintype "passive"))
      (node (ref "R79") (pin "1") (pinfunction "1_1") (pintype "passive"))
      (node (ref "U28") (pin "55") (pinfunction "2-4_55") (pintype "bidirectional"))
    )
    (net (code "183") (name "SW_OPTION") (class "Default")
      (node (ref "C55") (pin "1") (pinfunction "1_1") (pintype "passive"))
      (node (ref "R82") (pin "1") (pinfunction "1_1") (pintype "passive"))
      (node (ref "R83") (pin "1") (pinfunction "1_1") (pintype "passive"))
      (node (ref "U28") (pin "53") (pinfunction "2-2_53") (pintype "bidirectional"))
    )
    (net (code "184") (name "SW_Z0_10K{slash}~{100K}") (class "Default")
      (node (ref "C52") (pin "1") (pinfunction "1_1") (pintype "passive"))
      (node (ref "R80") (pin "1") (pinfunction "1_1") (pintype "passive"))
      (node (ref "R81") (pin "1") (pinfunction "1_1") (pintype "passive"))
      (node (ref "U28") (pin "54") (pinfunction "2-3_54") (pintype "bidirectional"))
    )
    (net (code "185") (name "SYNC") (class "Default")
      (node (ref "R96") (pin "2") (pinfunction "2_2") (pintype "passive"))
      (node (ref "U38") (pin "2") (pinfunction "O_2") (pintype "output"))
    )
    (net (code "186") (name "SYNC80") (class "Default")
      (node (ref "R62") (pin "2") (pinfunction "2_2") (pintype "passive"))
      (node (ref "TP9") (pin "1") (pinfunction "MP_1") (pintype "passive"))
      (node (ref "U28") (pin "18") (pinfunction "1-13_18") (pintype "bidirectional"))
    )
    (net (code "187") (name "TX_DATA") (class "Default")
      (node (ref "TP1") (pin "1") (pinfunction "MP_1") (pintype "passive"))
      (node (ref "U2") (pin "7") (pinfunction "O_7") (pintype "output"))
      (node (ref "U4") (pin "2") (pinfunction "A1_2") (pintype "input"))
      (node (ref "U4") (pin "3") (pinfunction "A2_3") (pintype "input"))
      (node (ref "U4") (pin "4") (pinfunction "A3_4") (pintype "input"))
      (node (ref "U4") (pin "5") (pinfunction "A4_5") (pintype "input"))
      (node (ref "U4") (pin "6") (pinfunction "A5_6") (pintype "input"))
      (node (ref "U4") (pin "7") (pinfunction "A6_7") (pintype "input"))
      (node (ref "U4") (pin "8") (pinfunction "A7_8") (pintype "input"))
      (node (ref "U4") (pin "9") (pinfunction "A8_9") (pintype "input"))
    )
    (net (code "188") (name "V+5") (class "Default")
      (node (ref "C60") (pin "1") (pinfunction "1_1") (pintype "passive"))
      (node (ref "C61") (pin "2") (pinfunction "2_2") (pintype "passive"))
      (node (ref "C67") (pin "POS") (pinfunction "POS_POS") (pintype "passive"))
      (node (ref "C68") (pin "1") (pinfunction "1_1") (pintype "passive"))
      (node (ref "C69") (pin "1") (pinfunction "1_1") (pintype "passive"))
      (node (ref "C70") (pin "1") (pinfunction "1_1") (pintype "passive"))
      (node (ref "C71") (pin "1") (pinfunction "1_1") (pintype "passive"))
      (node (ref "L8") (pin "2") (pinfunction "4_2") (pintype "passive"))
      (node (ref "R100") (pin "2") (pinfunction "2_2") (pintype "passive"))
      (node (ref "R101") (pin "2") (pinfunction "2_2") (pintype "passive"))
      (node (ref "R103") (pin "1") (pinfunction "1_1") (pintype "passive"))
      (node (ref "R104") (pin "2") (pinfunction "2_2") (pintype "passive"))
      (node (ref "R87") (pin "1") (pinfunction "1_1") (pintype "passive"))
      (node (ref "R89") (pin "2") (pinfunction "2_2") (pintype "passive"))
      (node (ref "R92") (pin "1") (pinfunction "1_1") (pintype "passive"))
      (node (ref "R97") (pin "1") (pinfunction "1_1") (pintype "passive"))
      (node (ref "R98") (pin "2") (pinfunction "2_2") (pintype "passive"))
      (node (ref "R99") (pin "1") (pinfunction "1_1") (pintype "passive"))
      (node (ref "U33") (pin "20") (pinfunction "VCC_20") (pintype "power_in"))
      (node (ref "U34") (pin "3") (pinfunction "VCC_3") (pintype "passive"))
      (node (ref "U36") (pin "11") (pinfunction "CLR_11") (pintype "input"))
      (node (ref "U36") (pin "16") (pinfunction "VCC_16") (pintype "power_in"))
      (node (ref "U36") (pin "3") (pinfunction "CLR_3") (pintype "input"))
      (node (ref "U37") (pin "16") (pinfunction "VCC_16") (pintype "power_in"))
      (node (ref "U37") (pin "3") (pinfunction "CLR_3") (pintype "input"))
      (node (ref "U37") (pin "9") (pinfunction "A_9") (pintype "input"))
      (node (ref "U38") (pin "14") (pinfunction "VCC_14") (pintype "power_in"))
    )
    (net (code "189") (name "VA+1V8") (class "Default")
      (node (ref "C51") (pin "2") (pinfunction "2_2") (pintype "passive"))
      (node (ref "C54") (pin "2") (pinfunction "2_2") (pintype "passive"))
      (node (ref "C59") (pin "1") (pinfunction "1_1") (pintype "passive"))
      (node (ref "U28") (pin "13") (pinfunction "VCCINT_1_13") (pintype "power_in"))
      (node (ref "U28") (pin "63") (pinfunction "VCCINT_2_63") (pintype "power_in"))
      (node (ref "U29") (pin "5") (pinfunction "VO_5") (pintype "passive"))
    )
    (net (code "190") (name "VA+3V3") (class "Default")
      (node (ref "C23") (pin "2") (pinfunction "2_2") (pintype "passive"))
      (node (ref "C31") (pin "1") (pinfunction "1_1") (pintype "passive"))
      (node (ref "C32") (pin "1") (pinfunction "1_1") (pintype "passive"))
      (node (ref "C33") (pin "1") (pinfunction "1_1") (pintype "passive"))
      (node (ref "C34") (pin "1") (pinfunction "1_1") (pintype "passive"))
      (node (ref "C35") (pin "1") (pinfunction "1_1") (pintype "passive"))
      (node (ref "C36") (pin "1") (pinfunction "1_1") (pintype "passive"))
      (node (ref "C37") (pin "1") (pinfunction "1_1") (pintype "passive"))
      (node (ref "C39") (pin "1") (pinfunction "1_1") (pintype "passive"))
      (node (ref "C46") (pin "1") (pinfunction "1_1") (pintype "passive"))
      (node (ref "C47") (pin "2") (pinfunction "2_2") (pintype "passive"))
      (node (ref "C48") (pin "1") (pinfunction "1_1") (pintype "passive"))
      (node (ref "C49") (pin "2") (pinfunction "2_2") (pintype "passive"))
      (node (ref "C50") (pin "1") (pinfunction "1_1") (pintype "passive"))
      (node (ref "C53") (pin "1") (pinfunction "1_1") (pintype "passive"))
      (node (ref "C57") (pin "1") (pinfunction "1_1") (pintype "passive"))
      (node (ref "CN7") (pin "4") (pinfunction "4_4") (pintype "bidirectional"))
      (node (ref "D4") (pin "A") (pinfunction "A1_A") (pintype "passive"))
      (node (ref "R10") (pin "2") (pinfunction "2_2") (pintype "passive"))
      (node (ref "R14") (pin "2") (pinfunction "2_2") (pintype "passive"))
      (node (ref "R16") (pin "2") (pinfunction "2_2") (pintype "passive"))
      (node (ref "R3") (pin "2") (pinfunction "2_2") (pintype "passive"))
      (node (ref "R65") (pin "2") (pinfunction "2_2") (pintype "passive"))
      (node (ref "R68") (pin "2") (pinfunction "2_2") (pintype "passive"))
      (node (ref "R74") (pin "2") (pinfunction "2_2") (pintype "passive"))
      (node (ref "R75") (pin "2") (pinfunction "2_2") (pintype "passive"))
      (node (ref "R76") (pin "2") (pinfunction "2_2") (pintype "passive"))
      (node (ref "R78") (pin "2") (pinfunction "2_2") (pintype "passive"))
      (node (ref "R80") (pin "2") (pinfunction "2_2") (pintype "passive"))
      (node (ref "R82") (pin "2") (pinfunction "2_2") (pintype "passive"))
      (node (ref "R84") (pin "2") (pinfunction "2_2") (pintype "passive"))
      (node (ref "U13") (pin "8") (pinfunction "V+_8") (pintype "power_in"))
      (node (ref "U14") (pin "8") (pinfunction "V+_8") (pintype "power_in"))
      (node (ref "U15") (pin "8") (pinfunction "V+_8") (pintype "power_in"))
      (node (ref "U16") (pin "8") (pinfunction "V+_8") (pintype "power_in"))
      (node (ref "U17") (pin "5") (pinfunction "V+_5") (pintype "power_in"))
      (node (ref "U18") (pin "16") (pinfunction "VCC_16") (pintype "power_in"))
      (node (ref "U20") (pin "5") (pinfunction "VO_5") (pintype "passive"))
      (node (ref "U21") (pin "16") (pinfunction "V+_16") (pintype "power_in"))
      (node (ref "U22") (pin "16") (pinfunction "V+_16") (pintype "power_in"))
      (node (ref "U28") (pin "31") (pinfunction "VCCIO1_2_31") (pintype "power_in"))
      (node (ref "U28") (pin "45") (pinfunction "VCCIO1_3_45") (pintype "power_in"))
      (node (ref "U28") (pin "59") (pinfunction "VCCIO2_1_59") (pintype "power_in"))
      (node (ref "U28") (pin "80") (pinfunction "VCCIO2_2_80") (pintype "power_in"))
      (node (ref "U28") (pin "9") (pinfunction "VCCIO1_1_9") (pintype "power_in"))
      (node (ref "U28") (pin "94") (pinfunction "VCCIO2_3_94") (pintype "power_in"))
      (node (ref "U29") (pin "1") (pinfunction "VI_1") (pintype "input"))
      (node (ref "U29") (pin "3") (pinfunction "EN_3") (pintype "input"))
    )
    (net (code "191") (name "VA+5") (class "Default")
      (node (ref "C29") (pin "1") (pinfunction "1_1") (pintype "passive"))
      (node (ref "C30") (pin "POS") (pinfunction "POS_POS") (pintype "passive"))
      (node (ref "C40") (pin "1") (pinfunction "1_1") (pintype "passive"))
      (node (ref "C41") (pin "1") (pinfunction "1_1") (pintype "passive"))
      (node (ref "C42") (pin "1") (pinfunction "1_1") (pintype "passive"))
      (node (ref "C43") (pin "1") (pinfunction "1_1") (pintype "passive"))
      (node (ref "C44") (pin "1") (pinfunction "1_1") (pintype "passive"))
      (node (ref "L7") (pin "1") (pinfunction "2_1") (pintype "passive"))
      (node (ref "R66") (pin "2") (pinfunction "2_2") (pintype "passive"))
      (node (ref "R73") (pin "1") (pinfunction "1_1") (pintype "passive"))
      (node (ref "U19") (pin "6") (pinfunction "VDD_6") (pintype "power_in"))
      (node (ref "U20") (pin "1") (pinfunction "VI_1") (pintype "input"))
      (node (ref "U23") (pin "11") (pinfunction "V+5_11") (pintype "bidirectional"))
      (node (ref "U24") (pin "11") (pinfunction "V+5_11") (pintype "bidirectional"))
      (node (ref "U25") (pin "11") (pinfunction "V+5_11") (pintype "bidirectional"))
      (node (ref "U26") (pin "11") (pinfunction "V+5_11") (pintype "bidirectional"))
      (node (ref "U27") (pin "11") (pinfunction "V+5_11") (pintype "bidirectional"))
    )
    (net (code "192") (name "VD+5") (class "Default")
      (node (ref "C1") (pin "1") (pinfunction "1_1") (pintype "passive"))
      (node (ref "C10") (pin "1") (pinfunction "1_1") (pintype "passive"))
      (node (ref "C11") (pin "1") (pinfunction "1_1") (pintype "passive"))
      (node (ref "C12") (pin "1") (pinfunction "1_1") (pintype "passive"))
      (node (ref "C2") (pin "2") (pinfunction "2_2") (pintype "passive"))
      (node (ref "C3") (pin "2") (pinfunction "2_2") (pintype "passive"))
      (node (ref "C7") (pin "POS") (pinfunction "POS_POS") (pintype "passive"))
      (node (ref "C8") (pin "1") (pinfunction "1_1") (pintype "passive"))
      (node (ref "C9") (pin "1") (pinfunction "1_1") (pintype "passive"))
      (node (ref "D2") (pin "C") (pinfunction "C_C") (pintype "passive"))
      (node (ref "L1") (pin "1") (pinfunction "2_1") (pintype "passive"))
      (node (ref "R13") (pin "1") (pinfunction "1_1") (pintype "passive"))
      (node (ref "R15") (pin "1") (pinfunction "1_1") (pintype "passive"))
      (node (ref "R17") (pin "1") (pinfunction "1_1") (pintype "passive"))
      (node (ref "R18") (pin "2") (pinfunction "2_2") (pintype "passive"))
      (node (ref "R19") (pin "2") (pinfunction "2_2") (pintype "passive"))
      (node (ref "R2") (pin "1") (pinfunction "1_1") (pintype "passive"))
      (node (ref "R20") (pin "1") (pinfunction "1_1") (pintype "passive"))
      (node (ref "R22") (pin "2") (pinfunction "2_2") (pintype "passive"))
      (node (ref "R25") (pin "1") (pinfunction "1_1") (pintype "passive"))
      (node (ref "R27") (pin "2") (pinfunction "2_2") (pintype "passive"))
      (node (ref "R5") (pin "2") (pinfunction "2_2") (pintype "passive"))
      (node (ref "R9") (pin "1") (pinfunction "1_1") (pintype "passive"))
      (node (ref "U10") (pin "5") (pinfunction "V+_5") (pintype "power_in"))
      (node (ref "U11") (pin "16") (pinfunction "VCC_16") (pintype "power_in"))
      (node (ref "U11") (pin "2") (pinfunction "B_2") (pintype "input"))
      (node (ref "U11") (pin "3") (pinfunction "CLR_3") (pintype "input"))
      (node (ref "U11") (pin "9") (pinfunction "A_9") (pintype "input"))
      (node (ref "U12") (pin "5") (pinfunction "VCC_5") (pintype "power_in"))
      (node (ref "U2") (pin "8") (pinfunction "VCC_8") (pintype "power_in"))
      (node (ref "U4") (pin "20") (pinfunction "VCC_20") (pintype "power_in"))
      (node (ref "U6") (pin "3") (pinfunction "VCC_3") (pintype "passive"))
      (node (ref "U9") (pin "14") (pinfunction "VCC_14") (pintype "power_in"))
    )
    (net (code "193") (name "ZOUT") (class "Default")
      (node (ref "U16") (pin "1") (pinfunction "IN_1") (pintype "input"))
      (node (ref "U16") (pin "5") (pinfunction "IN_5") (pintype "input"))
      (node (ref "U23") (pin "4") (pinfunction "ZOUT_4") (pintype "bidirectional"))
      (node (ref "U24") (pin "4") (pinfunction "ZOUT_4") (pintype "bidirectional"))
      (node (ref "U25") (pin "4") (pinfunction "ZOUT_4") (pintype "bidirectional"))
      (node (ref "U26") (pin "4") (pinfunction "ZOUT_4") (pintype "bidirectional"))
      (node (ref "U27") (pin "4") (pinfunction "ZOUT_4") (pintype "bidirectional"))
      (node (ref "U28") (pin "21") (pinfunction "1-16_21") (pintype "bidirectional"))
    )
    (net (code "194") (name "unconnected-(CN7-Pad6)") (class "Default")
      (node (ref "CN7") (pin "6") (pinfunction "6_6") (pintype "bidirectional"))
    )
    (net (code "195") (name "unconnected-(CN7-Pad7)") (class "Default")
      (node (ref "CN7") (pin "7") (pinfunction "7_7") (pintype "bidirectional"))
    )
    (net (code "196") (name "unconnected-(CN7-Pad8)") (class "Default")
      (node (ref "CN7") (pin "8") (pinfunction "8_8") (pintype "bidirectional"))
    )
    (net (code "197") (name "unconnected-(CN9-Pad2)") (class "Default")
      (node (ref "CN9") (pin "2") (pinfunction "2_2") (pintype "bidirectional"))
    )
    (net (code "198") (name "unconnected-(CN9-Pad3)") (class "Default")
      (node (ref "CN9") (pin "3") (pinfunction "3_3") (pintype "bidirectional"))
    )
    (net (code "199") (name "unconnected-(CN9-Pad4)") (class "Default")
      (node (ref "CN9") (pin "4") (pinfunction "4_4") (pintype "bidirectional"))
    )
    (net (code "200") (name "unconnected-(SW1A-NC-Pad3)") (class "Default")
      (node (ref "SW1") (pin "3") (pinfunction "NC_3") (pintype "passive"))
    )
    (net (code "201") (name "unconnected-(SW1B-BRACKET-Pad7)") (class "Default")
      (node (ref "SW1") (pin "7") (pinfunction "BRACKET_7") (pintype "passive"))
    )
    (net (code "202") (name "unconnected-(SW1C-BRACKET-Pad8)") (class "Default")
      (node (ref "SW1") (pin "8") (pinfunction "BRACKET_8") (pintype "passive"))
    )
    (net (code "203") (name "unconnected-(SW2A-NO-Pad1)") (class "Default")
      (node (ref "SW2") (pin "1") (pinfunction "NO_1") (pintype "passive"))
    )
    (net (code "204") (name "unconnected-(SW3A-NO-Pad1)") (class "Default")
      (node (ref "SW3") (pin "1") (pinfunction "NO_1") (pintype "passive"))
    )
    (net (code "205") (name "unconnected-(SW4A-NO-Pad1)") (class "Default")
      (node (ref "SW4") (pin "1") (pinfunction "NO_1") (pintype "passive"))
    )
    (net (code "206") (name "unconnected-(SW5A-NO-Pad1)") (class "Default")
      (node (ref "SW5") (pin "1") (pinfunction "NO_1") (pintype "passive"))
    )
    (net (code "207") (name "unconnected-(U3-NC1-Pad3)") (class "Default")
      (node (ref "U3") (pin "3") (pinfunction "NC1_3") (pintype "passive"))
    )
    (net (code "208") (name "unconnected-(U3-NC2-Pad4)") (class "Default")
      (node (ref "U3") (pin "4") (pinfunction "NC2_4") (pintype "passive"))
    )
    (net (code "209") (name "unconnected-(U3-TAB1-Pad8)") (class "Default")
      (node (ref "U3") (pin "8") (pinfunction "TAB1_8") (pintype "passive"))
    )
    (net (code "210") (name "unconnected-(U3-TAB2-Pad5)") (class "Default")
      (node (ref "U3") (pin "5") (pinfunction "TAB2_5") (pintype "passive"))
    )
    (net (code "211") (name "unconnected-(U4A-~{Y1}-Pad18)") (class "Default")
      (node (ref "U4") (pin "18") (pinfunction "~{Y1}_18") (pintype "output"))
    )
    (net (code "212") (name "unconnected-(U6-TAB1-Pad8)") (class "Default")
      (node (ref "U6") (pin "8") (pinfunction "TAB1_8") (pintype "passive"))
    )
    (net (code "213") (name "unconnected-(U6-TAB2-Pad5)") (class "Default")
      (node (ref "U6") (pin "5") (pinfunction "TAB2_5") (pintype "passive"))
    )
    (net (code "214") (name "unconnected-(U9A-~{Q}-Pad6)") (class "Default")
      (node (ref "U9") (pin "6") (pinfunction "~{Q}_6") (pintype "output"))
    )
    (net (code "215") (name "unconnected-(U11A-Q-Pad13)") (class "Default")
      (node (ref "U11") (pin "13") (pinfunction "Q_13") (pintype "output"))
    )
    (net (code "216") (name "unconnected-(U11B-C-Pad6)") (class "Default")
      (node (ref "U11") (pin "6") (pinfunction "C_6") (pintype "input"))
    )
    (net (code "217") (name "unconnected-(U11B-Q-Pad5)") (class "Default")
      (node (ref "U11") (pin "5") (pinfunction "Q_5") (pintype "output"))
    )
    (net (code "218") (name "unconnected-(U11B-R{slash}C-Pad7)") (class "Default")
      (node (ref "U11") (pin "7") (pinfunction "R/C_7") (pintype "input"))
    )
    (net (code "219") (name "unconnected-(U11B-{slash}Q-Pad12)") (class "Default")
      (node (ref "U11") (pin "12") (pinfunction "/Q_12") (pintype "output"))
    )
    (net (code "220") (name "unconnected-(U18-Pad2)") (class "Default")
      (node (ref "U18") (pin "2") (pinfunction "2_2") (pintype "bidirectional"))
    )
    (net (code "221") (name "unconnected-(U18D-0-Pad1)") (class "Default")
      (node (ref "U18") (pin "1") (pinfunction "0_1") (pintype "bidirectional"))
    )
    (net (code "222") (name "unconnected-(U18D-1-Pad5)") (class "Default")
      (node (ref "U18") (pin "5") (pinfunction "1_5") (pintype "bidirectional"))
    )
    (net (code "223") (name "unconnected-(U18D-3-Pad4)") (class "Default")
      (node (ref "U18") (pin "4") (pinfunction "3_4") (pintype "bidirectional"))
    )
    (net (code "224") (name "unconnected-(U18D-COM-Pad3)") (class "Default")
      (node (ref "U18") (pin "3") (pinfunction "COM_3") (pintype "bidirectional"))
    )
    (net (code "225") (name "unconnected-(U19-~{MR}-Pad3)") (class "Default")
      (node (ref "U19") (pin "3") (pinfunction "~{MR}_3") (pintype "bidirectional"))
    )
    (net (code "226") (name "unconnected-(U21-Pad5)") (class "Default")
      (node (ref "U21") (pin "5") (pinfunction "5_5") (pintype "bidirectional"))
    )
    (net (code "227") (name "unconnected-(U21B-6-Pad2)") (class "Default")
      (node (ref "U21") (pin "2") (pinfunction "6_2") (pintype "bidirectional"))
    )
    (net (code "228") (name "unconnected-(U21B-7-Pad4)") (class "Default")
      (node (ref "U21") (pin "4") (pinfunction "7_4") (pintype "bidirectional"))
    )
    (net (code "229") (name "unconnected-(U22-Pad5)") (class "Default")
      (node (ref "U22") (pin "5") (pinfunction "5_5") (pintype "bidirectional"))
    )
    (net (code "230") (name "unconnected-(U22B-6-Pad2)") (class "Default")
      (node (ref "U22") (pin "2") (pinfunction "6_2") (pintype "bidirectional"))
    )
    (net (code "231") (name "unconnected-(U22B-7-Pad4)") (class "Default")
      (node (ref "U22") (pin "4") (pinfunction "7_4") (pintype "bidirectional"))
    )
    (net (code "232") (name "unconnected-(U28B-1-19-Pad28)") (class "Default")
      (node (ref "U28") (pin "28") (pinfunction "1-19_28") (pintype "bidirectional"))
    )
    (net (code "233") (name "unconnected-(U28B-1-21-Pad30)") (class "Default")
      (node (ref "U28") (pin "30") (pinfunction "1-21_30") (pintype "bidirectional"))
    )
    (net (code "234") (name "unconnected-(U28B-1-22-Pad33)") (class "Default")
      (node (ref "U28") (pin "33") (pinfunction "1-22_33") (pintype "bidirectional"))
    )
    (net (code "235") (name "unconnected-(U28B-1-23-Pad34)") (class "Default")
      (node (ref "U28") (pin "34") (pinfunction "1-23_34") (pintype "bidirectional"))
    )
    (net (code "236") (name "unconnected-(U28B-1-24-Pad35)") (class "Default")
      (node (ref "U28") (pin "35") (pinfunction "1-24_35") (pintype "bidirectional"))
    )
    (net (code "237") (name "unconnected-(U28B-1-25-Pad36)") (class "Default")
      (node (ref "U28") (pin "36") (pinfunction "1-25_36") (pintype "bidirectional"))
    )
    (net (code "238") (name "unconnected-(U28B-1-26-Pad37)") (class "Default")
      (node (ref "U28") (pin "37") (pinfunction "1-26_37") (pintype "bidirectional"))
    )
    (net (code "239") (name "unconnected-(U28B-1-27-Pad38)") (class "Default")
      (node (ref "U28") (pin "38") (pinfunction "1-27_38") (pintype "bidirectional"))
    )
    (net (code "240") (name "unconnected-(U28B-1-28-Pad39)") (class "Default")
      (node (ref "U28") (pin "39") (pinfunction "1-28_39") (pintype "bidirectional"))
    )
    (net (code "241") (name "unconnected-(U28B-1-29-Pad40)") (class "Default")
      (node (ref "U28") (pin "40") (pinfunction "1-29_40") (pintype "bidirectional"))
    )
    (net (code "242") (name "unconnected-(U28B-1-30-Pad41)") (class "Default")
      (node (ref "U28") (pin "41") (pinfunction "1-30_41") (pintype "bidirectional"))
    )
    (net (code "243") (name "unconnected-(U28B-1-31-Pad42)") (class "Default")
      (node (ref "U28") (pin "42") (pinfunction "1-31_42") (pintype "bidirectional"))
    )
    (net (code "244") (name "unconnected-(U28B-1-34-Pad47)") (class "Default")
      (node (ref "U28") (pin "47") (pinfunction "1-34_47") (pintype "bidirectional"))
    )
    (net (code "245") (name "unconnected-(U28B-1-35-Pad48)") (class "Default")
      (node (ref "U28") (pin "48") (pinfunction "1-35_48") (pintype "bidirectional"))
    )
    (net (code "246") (name "unconnected-(U28B-1-36-Pad49)") (class "Default")
      (node (ref "U28") (pin "49") (pinfunction "1-36_49") (pintype "bidirectional"))
    )
    (net (code "247") (name "unconnected-(U28B-1-37-Pad50)") (class "Default")
      (node (ref "U28") (pin "50") (pinfunction "1-37_50") (pintype "bidirectional"))
    )
    (net (code "248") (name "unconnected-(U28B-1-38-Pad51)") (class "Default")
      (node (ref "U28") (pin "51") (pinfunction "1-38_51") (pintype "bidirectional"))
    )
    (net (code "249") (name "unconnected-(U28B-2-9{slash}CLK2-Pad62)") (class "Default")
      (node (ref "U28") (pin "62") (pinfunction "2-9/CLK2_62") (pintype "bidirectional"))
    )
    (net (code "250") (name "unconnected-(U28B-2-10{slash}CLK3-Pad64)") (class "Default")
      (node (ref "U28") (pin "64") (pinfunction "2-10/CLK3_64") (pintype "bidirectional"))
    )
    (net (code "251") (name "unconnected-(U28B-2-11-Pad66)") (class "Default")
      (node (ref "U28") (pin "66") (pinfunction "2-11_66") (pintype "bidirectional"))
    )
    (net (code "252") (name "unconnected-(U28B-2-12-Pad67)") (class "Default")
      (node (ref "U28") (pin "67") (pinfunction "2-12_67") (pintype "bidirectional"))
    )
    (net (code "253") (name "unconnected-(U28B-2-13-Pad68)") (class "Default")
      (node (ref "U28") (pin "68") (pinfunction "2-13_68") (pintype "bidirectional"))
    )
    (net (code "254") (name "unconnected-(U28B-2-26-Pad83)") (class "Default")
      (node (ref "U28") (pin "83") (pinfunction "2-26_83") (pintype "bidirectional"))
    )
    (net (code "255") (name "unconnected-(U28B-2-27-Pad84)") (class "Default")
      (node (ref "U28") (pin "84") (pinfunction "2-27_84") (pintype "bidirectional"))
    )
    (net (code "256") (name "unconnected-(U28B-2-28-Pad85)") (class "Default")
      (node (ref "U28") (pin "85") (pinfunction "2-28_85") (pintype "bidirectional"))
    )
    (net (code "257") (name "unconnected-(U28B-2-29-Pad86)") (class "Default")
      (node (ref "U28") (pin "86") (pinfunction "2-29_86") (pintype "bidirectional"))
    )
    (net (code "258") (name "unconnected-(U28B-2-30-Pad87)") (class "Default")
      (node (ref "U28") (pin "87") (pinfunction "2-30_87") (pintype "bidirectional"))
    )
    (net (code "259") (name "unconnected-(U28B-2-31-Pad88)") (class "Default")
      (node (ref "U28") (pin "88") (pinfunction "2-31_88") (pintype "bidirectional"))
    )
    (net (code "260") (name "unconnected-(U28B-2-32-Pad89)") (class "Default")
      (node (ref "U28") (pin "89") (pinfunction "2-32_89") (pintype "bidirectional"))
    )
    (net (code "261") (name "unconnected-(U28B-2-33-Pad90)") (class "Default")
      (node (ref "U28") (pin "90") (pinfunction "2-33_90") (pintype "bidirectional"))
    )
    (net (code "262") (name "unconnected-(U28B-2-34-Pad91)") (class "Default")
      (node (ref "U28") (pin "91") (pinfunction "2-34_91") (pintype "bidirectional"))
    )
    (net (code "263") (name "unconnected-(U28B-2-35-Pad92)") (class "Default")
      (node (ref "U28") (pin "92") (pinfunction "2-35_92") (pintype "bidirectional"))
    )
    (net (code "264") (name "unconnected-(U28B-2-36-Pad95)") (class "Default")
      (node (ref "U28") (pin "95") (pinfunction "2-36_95") (pintype "bidirectional"))
    )
    (net (code "265") (name "unconnected-(U28B-2-37-Pad96)") (class "Default")
      (node (ref "U28") (pin "96") (pinfunction "2-37_96") (pintype "bidirectional"))
    )
    (net (code "266") (name "unconnected-(U28B-2-38-Pad97)") (class "Default")
      (node (ref "U28") (pin "97") (pinfunction "2-38_97") (pintype "bidirectional"))
    )
    (net (code "267") (name "unconnected-(U28B-2-39-Pad98)") (class "Default")
      (node (ref "U28") (pin "98") (pinfunction "2-39_98") (pintype "bidirectional"))
    )
    (net (code "268") (name "unconnected-(U28B-2-40-Pad99)") (class "Default")
      (node (ref "U28") (pin "99") (pinfunction "2-40_99") (pintype "bidirectional"))
    )
    (net (code "269") (name "unconnected-(U28B-2-41-Pad100)") (class "Default")
      (node (ref "U28") (pin "100") (pinfunction "2-41_100") (pintype "bidirectional"))
    )
    (net (code "270") (name "unconnected-(U31-NC1-Pad3)") (class "Default")
      (node (ref "U31") (pin "3") (pinfunction "NC1_3") (pintype "passive"))
    )
    (net (code "271") (name "unconnected-(U31-NC2-Pad4)") (class "Default")
      (node (ref "U31") (pin "4") (pinfunction "NC2_4") (pintype "passive"))
    )
    (net (code "272") (name "unconnected-(U31-TAB1-Pad8)") (class "Default")
      (node (ref "U31") (pin "8") (pinfunction "TAB1_8") (pintype "passive"))
    )
    (net (code "273") (name "unconnected-(U31-TAB2-Pad5)") (class "Default")
      (node (ref "U31") (pin "5") (pinfunction "TAB2_5") (pintype "passive"))
    )
    (net (code "274") (name "unconnected-(U34-TAB1-Pad8)") (class "Default")
      (node (ref "U34") (pin "8") (pinfunction "TAB1_8") (pintype "passive"))
    )
    (net (code "275") (name "unconnected-(U34-TAB2-Pad5)") (class "Default")
      (node (ref "U34") (pin "5") (pinfunction "TAB2_5") (pintype "passive"))
    )
    (net (code "276") (name "unconnected-(U36A-Q-Pad13)") (class "Default")
      (node (ref "U36") (pin "13") (pinfunction "Q_13") (pintype "output"))
    )
    (net (code "277") (name "unconnected-(U36B-Q-Pad5)") (class "Default")
      (node (ref "U36") (pin "5") (pinfunction "Q_5") (pintype "output"))
    )
    (net (code "278") (name "unconnected-(U37A-Q-Pad13)") (class "Default")
      (node (ref "U37") (pin "13") (pinfunction "Q_13") (pintype "output"))
    )
    (net (code "279") (name "unconnected-(U37B-C-Pad6)") (class "Default")
      (node (ref "U37") (pin "6") (pinfunction "C_6") (pintype "input"))
    )
    (net (code "280") (name "unconnected-(U37B-Q-Pad5)") (class "Default")
      (node (ref "U37") (pin "5") (pinfunction "Q_5") (pintype "output"))
    )
    (net (code "281") (name "unconnected-(U37B-R{slash}C-Pad7)") (class "Default")
      (node (ref "U37") (pin "7") (pinfunction "R/C_7") (pintype "input"))
    )
    (net (code "282") (name "unconnected-(U37B-{slash}Q-Pad12)") (class "Default")
      (node (ref "U37") (pin "12") (pinfunction "/Q_12") (pintype "output"))
    )
    (net (code "283") (name "unconnected-(U38C-O-Pad8)") (class "Default")
      (node (ref "U38") (pin "8") (pinfunction "O_8") (pintype "output"))
    )
    (net (code "284") (name "unconnected-(U38E-O-Pad4)") (class "Default")
      (node (ref "U38") (pin "4") (pinfunction "O_4") (pintype "output"))
    )
    (net (code "285") (name "~{80_OE}") (class "Default")
      (node (ref "U21") (pin "6") (pinfunction "EN_6") (pintype "input"))
      (node (ref "U22") (pin "6") (pinfunction "EN_6") (pintype "input"))
      (node (ref "U28") (pin "17") (pinfunction "1-12_17") (pintype "bidirectional"))
    )
    (net (code "286") (name "~{LOW_BAT}") (class "Default")
      (node (ref "R65") (pin "1") (pinfunction "1_1") (pintype "passive"))
      (node (ref "R72") (pin "1") (pinfunction "1_1") (pintype "passive"))
      (node (ref "U19") (pin "1") (pinfunction "~{RESET}_1") (pintype "output"))
      (node (ref "U28") (pin "8") (pinfunction "1-7_8") (pintype "bidirectional"))
    )
    (net (code "287") (name "~{OFF}") (class "Default")
      (node (ref "R92") (pin "2") (pinfunction "2_2") (pintype "passive"))
      (node (ref "U32") (pin "4") (pinfunction "COL_4") (pintype "passive"))
      (node (ref "U36") (pin "10") (pinfunction "B_10") (pintype "input"))
    )
    (net (code "288") (name "~{ON}") (class "Default")
      (node (ref "R87") (pin "2") (pinfunction "2_2") (pintype "passive"))
      (node (ref "U30") (pin "4") (pinfunction "COL_4") (pintype "passive"))
      (node (ref "U36") (pin "2") (pinfunction "B_2") (pintype "input"))
    )
    (net (code "289") (name "~{POWER_80}") (class "Default")
      (node (ref "U12") (pin "1") (pinfunction "I1_1") (pintype "input"))
      (node (ref "U4") (pin "1") (pinfunction "~{G1}_1") (pintype "input"))
      (node (ref "U4") (pin "19") (pinfunction "~{G2}_19") (pintype "input"))
      (node (ref "U7") (pin "2") (pinfunction "C_2") (pintype "passive"))
      (node (ref "U9") (pin "12") (pinfunction "D_12") (pintype "input"))
      (node (ref "U9") (pin "5") (pinfunction "Q_5") (pintype "output"))
    )
    (net (code "290") (name "~{POWER_ON}") (class "Default")
      (node (ref "R14") (pin "1") (pinfunction "1_1") (pintype "passive"))
      (node (ref "U28") (pin "74") (pinfunction "2-19_74") (pintype "bidirectional"))
      (node (ref "U7") (pin "4") (pinfunction "COL_4") (pintype "passive"))
    )
    (net (code "291") (name "~{POWER_RETHM}") (class "Default")
      (node (ref "U8") (pin "2") (pinfunction "C_2") (pintype "passive"))
      (node (ref "U9") (pin "9") (pinfunction "Q_9") (pintype "output"))
    )
    (net (code "292") (name "~{RETHM_OE}") (class "Default")
      (node (ref "U23") (pin "3") (pinfunction "~{OE}_3") (pintype "bidirectional"))
      (node (ref "U24") (pin "3") (pinfunction "~{OE}_3") (pintype "bidirectional"))
      (node (ref "U25") (pin "3") (pinfunction "~{OE}_3") (pintype "bidirectional"))
      (node (ref "U26") (pin "3") (pinfunction "~{OE}_3") (pintype "bidirectional"))
      (node (ref "U27") (pin "3") (pinfunction "~{OE}_3") (pintype "bidirectional"))
      (node (ref "U28") (pin "7") (pinfunction "1-6_7") (pintype "bidirectional"))
    )
    (net (code "293") (name "~{RMT_POWER}") (class "Default")
      (node (ref "U28") (pin "70") (pinfunction "2-15_70") (pintype "bidirectional"))
    )
  )
)
